# proto2.net
KiCad netlist of a schematic drawn in EAGLE
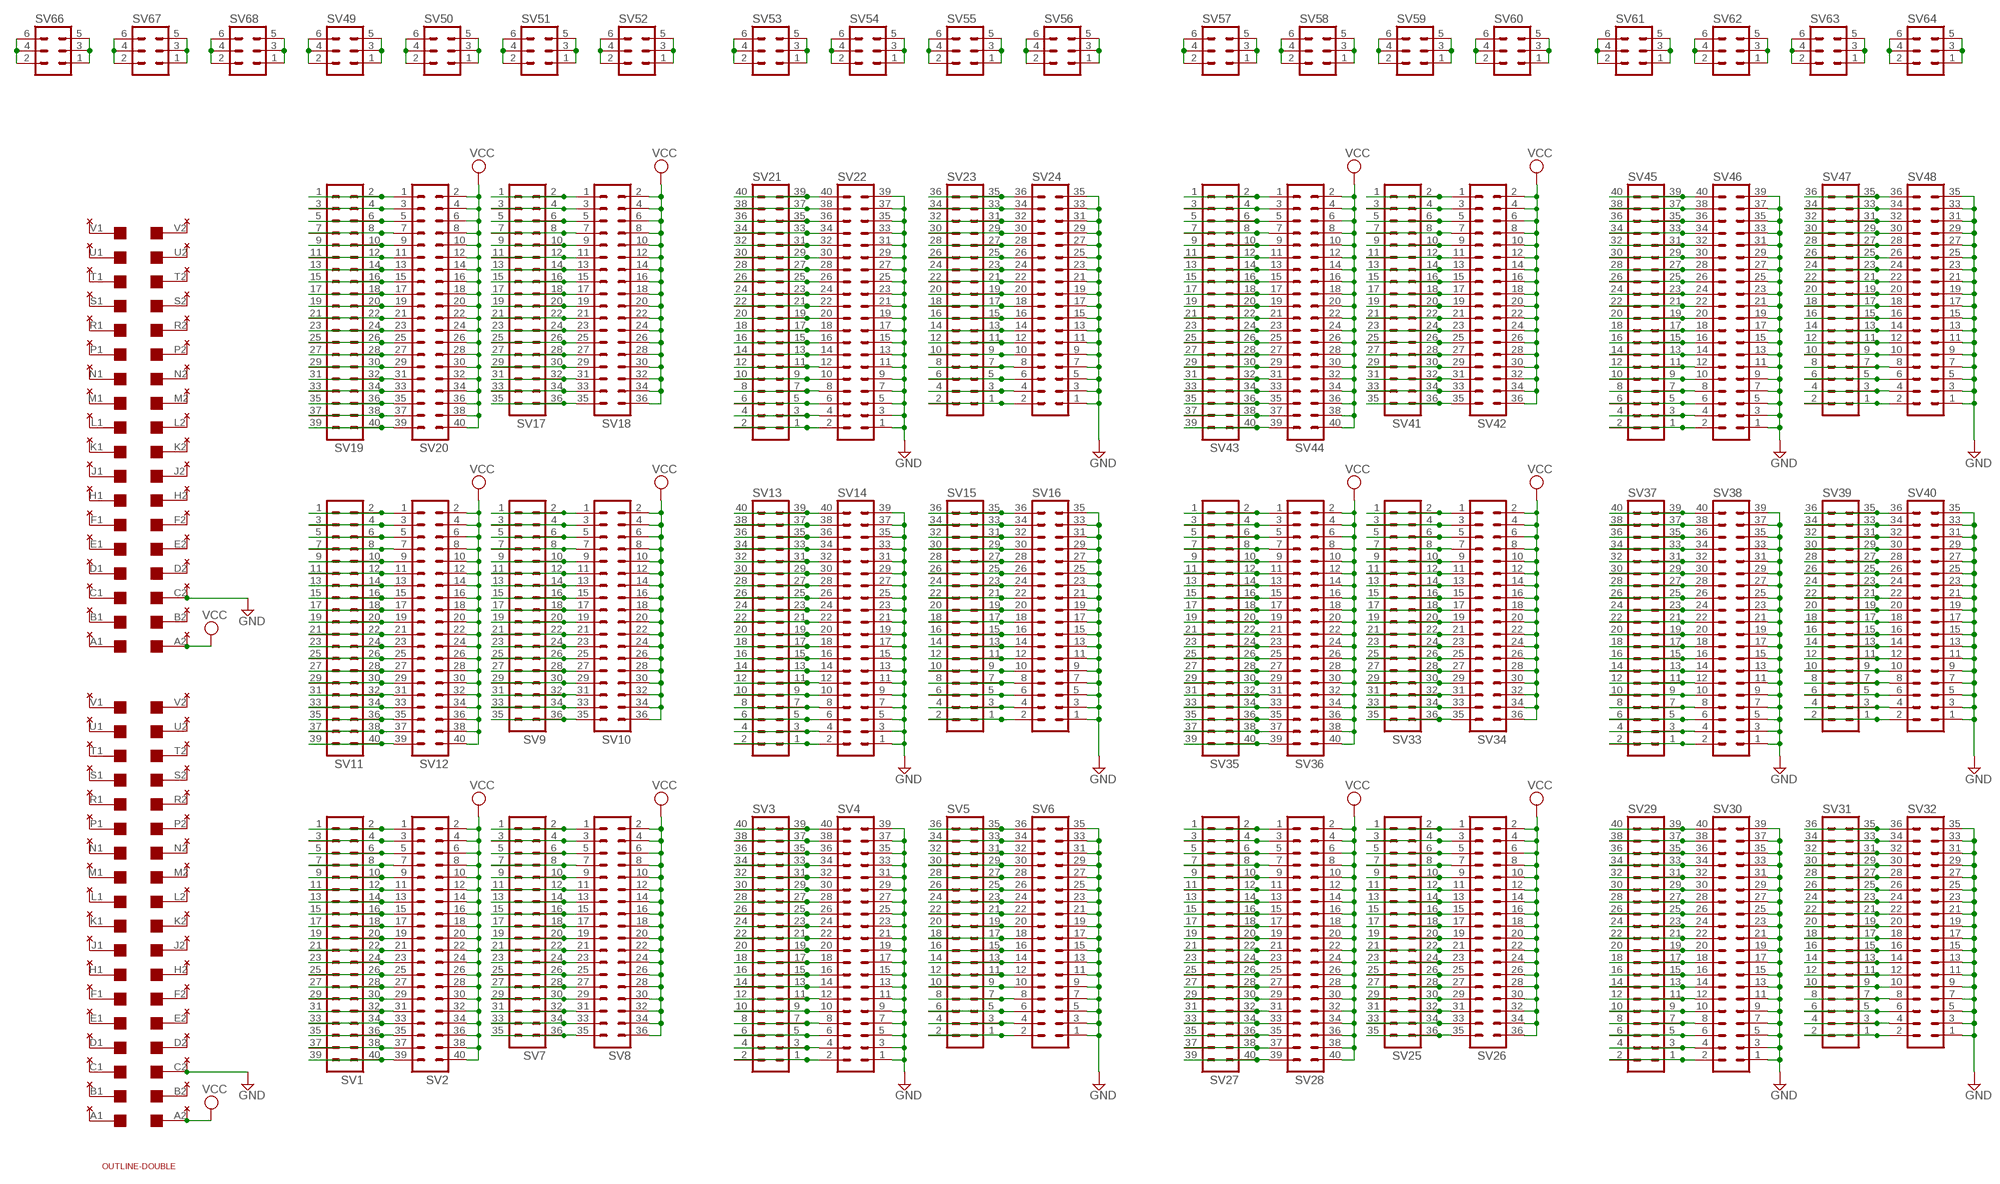
[diagram p0: schematic, sheet 1]

(export (version "E")
  (design (tool "Eeschema 10.0.6"))
  (components
    (comp (ref "A")
      (value "EDGE-2CONNECTOR")
      (footprint "eagle-import:EDGE-CON2")
      (libsource (lib "eagle-import") (part "EDGE-2CONNECTOR"))
    )
    (comp (ref "B")
      (value "EDGE-2CONNECTOR")
      (footprint "eagle-import:EDGE-CON2")
      (libsource (lib "eagle-import") (part "EDGE-2CONNECTOR"))
    )
    (comp (ref "SV1")
      (value "MA20-2")
      (footprint "eagle-import:MA20-2")
      (libsource (lib "eagle-import") (part "MA20-2"))
    )
    (comp (ref "SV2")
      (value "MA20-2")
      (footprint "eagle-import:MA20-2")
      (libsource (lib "eagle-import") (part "MA20-2"))
    )
    (comp (ref "SV3")
      (value "MA20-2")
      (footprint "eagle-import:MA20-2")
      (libsource (lib "eagle-import") (part "MA20-2"))
    )
    (comp (ref "SV4")
      (value "MA20-2")
      (footprint "eagle-import:MA20-2")
      (libsource (lib "eagle-import") (part "MA20-2"))
    )
    (comp (ref "SV5")
      (value "MA18-2")
      (footprint "eagle-import:MA18-2")
      (libsource (lib "eagle-import") (part "MA18-2"))
    )
    (comp (ref "SV6")
      (value "MA18-2")
      (footprint "eagle-import:MA18-2")
      (libsource (lib "eagle-import") (part "MA18-2"))
    )
    (comp (ref "SV7")
      (value "MA18-2")
      (footprint "eagle-import:MA18-2")
      (libsource (lib "eagle-import") (part "MA18-2"))
    )
    (comp (ref "SV8")
      (value "MA18-2")
      (footprint "eagle-import:MA18-2")
      (libsource (lib "eagle-import") (part "MA18-2"))
    )
    (comp (ref "SV9")
      (value "MA18-2")
      (footprint "eagle-import:MA18-2")
      (libsource (lib "eagle-import") (part "MA18-2"))
    )
    (comp (ref "SV10")
      (value "MA18-2")
      (footprint "eagle-import:MA18-2")
      (libsource (lib "eagle-import") (part "MA18-2"))
    )
    (comp (ref "SV11")
      (value "MA20-2")
      (footprint "eagle-import:MA20-2")
      (libsource (lib "eagle-import") (part "MA20-2"))
    )
    (comp (ref "SV12")
      (value "MA20-2")
      (footprint "eagle-import:MA20-2")
      (libsource (lib "eagle-import") (part "MA20-2"))
    )
    (comp (ref "SV13")
      (value "MA20-2")
      (footprint "eagle-import:MA20-2")
      (libsource (lib "eagle-import") (part "MA20-2"))
    )
    (comp (ref "SV14")
      (value "MA20-2")
      (footprint "eagle-import:MA20-2")
      (libsource (lib "eagle-import") (part "MA20-2"))
    )
    (comp (ref "SV15")
      (value "MA18-2")
      (footprint "eagle-import:MA18-2")
      (libsource (lib "eagle-import") (part "MA18-2"))
    )
    (comp (ref "SV16")
      (value "MA18-2")
      (footprint "eagle-import:MA18-2")
      (libsource (lib "eagle-import") (part "MA18-2"))
    )
    (comp (ref "SV17")
      (value "MA18-2")
      (footprint "eagle-import:MA18-2")
      (libsource (lib "eagle-import") (part "MA18-2"))
    )
    (comp (ref "SV18")
      (value "MA18-2")
      (footprint "eagle-import:MA18-2")
      (libsource (lib "eagle-import") (part "MA18-2"))
    )
    (comp (ref "SV19")
      (value "MA20-2")
      (footprint "eagle-import:MA20-2")
      (libsource (lib "eagle-import") (part "MA20-2"))
    )
    (comp (ref "SV20")
      (value "MA20-2")
      (footprint "eagle-import:MA20-2")
      (libsource (lib "eagle-import") (part "MA20-2"))
    )
    (comp (ref "SV21")
      (value "MA20-2")
      (footprint "eagle-import:MA20-2")
      (libsource (lib "eagle-import") (part "MA20-2"))
    )
    (comp (ref "SV22")
      (value "MA20-2")
      (footprint "eagle-import:MA20-2")
      (libsource (lib "eagle-import") (part "MA20-2"))
    )
    (comp (ref "SV23")
      (value "MA18-2")
      (footprint "eagle-import:MA18-2")
      (libsource (lib "eagle-import") (part "MA18-2"))
    )
    (comp (ref "SV24")
      (value "MA18-2")
      (footprint "eagle-import:MA18-2")
      (libsource (lib "eagle-import") (part "MA18-2"))
    )
    (comp (ref "SV25")
      (value "MA18-2")
      (footprint "eagle-import:MA18-2")
      (libsource (lib "eagle-import") (part "MA18-2"))
    )
    (comp (ref "SV26")
      (value "MA18-2")
      (footprint "eagle-import:MA18-2")
      (libsource (lib "eagle-import") (part "MA18-2"))
    )
    (comp (ref "SV27")
      (value "MA20-2")
      (footprint "eagle-import:MA20-2")
      (libsource (lib "eagle-import") (part "MA20-2"))
    )
    (comp (ref "SV28")
      (value "MA20-2")
      (footprint "eagle-import:MA20-2")
      (libsource (lib "eagle-import") (part "MA20-2"))
    )
    (comp (ref "SV29")
      (value "MA20-2")
      (footprint "eagle-import:MA20-2")
      (libsource (lib "eagle-import") (part "MA20-2"))
    )
    (comp (ref "SV30")
      (value "MA20-2")
      (footprint "eagle-import:MA20-2")
      (libsource (lib "eagle-import") (part "MA20-2"))
    )
    (comp (ref "SV31")
      (value "MA18-2")
      (footprint "eagle-import:MA18-2")
      (libsource (lib "eagle-import") (part "MA18-2"))
    )
    (comp (ref "SV32")
      (value "MA18-2")
      (footprint "eagle-import:MA18-2")
      (libsource (lib "eagle-import") (part "MA18-2"))
    )
    (comp (ref "SV33")
      (value "MA18-2")
      (footprint "eagle-import:MA18-2")
      (libsource (lib "eagle-import") (part "MA18-2"))
    )
    (comp (ref "SV34")
      (value "MA18-2")
      (footprint "eagle-import:MA18-2")
      (libsource (lib "eagle-import") (part "MA18-2"))
    )
    (comp (ref "SV35")
      (value "MA20-2")
      (footprint "eagle-import:MA20-2")
      (libsource (lib "eagle-import") (part "MA20-2"))
    )
    (comp (ref "SV36")
      (value "MA20-2")
      (footprint "eagle-import:MA20-2")
      (libsource (lib "eagle-import") (part "MA20-2"))
    )
    (comp (ref "SV37")
      (value "MA20-2")
      (footprint "eagle-import:MA20-2")
      (libsource (lib "eagle-import") (part "MA20-2"))
    )
    (comp (ref "SV38")
      (value "MA20-2")
      (footprint "eagle-import:MA20-2")
      (libsource (lib "eagle-import") (part "MA20-2"))
    )
    (comp (ref "SV39")
      (value "MA18-2")
      (footprint "eagle-import:MA18-2")
      (libsource (lib "eagle-import") (part "MA18-2"))
    )
    (comp (ref "SV40")
      (value "MA18-2")
      (footprint "eagle-import:MA18-2")
      (libsource (lib "eagle-import") (part "MA18-2"))
    )
    (comp (ref "SV41")
      (value "MA18-2")
      (footprint "eagle-import:MA18-2")
      (libsource (lib "eagle-import") (part "MA18-2"))
    )
    (comp (ref "SV42")
      (value "MA18-2")
      (footprint "eagle-import:MA18-2")
      (libsource (lib "eagle-import") (part "MA18-2"))
    )
    (comp (ref "SV43")
      (value "MA20-2")
      (footprint "eagle-import:MA20-2")
      (libsource (lib "eagle-import") (part "MA20-2"))
    )
    (comp (ref "SV44")
      (value "MA20-2")
      (footprint "eagle-import:MA20-2")
      (libsource (lib "eagle-import") (part "MA20-2"))
    )
    (comp (ref "SV45")
      (value "MA20-2")
      (footprint "eagle-import:MA20-2")
      (libsource (lib "eagle-import") (part "MA20-2"))
    )
    (comp (ref "SV46")
      (value "MA20-2")
      (footprint "eagle-import:MA20-2")
      (libsource (lib "eagle-import") (part "MA20-2"))
    )
    (comp (ref "SV47")
      (value "MA18-2")
      (footprint "eagle-import:MA18-2")
      (libsource (lib "eagle-import") (part "MA18-2"))
    )
    (comp (ref "SV48")
      (value "MA18-2")
      (footprint "eagle-import:MA18-2")
      (libsource (lib "eagle-import") (part "MA18-2"))
    )
    (comp (ref "SV49")
      (value "MA03-2")
      (footprint "eagle-import:MA03-2")
      (libsource (lib "eagle-import") (part "MA03-2"))
    )
    (comp (ref "SV50")
      (value "MA03-2")
      (footprint "eagle-import:MA03-2")
      (libsource (lib "eagle-import") (part "MA03-2"))
    )
    (comp (ref "SV51")
      (value "MA03-2")
      (footprint "eagle-import:MA03-2")
      (libsource (lib "eagle-import") (part "MA03-2"))
    )
    (comp (ref "SV52")
      (value "MA03-2")
      (footprint "eagle-import:MA03-2")
      (libsource (lib "eagle-import") (part "MA03-2"))
    )
    (comp (ref "SV53")
      (value "MA03-2")
      (footprint "eagle-import:MA03-2")
      (libsource (lib "eagle-import") (part "MA03-2"))
    )
    (comp (ref "SV54")
      (value "MA03-2")
      (footprint "eagle-import:MA03-2")
      (libsource (lib "eagle-import") (part "MA03-2"))
    )
    (comp (ref "SV55")
      (value "MA03-2")
      (footprint "eagle-import:MA03-2")
      (libsource (lib "eagle-import") (part "MA03-2"))
    )
    (comp (ref "SV56")
      (value "MA03-2")
      (footprint "eagle-import:MA03-2")
      (libsource (lib "eagle-import") (part "MA03-2"))
    )
    (comp (ref "SV57")
      (value "MA03-2")
      (footprint "eagle-import:MA03-2")
      (libsource (lib "eagle-import") (part "MA03-2"))
    )
    (comp (ref "SV58")
      (value "MA03-2")
      (footprint "eagle-import:MA03-2")
      (libsource (lib "eagle-import") (part "MA03-2"))
    )
    (comp (ref "SV59")
      (value "MA03-2")
      (footprint "eagle-import:MA03-2")
      (libsource (lib "eagle-import") (part "MA03-2"))
    )
    (comp (ref "SV60")
      (value "MA03-2")
      (footprint "eagle-import:MA03-2")
      (libsource (lib "eagle-import") (part "MA03-2"))
    )
    (comp (ref "SV61")
      (value "MA03-2")
      (footprint "eagle-import:MA03-2")
      (libsource (lib "eagle-import") (part "MA03-2"))
    )
    (comp (ref "SV62")
      (value "MA03-2")
      (footprint "eagle-import:MA03-2")
      (libsource (lib "eagle-import") (part "MA03-2"))
    )
    (comp (ref "SV63")
      (value "MA03-2")
      (footprint "eagle-import:MA03-2")
      (libsource (lib "eagle-import") (part "MA03-2"))
    )
    (comp (ref "SV64")
      (value "MA03-2")
      (footprint "eagle-import:MA03-2")
      (libsource (lib "eagle-import") (part "MA03-2"))
    )
    (comp (ref "SV66")
      (value "MA03-2")
      (footprint "eagle-import:MA03-2")
      (libsource (lib "eagle-import") (part "MA03-2"))
    )
    (comp (ref "SV67")
      (value "MA03-2")
      (footprint "eagle-import:MA03-2")
      (libsource (lib "eagle-import") (part "MA03-2"))
    )
    (comp (ref "SV68")
      (value "MA03-2")
      (footprint "eagle-import:MA03-2")
      (libsource (lib "eagle-import") (part "MA03-2"))
    )
    (comp (ref "U$3")
      (value "THRU-HOLE2A")
      (footprint "eagle-import:THRU-HOLEA")
      (libsource (lib "eagle-import") (part "THRU-HOLE2A"))
    )
    (comp (ref "U$4")
      (value "OUTLINE-DOUBLE")
      (footprint "eagle-import:DOUBLE")
      (libsource (lib "eagle-import") (part "OUTLINE-DOUBLE"))
    )
    (comp (ref "U$5")
      (value "THRU-HOLE2A")
      (footprint "eagle-import:THRU-HOLEA")
      (libsource (lib "eagle-import") (part "THRU-HOLE2A"))
    )
  )
  (nets
    (net (code "1") (name "GND") (class "Default")
      (node (ref "A") (pin "C2") (pinfunction "1_C2") (pintype "bidirectional"))
      (node (ref "B") (pin "C2") (pinfunction "1_C2") (pintype "bidirectional"))
      (node (ref "SV14") (pin "1") (pinfunction "1_1") (pintype "passive"))
      (node (ref "SV14") (pin "11") (pinfunction "11_11") (pintype "passive"))
      (node (ref "SV14") (pin "13") (pinfunction "13_13") (pintype "passive"))
      (node (ref "SV14") (pin "15") (pinfunction "15_15") (pintype "passive"))
      (node (ref "SV14") (pin "17") (pinfunction "17_17") (pintype "passive"))
      (node (ref "SV14") (pin "19") (pinfunction "19_19") (pintype "passive"))
      (node (ref "SV14") (pin "21") (pinfunction "21_21") (pintype "passive"))
      (node (ref "SV14") (pin "23") (pinfunction "23_23") (pintype "passive"))
      (node (ref "SV14") (pin "25") (pinfunction "25_25") (pintype "passive"))
      (node (ref "SV14") (pin "27") (pinfunction "27_27") (pintype "passive"))
      (node (ref "SV14") (pin "29") (pinfunction "29_29") (pintype "passive"))
      (node (ref "SV14") (pin "3") (pinfunction "3_3") (pintype "passive"))
      (node (ref "SV14") (pin "31") (pinfunction "31_31") (pintype "passive"))
      (node (ref "SV14") (pin "33") (pinfunction "33_33") (pintype "passive"))
      (node (ref "SV14") (pin "35") (pinfunction "35_35") (pintype "passive"))
      (node (ref "SV14") (pin "37") (pinfunction "37_37") (pintype "passive"))
      (node (ref "SV14") (pin "39") (pinfunction "39_39") (pintype "passive"))
      (node (ref "SV14") (pin "5") (pinfunction "5_5") (pintype "passive"))
      (node (ref "SV14") (pin "7") (pinfunction "7_7") (pintype "passive"))
      (node (ref "SV14") (pin "9") (pinfunction "9_9") (pintype "passive"))
      (node (ref "SV16") (pin "1") (pinfunction "1_1") (pintype "passive"))
      (node (ref "SV16") (pin "11") (pinfunction "11_11") (pintype "passive"))
      (node (ref "SV16") (pin "13") (pinfunction "13_13") (pintype "passive"))
      (node (ref "SV16") (pin "15") (pinfunction "15_15") (pintype "passive"))
      (node (ref "SV16") (pin "17") (pinfunction "17_17") (pintype "passive"))
      (node (ref "SV16") (pin "19") (pinfunction "19_19") (pintype "passive"))
      (node (ref "SV16") (pin "21") (pinfunction "21_21") (pintype "passive"))
      (node (ref "SV16") (pin "23") (pinfunction "23_23") (pintype "passive"))
      (node (ref "SV16") (pin "25") (pinfunction "25_25") (pintype "passive"))
      (node (ref "SV16") (pin "27") (pinfunction "27_27") (pintype "passive"))
      (node (ref "SV16") (pin "29") (pinfunction "29_29") (pintype "passive"))
      (node (ref "SV16") (pin "3") (pinfunction "3_3") (pintype "passive"))
      (node (ref "SV16") (pin "31") (pinfunction "31_31") (pintype "passive"))
      (node (ref "SV16") (pin "33") (pinfunction "33_33") (pintype "passive"))
      (node (ref "SV16") (pin "35") (pinfunction "35_35") (pintype "passive"))
      (node (ref "SV16") (pin "5") (pinfunction "5_5") (pintype "passive"))
      (node (ref "SV16") (pin "7") (pinfunction "7_7") (pintype "passive"))
      (node (ref "SV16") (pin "9") (pinfunction "9_9") (pintype "passive"))
      (node (ref "SV22") (pin "1") (pinfunction "1_1") (pintype "passive"))
      (node (ref "SV22") (pin "11") (pinfunction "11_11") (pintype "passive"))
      (node (ref "SV22") (pin "13") (pinfunction "13_13") (pintype "passive"))
      (node (ref "SV22") (pin "15") (pinfunction "15_15") (pintype "passive"))
      (node (ref "SV22") (pin "17") (pinfunction "17_17") (pintype "passive"))
      (node (ref "SV22") (pin "19") (pinfunction "19_19") (pintype "passive"))
      (node (ref "SV22") (pin "21") (pinfunction "21_21") (pintype "passive"))
      (node (ref "SV22") (pin "23") (pinfunction "23_23") (pintype "passive"))
      (node (ref "SV22") (pin "25") (pinfunction "25_25") (pintype "passive"))
      (node (ref "SV22") (pin "27") (pinfunction "27_27") (pintype "passive"))
      (node (ref "SV22") (pin "29") (pinfunction "29_29") (pintype "passive"))
      (node (ref "SV22") (pin "3") (pinfunction "3_3") (pintype "passive"))
      (node (ref "SV22") (pin "31") (pinfunction "31_31") (pintype "passive"))
      (node (ref "SV22") (pin "33") (pinfunction "33_33") (pintype "passive"))
      (node (ref "SV22") (pin "35") (pinfunction "35_35") (pintype "passive"))
      (node (ref "SV22") (pin "37") (pinfunction "37_37") (pintype "passive"))
      (node (ref "SV22") (pin "39") (pinfunction "39_39") (pintype "passive"))
      (node (ref "SV22") (pin "5") (pinfunction "5_5") (pintype "passive"))
      (node (ref "SV22") (pin "7") (pinfunction "7_7") (pintype "passive"))
      (node (ref "SV22") (pin "9") (pinfunction "9_9") (pintype "passive"))
      (node (ref "SV24") (pin "1") (pinfunction "1_1") (pintype "passive"))
      (node (ref "SV24") (pin "11") (pinfunction "11_11") (pintype "passive"))
      (node (ref "SV24") (pin "13") (pinfunction "13_13") (pintype "passive"))
      (node (ref "SV24") (pin "15") (pinfunction "15_15") (pintype "passive"))
      (node (ref "SV24") (pin "17") (pinfunction "17_17") (pintype "passive"))
      (node (ref "SV24") (pin "19") (pinfunction "19_19") (pintype "passive"))
      (node (ref "SV24") (pin "21") (pinfunction "21_21") (pintype "passive"))
      (node (ref "SV24") (pin "23") (pinfunction "23_23") (pintype "passive"))
      (node (ref "SV24") (pin "25") (pinfunction "25_25") (pintype "passive"))
      (node (ref "SV24") (pin "27") (pinfunction "27_27") (pintype "passive"))
      (node (ref "SV24") (pin "29") (pinfunction "29_29") (pintype "passive"))
      (node (ref "SV24") (pin "3") (pinfunction "3_3") (pintype "passive"))
      (node (ref "SV24") (pin "31") (pinfunction "31_31") (pintype "passive"))
      (node (ref "SV24") (pin "33") (pinfunction "33_33") (pintype "passive"))
      (node (ref "SV24") (pin "35") (pinfunction "35_35") (pintype "passive"))
      (node (ref "SV24") (pin "5") (pinfunction "5_5") (pintype "passive"))
      (node (ref "SV24") (pin "7") (pinfunction "7_7") (pintype "passive"))
      (node (ref "SV24") (pin "9") (pinfunction "9_9") (pintype "passive"))
      (node (ref "SV30") (pin "1") (pinfunction "1_1") (pintype "passive"))
      (node (ref "SV30") (pin "11") (pinfunction "11_11") (pintype "passive"))
      (node (ref "SV30") (pin "13") (pinfunction "13_13") (pintype "passive"))
      (node (ref "SV30") (pin "15") (pinfunction "15_15") (pintype "passive"))
      (node (ref "SV30") (pin "17") (pinfunction "17_17") (pintype "passive"))
      (node (ref "SV30") (pin "19") (pinfunction "19_19") (pintype "passive"))
      (node (ref "SV30") (pin "21") (pinfunction "21_21") (pintype "passive"))
      (node (ref "SV30") (pin "23") (pinfunction "23_23") (pintype "passive"))
      (node (ref "SV30") (pin "25") (pinfunction "25_25") (pintype "passive"))
      (node (ref "SV30") (pin "27") (pinfunction "27_27") (pintype "passive"))
      (node (ref "SV30") (pin "29") (pinfunction "29_29") (pintype "passive"))
      (node (ref "SV30") (pin "3") (pinfunction "3_3") (pintype "passive"))
      (node (ref "SV30") (pin "31") (pinfunction "31_31") (pintype "passive"))
      (node (ref "SV30") (pin "33") (pinfunction "33_33") (pintype "passive"))
      (node (ref "SV30") (pin "35") (pinfunction "35_35") (pintype "passive"))
      (node (ref "SV30") (pin "37") (pinfunction "37_37") (pintype "passive"))
      (node (ref "SV30") (pin "39") (pinfunction "39_39") (pintype "passive"))
      (node (ref "SV30") (pin "5") (pinfunction "5_5") (pintype "passive"))
      (node (ref "SV30") (pin "7") (pinfunction "7_7") (pintype "passive"))
      (node (ref "SV30") (pin "9") (pinfunction "9_9") (pintype "passive"))
      (node (ref "SV32") (pin "1") (pinfunction "1_1") (pintype "passive"))
      (node (ref "SV32") (pin "11") (pinfunction "11_11") (pintype "passive"))
      (node (ref "SV32") (pin "13") (pinfunction "13_13") (pintype "passive"))
      (node (ref "SV32") (pin "15") (pinfunction "15_15") (pintype "passive"))
      (node (ref "SV32") (pin "17") (pinfunction "17_17") (pintype "passive"))
      (node (ref "SV32") (pin "19") (pinfunction "19_19") (pintype "passive"))
      (node (ref "SV32") (pin "21") (pinfunction "21_21") (pintype "passive"))
      (node (ref "SV32") (pin "23") (pinfunction "23_23") (pintype "passive"))
      (node (ref "SV32") (pin "25") (pinfunction "25_25") (pintype "passive"))
      (node (ref "SV32") (pin "27") (pinfunction "27_27") (pintype "passive"))
      (node (ref "SV32") (pin "29") (pinfunction "29_29") (pintype "passive"))
      (node (ref "SV32") (pin "3") (pinfunction "3_3") (pintype "passive"))
      (node (ref "SV32") (pin "31") (pinfunction "31_31") (pintype "passive"))
      (node (ref "SV32") (pin "33") (pinfunction "33_33") (pintype "passive"))
      (node (ref "SV32") (pin "35") (pinfunction "35_35") (pintype "passive"))
      (node (ref "SV32") (pin "5") (pinfunction "5_5") (pintype "passive"))
      (node (ref "SV32") (pin "7") (pinfunction "7_7") (pintype "passive"))
      (node (ref "SV32") (pin "9") (pinfunction "9_9") (pintype "passive"))
      (node (ref "SV38") (pin "1") (pinfunction "1_1") (pintype "passive"))
      (node (ref "SV38") (pin "11") (pinfunction "11_11") (pintype "passive"))
      (node (ref "SV38") (pin "13") (pinfunction "13_13") (pintype "passive"))
      (node (ref "SV38") (pin "15") (pinfunction "15_15") (pintype "passive"))
      (node (ref "SV38") (pin "17") (pinfunction "17_17") (pintype "passive"))
      (node (ref "SV38") (pin "19") (pinfunction "19_19") (pintype "passive"))
      (node (ref "SV38") (pin "21") (pinfunction "21_21") (pintype "passive"))
      (node (ref "SV38") (pin "23") (pinfunction "23_23") (pintype "passive"))
      (node (ref "SV38") (pin "25") (pinfunction "25_25") (pintype "passive"))
      (node (ref "SV38") (pin "27") (pinfunction "27_27") (pintype "passive"))
      (node (ref "SV38") (pin "29") (pinfunction "29_29") (pintype "passive"))
      (node (ref "SV38") (pin "3") (pinfunction "3_3") (pintype "passive"))
      (node (ref "SV38") (pin "31") (pinfunction "31_31") (pintype "passive"))
      (node (ref "SV38") (pin "33") (pinfunction "33_33") (pintype "passive"))
      (node (ref "SV38") (pin "35") (pinfunction "35_35") (pintype "passive"))
      (node (ref "SV38") (pin "37") (pinfunction "37_37") (pintype "passive"))
      (node (ref "SV38") (pin "39") (pinfunction "39_39") (pintype "passive"))
      (node (ref "SV38") (pin "5") (pinfunction "5_5") (pintype "passive"))
      (node (ref "SV38") (pin "7") (pinfunction "7_7") (pintype "passive"))
      (node (ref "SV38") (pin "9") (pinfunction "9_9") (pintype "passive"))
      (node (ref "SV4") (pin "1") (pinfunction "1_1") (pintype "passive"))
      (node (ref "SV4") (pin "11") (pinfunction "11_11") (pintype "passive"))
      (node (ref "SV4") (pin "13") (pinfunction "13_13") (pintype "passive"))
      (node (ref "SV4") (pin "15") (pinfunction "15_15") (pintype "passive"))
      (node (ref "SV4") (pin "17") (pinfunction "17_17") (pintype "passive"))
      (node (ref "SV4") (pin "19") (pinfunction "19_19") (pintype "passive"))
      (node (ref "SV4") (pin "21") (pinfunction "21_21") (pintype "passive"))
      (node (ref "SV4") (pin "23") (pinfunction "23_23") (pintype "passive"))
      (node (ref "SV4") (pin "25") (pinfunction "25_25") (pintype "passive"))
      (node (ref "SV4") (pin "27") (pinfunction "27_27") (pintype "passive"))
      (node (ref "SV4") (pin "29") (pinfunction "29_29") (pintype "passive"))
      (node (ref "SV4") (pin "3") (pinfunction "3_3") (pintype "passive"))
      (node (ref "SV4") (pin "31") (pinfunction "31_31") (pintype "passive"))
      (node (ref "SV4") (pin "33") (pinfunction "33_33") (pintype "passive"))
      (node (ref "SV4") (pin "35") (pinfunction "35_35") (pintype "passive"))
      (node (ref "SV4") (pin "37") (pinfunction "37_37") (pintype "passive"))
      (node (ref "SV4") (pin "39") (pinfunction "39_39") (pintype "passive"))
      (node (ref "SV4") (pin "5") (pinfunction "5_5") (pintype "passive"))
      (node (ref "SV4") (pin "7") (pinfunction "7_7") (pintype "passive"))
      (node (ref "SV4") (pin "9") (pinfunction "9_9") (pintype "passive"))
      (node (ref "SV40") (pin "1") (pinfunction "1_1") (pintype "passive"))
      (node (ref "SV40") (pin "11") (pinfunction "11_11") (pintype "passive"))
      (node (ref "SV40") (pin "13") (pinfunction "13_13") (pintype "passive"))
      (node (ref "SV40") (pin "15") (pinfunction "15_15") (pintype "passive"))
      (node (ref "SV40") (pin "17") (pinfunction "17_17") (pintype "passive"))
      (node (ref "SV40") (pin "19") (pinfunction "19_19") (pintype "passive"))
      (node (ref "SV40") (pin "21") (pinfunction "21_21") (pintype "passive"))
      (node (ref "SV40") (pin "23") (pinfunction "23_23") (pintype "passive"))
      (node (ref "SV40") (pin "25") (pinfunction "25_25") (pintype "passive"))
      (node (ref "SV40") (pin "27") (pinfunction "27_27") (pintype "passive"))
      (node (ref "SV40") (pin "29") (pinfunction "29_29") (pintype "passive"))
      (node (ref "SV40") (pin "3") (pinfunction "3_3") (pintype "passive"))
      (node (ref "SV40") (pin "31") (pinfunction "31_31") (pintype "passive"))
      (node (ref "SV40") (pin "33") (pinfunction "33_33") (pintype "passive"))
      (node (ref "SV40") (pin "35") (pinfunction "35_35") (pintype "passive"))
      (node (ref "SV40") (pin "5") (pinfunction "5_5") (pintype "passive"))
      (node (ref "SV40") (pin "7") (pinfunction "7_7") (pintype "passive"))
      (node (ref "SV40") (pin "9") (pinfunction "9_9") (pintype "passive"))
      (node (ref "SV46") (pin "1") (pinfunction "1_1") (pintype "passive"))
      (node (ref "SV46") (pin "11") (pinfunction "11_11") (pintype "passive"))
      (node (ref "SV46") (pin "13") (pinfunction "13_13") (pintype "passive"))
      (node (ref "SV46") (pin "15") (pinfunction "15_15") (pintype "passive"))
      (node (ref "SV46") (pin "17") (pinfunction "17_17") (pintype "passive"))
      (node (ref "SV46") (pin "19") (pinfunction "19_19") (pintype "passive"))
      (node (ref "SV46") (pin "21") (pinfunction "21_21") (pintype "passive"))
      (node (ref "SV46") (pin "23") (pinfunction "23_23") (pintype "passive"))
      (node (ref "SV46") (pin "25") (pinfunction "25_25") (pintype "passive"))
      (node (ref "SV46") (pin "27") (pinfunction "27_27") (pintype "passive"))
      (node (ref "SV46") (pin "29") (pinfunction "29_29") (pintype "passive"))
      (node (ref "SV46") (pin "3") (pinfunction "3_3") (pintype "passive"))
      (node (ref "SV46") (pin "31") (pinfunction "31_31") (pintype "passive"))
      (node (ref "SV46") (pin "33") (pinfunction "33_33") (pintype "passive"))
      (node (ref "SV46") (pin "35") (pinfunction "35_35") (pintype "passive"))
      (node (ref "SV46") (pin "37") (pinfunction "37_37") (pintype "passive"))
      (node (ref "SV46") (pin "39") (pinfunction "39_39") (pintype "passive"))
      (node (ref "SV46") (pin "5") (pinfunction "5_5") (pintype "passive"))
      (node (ref "SV46") (pin "7") (pinfunction "7_7") (pintype "passive"))
      (node (ref "SV46") (pin "9") (pinfunction "9_9") (pintype "passive"))
      (node (ref "SV48") (pin "1") (pinfunction "1_1") (pintype "passive"))
      (node (ref "SV48") (pin "11") (pinfunction "11_11") (pintype "passive"))
      (node (ref "SV48") (pin "13") (pinfunction "13_13") (pintype "passive"))
      (node (ref "SV48") (pin "15") (pinfunction "15_15") (pintype "passive"))
      (node (ref "SV48") (pin "17") (pinfunction "17_17") (pintype "passive"))
      (node (ref "SV48") (pin "19") (pinfunction "19_19") (pintype "passive"))
      (node (ref "SV48") (pin "21") (pinfunction "21_21") (pintype "passive"))
      (node (ref "SV48") (pin "23") (pinfunction "23_23") (pintype "passive"))
      (node (ref "SV48") (pin "25") (pinfunction "25_25") (pintype "passive"))
      (node (ref "SV48") (pin "27") (pinfunction "27_27") (pintype "passive"))
      (node (ref "SV48") (pin "29") (pinfunction "29_29") (pintype "passive"))
      (node (ref "SV48") (pin "3") (pinfunction "3_3") (pintype "passive"))
      (node (ref "SV48") (pin "31") (pinfunction "31_31") (pintype "passive"))
      (node (ref "SV48") (pin "33") (pinfunction "33_33") (pintype "passive"))
      (node (ref "SV48") (pin "35") (pinfunction "35_35") (pintype "passive"))
      (node (ref "SV48") (pin "5") (pinfunction "5_5") (pintype "passive"))
      (node (ref "SV48") (pin "7") (pinfunction "7_7") (pintype "passive"))
      (node (ref "SV48") (pin "9") (pinfunction "9_9") (pintype "passive"))
      (node (ref "SV6") (pin "1") (pinfunction "1_1") (pintype "passive"))
      (node (ref "SV6") (pin "11") (pinfunction "11_11") (pintype "passive"))
      (node (ref "SV6") (pin "13") (pinfunction "13_13") (pintype "passive"))
      (node (ref "SV6") (pin "15") (pinfunction "15_15") (pintype "passive"))
      (node (ref "SV6") (pin "17") (pinfunction "17_17") (pintype "passive"))
      (node (ref "SV6") (pin "19") (pinfunction "19_19") (pintype "passive"))
      (node (ref "SV6") (pin "21") (pinfunction "21_21") (pintype "passive"))
      (node (ref "SV6") (pin "23") (pinfunction "23_23") (pintype "passive"))
      (node (ref "SV6") (pin "25") (pinfunction "25_25") (pintype "passive"))
      (node (ref "SV6") (pin "27") (pinfunction "27_27") (pintype "passive"))
      (node (ref "SV6") (pin "29") (pinfunction "29_29") (pintype "passive"))
      (node (ref "SV6") (pin "3") (pinfunction "3_3") (pintype "passive"))
      (node (ref "SV6") (pin "31") (pinfunction "31_31") (pintype "passive"))
      (node (ref "SV6") (pin "33") (pinfunction "33_33") (pintype "passive"))
      (node (ref "SV6") (pin "35") (pinfunction "35_35") (pintype "passive"))
      (node (ref "SV6") (pin "5") (pinfunction "5_5") (pintype "passive"))
      (node (ref "SV6") (pin "7") (pinfunction "7_7") (pintype "passive"))
      (node (ref "SV6") (pin "9") (pinfunction "9_9") (pintype "passive"))
      (node (ref "U$3") (pin "C2") (pinfunction "P$1_C2") (pintype "passive"))
      (node (ref "U$5") (pin "C2") (pinfunction "P$1_C2") (pintype "passive"))
    )
    (net (code "2") (name "Net-(AA-1)") (class "Default")
      (node (ref "A") (pin "A1") (pinfunction "1_A1") (pintype "bidirectional"))
      (node (ref "U$3") (pin "A1") (pinfunction "P$1_A1") (pintype "passive"))
    )
    (net (code "3") (name "Net-(AAA-1)") (class "Default")
      (node (ref "A") (pin "R1") (pinfunction "1_R1") (pintype "bidirectional"))
      (node (ref "U$3") (pin "R1") (pinfunction "P$1_R1") (pintype "passive"))
    )
    (net (code "4") (name "Net-(AAB-1)") (class "Default")
      (node (ref "A") (pin "R2") (pinfunction "1_R2") (pintype "bidirectional"))
      (node (ref "U$3") (pin "R2") (pinfunction "P$1_R2") (pintype "passive"))
    )
    (net (code "5") (name "Net-(AAC-1)") (class "Default")
      (node (ref "A") (pin "S1") (pinfunction "1_S1") (pintype "bidirectional"))
      (node (ref "U$3") (pin "S1") (pinfunction "P$1_S1") (pintype "passive"))
    )
    (net (code "6") (name "Net-(AAD-1)") (class "Default")
      (node (ref "A") (pin "S2") (pinfunction "1_S2") (pintype "bidirectional"))
      (node (ref "U$3") (pin "S2") (pinfunction "P$1_S2") (pintype "passive"))
    )
    (net (code "7") (name "Net-(AAE-1)") (class "Default")
      (node (ref "A") (pin "T1") (pinfunction "1_T1") (pintype "bidirectional"))
      (node (ref "U$3") (pin "T1") (pinfunction "P$1_T1") (pintype "passive"))
    )
    (net (code "8") (name "Net-(AAF-1)") (class "Default")
      (node (ref "A") (pin "T2") (pinfunction "1_T2") (pintype "bidirectional"))
      (node (ref "U$3") (pin "T2") (pinfunction "P$1_T2") (pintype "passive"))
    )
    (net (code "9") (name "Net-(AAG-1)") (class "Default")
      (node (ref "A") (pin "U1") (pinfunction "1_U1") (pintype "bidirectional"))
      (node (ref "U$3") (pin "U1") (pinfunction "P$1_U1") (pintype "passive"))
    )
    (net (code "10") (name "Net-(AAH-1)") (class "Default")
      (node (ref "A") (pin "U2") (pinfunction "1_U2") (pintype "bidirectional"))
      (node (ref "U$3") (pin "U2") (pinfunction "P$1_U2") (pintype "passive"))
    )
    (net (code "11") (name "Net-(AAI-1)") (class "Default")
      (node (ref "A") (pin "V1") (pinfunction "1_V1") (pintype "bidirectional"))
      (node (ref "U$3") (pin "V1") (pinfunction "P$1_V1") (pintype "passive"))
    )
    (net (code "12") (name "Net-(AAJ-1)") (class "Default")
      (node (ref "A") (pin "V2") (pinfunction "1_V2") (pintype "bidirectional"))
      (node (ref "U$3") (pin "V2") (pinfunction "P$1_V2") (pintype "passive"))
    )
    (net (code "13") (name "Net-(AC-1)") (class "Default")
      (node (ref "A") (pin "B1") (pinfunction "1_B1") (pintype "bidirectional"))
      (node (ref "U$3") (pin "B1") (pinfunction "P$1_B1") (pintype "passive"))
    )
    (net (code "14") (name "Net-(AD-1)") (class "Default")
      (node (ref "A") (pin "B2") (pinfunction "1_B2") (pintype "bidirectional"))
      (node (ref "U$3") (pin "B2") (pinfunction "P$1_B2") (pintype "passive"))
    )
    (net (code "15") (name "Net-(AE-1)") (class "Default")
      (node (ref "A") (pin "C1") (pinfunction "1_C1") (pintype "bidirectional"))
      (node (ref "U$3") (pin "C1") (pinfunction "P$1_C1") (pintype "passive"))
    )
    (net (code "16") (name "Net-(AG-1)") (class "Default")
      (node (ref "A") (pin "D1") (pinfunction "1_D1") (pintype "bidirectional"))
      (node (ref "U$3") (pin "D1") (pinfunction "P$1_D1") (pintype "passive"))
    )
    (net (code "17") (name "Net-(AH-1)") (class "Default")
      (node (ref "A") (pin "D2") (pinfunction "1_D2") (pintype "bidirectional"))
      (node (ref "U$3") (pin "D2") (pinfunction "P$1_D2") (pintype "passive"))
    )
    (net (code "18") (name "Net-(AI-1)") (class "Default")
      (node (ref "A") (pin "E1") (pinfunction "1_E1") (pintype "bidirectional"))
      (node (ref "U$3") (pin "E1") (pinfunction "P$1_E1") (pintype "passive"))
    )
    (net (code "19") (name "Net-(AJ-1)") (class "Default")
      (node (ref "A") (pin "E2") (pinfunction "1_E2") (pintype "bidirectional"))
      (node (ref "U$3") (pin "E2") (pinfunction "P$1_E2") (pintype "passive"))
    )
    (net (code "20") (name "Net-(AK-1)") (class "Default")
      (node (ref "A") (pin "F1") (pinfunction "1_F1") (pintype "bidirectional"))
      (node (ref "U$3") (pin "F1") (pinfunction "P$1_F1") (pintype "passive"))
    )
    (net (code "21") (name "Net-(AL-1)") (class "Default")
      (node (ref "A") (pin "F2") (pinfunction "1_F2") (pintype "bidirectional"))
      (node (ref "U$3") (pin "F2") (pinfunction "P$1_F2") (pintype "passive"))
    )
    (net (code "22") (name "Net-(AM-1)") (class "Default")
      (node (ref "A") (pin "H1") (pinfunction "1_H1") (pintype "bidirectional"))
      (node (ref "U$3") (pin "H1") (pinfunction "P$1_H1") (pintype "passive"))
    )
    (net (code "23") (name "Net-(AN-1)") (class "Default")
      (node (ref "A") (pin "H2") (pinfunction "1_H2") (pintype "bidirectional"))
      (node (ref "U$3") (pin "H2") (pinfunction "P$1_H2") (pintype "passive"))
    )
    (net (code "24") (name "Net-(AO-1)") (class "Default")
      (node (ref "A") (pin "J1") (pinfunction "1_J1") (pintype "bidirectional"))
      (node (ref "U$3") (pin "J1") (pinfunction "P$1_J1") (pintype "passive"))
    )
    (net (code "25") (name "Net-(AP-1)") (class "Default")
      (node (ref "A") (pin "J2") (pinfunction "1_J2") (pintype "bidirectional"))
      (node (ref "U$3") (pin "J2") (pinfunction "P$1_J2") (pintype "passive"))
    )
    (net (code "26") (name "Net-(AQ-1)") (class "Default")
      (node (ref "A") (pin "K1") (pinfunction "1_K1") (pintype "bidirectional"))
      (node (ref "U$3") (pin "K1") (pinfunction "P$1_K1") (pintype "passive"))
    )
    (net (code "27") (name "Net-(AR-1)") (class "Default")
      (node (ref "A") (pin "K2") (pinfunction "1_K2") (pintype "bidirectional"))
      (node (ref "U$3") (pin "K2") (pinfunction "P$1_K2") (pintype "passive"))
    )
    (net (code "28") (name "Net-(AS-1)") (class "Default")
      (node (ref "A") (pin "L1") (pinfunction "1_L1") (pintype "bidirectional"))
      (node (ref "U$3") (pin "L1") (pinfunction "P$1_L1") (pintype "passive"))
    )
    (net (code "29") (name "Net-(AT-1)") (class "Default")
      (node (ref "A") (pin "L2") (pinfunction "1_L2") (pintype "bidirectional"))
      (node (ref "U$3") (pin "L2") (pinfunction "P$1_L2") (pintype "passive"))
    )
    (net (code "30") (name "Net-(AU-1)") (class "Default")
      (node (ref "A") (pin "M1") (pinfunction "1_M1") (pintype "bidirectional"))
      (node (ref "U$3") (pin "M1") (pinfunction "P$1_M1") (pintype "passive"))
    )
    (net (code "31") (name "Net-(AV-1)") (class "Default")
      (node (ref "A") (pin "M2") (pinfunction "1_M2") (pintype "bidirectional"))
      (node (ref "U$3") (pin "M2") (pinfunction "P$1_M2") (pintype "passive"))
    )
    (net (code "32") (name "Net-(AW-1)") (class "Default")
      (node (ref "A") (pin "N1") (pinfunction "1_N1") (pintype "bidirectional"))
      (node (ref "U$3") (pin "N1") (pinfunction "P$1_N1") (pintype "passive"))
    )
    (net (code "33") (name "Net-(AX-1)") (class "Default")
      (node (ref "A") (pin "N2") (pinfunction "1_N2") (pintype "bidirectional"))
      (node (ref "U$3") (pin "N2") (pinfunction "P$1_N2") (pintype "passive"))
    )
    (net (code "34") (name "Net-(AY-1)") (class "Default")
      (node (ref "A") (pin "P1") (pinfunction "1_P1") (pintype "bidirectional"))
      (node (ref "U$3") (pin "P1") (pinfunction "P$1_P1") (pintype "passive"))
    )
    (net (code "35") (name "Net-(AZ-1)") (class "Default")
      (node (ref "A") (pin "P2") (pinfunction "1_P2") (pintype "bidirectional"))
      (node (ref "U$3") (pin "P2") (pinfunction "P$1_P2") (pintype "passive"))
    )
    (net (code "36") (name "Net-(BA-1)") (class "Default")
      (node (ref "B") (pin "A1") (pinfunction "1_A1") (pintype "bidirectional"))
      (node (ref "U$5") (pin "A1") (pinfunction "P$1_A1") (pintype "passive"))
    )
    (net (code "37") (name "Net-(BAA-1)") (class "Default")
      (node (ref "B") (pin "R1") (pinfunction "1_R1") (pintype "bidirectional"))
      (node (ref "U$5") (pin "R1") (pinfunction "P$1_R1") (pintype "passive"))
    )
    (net (code "38") (name "Net-(BAB-1)") (class "Default")
      (node (ref "B") (pin "R2") (pinfunction "1_R2") (pintype "bidirectional"))
      (node (ref "U$5") (pin "R2") (pinfunction "P$1_R2") (pintype "passive"))
    )
    (net (code "39") (name "Net-(BAC-1)") (class "Default")
      (node (ref "B") (pin "S1") (pinfunction "1_S1") (pintype "bidirectional"))
      (node (ref "U$5") (pin "S1") (pinfunction "P$1_S1") (pintype "passive"))
    )
    (net (code "40") (name "Net-(BAD-1)") (class "Default")
      (node (ref "B") (pin "S2") (pinfunction "1_S2") (pintype "bidirectional"))
      (node (ref "U$5") (pin "S2") (pinfunction "P$1_S2") (pintype "passive"))
    )
    (net (code "41") (name "Net-(BAE-1)") (class "Default")
      (node (ref "B") (pin "T1") (pinfunction "1_T1") (pintype "bidirectional"))
      (node (ref "U$5") (pin "T1") (pinfunction "P$1_T1") (pintype "passive"))
    )
    (net (code "42") (name "Net-(BAF-1)") (class "Default")
      (node (ref "B") (pin "T2") (pinfunction "1_T2") (pintype "bidirectional"))
      (node (ref "U$5") (pin "T2") (pinfunction "P$1_T2") (pintype "passive"))
    )
    (net (code "43") (name "Net-(BAG-1)") (class "Default")
      (node (ref "B") (pin "U1") (pinfunction "1_U1") (pintype "bidirectional"))
      (node (ref "U$5") (pin "U1") (pinfunction "P$1_U1") (pintype "passive"))
    )
    (net (code "44") (name "Net-(BAH-1)") (class "Default")
      (node (ref "B") (pin "U2") (pinfunction "1_U2") (pintype "bidirectional"))
      (node (ref "U$5") (pin "U2") (pinfunction "P$1_U2") (pintype "passive"))
    )
    (net (code "45") (name "Net-(BAI-1)") (class "Default")
      (node (ref "B") (pin "V1") (pinfunction "1_V1") (pintype "bidirectional"))
      (node (ref "U$5") (pin "V1") (pinfunction "P$1_V1") (pintype "passive"))
    )
    (net (code "46") (name "Net-(BAJ-1)") (class "Default")
      (node (ref "B") (pin "V2") (pinfunction "1_V2") (pintype "bidirectional"))
      (node (ref "U$5") (pin "V2") (pinfunction "P$1_V2") (pintype "passive"))
    )
    (net (code "47") (name "Net-(BC-1)") (class "Default")
      (node (ref "B") (pin "B1") (pinfunction "1_B1") (pintype "bidirectional"))
      (node (ref "U$5") (pin "B1") (pinfunction "P$1_B1") (pintype "passive"))
    )
    (net (code "48") (name "Net-(BD-1)") (class "Default")
      (node (ref "B") (pin "B2") (pinfunction "1_B2") (pintype "bidirectional"))
      (node (ref "U$5") (pin "B2") (pinfunction "P$1_B2") (pintype "passive"))
    )
    (net (code "49") (name "Net-(BE-1)") (class "Default")
      (node (ref "B") (pin "C1") (pinfunction "1_C1") (pintype "bidirectional"))
      (node (ref "U$5") (pin "C1") (pinfunction "P$1_C1") (pintype "passive"))
    )
    (net (code "50") (name "Net-(BG-1)") (class "Default")
      (node (ref "B") (pin "D1") (pinfunction "1_D1") (pintype "bidirectional"))
      (node (ref "U$5") (pin "D1") (pinfunction "P$1_D1") (pintype "passive"))
    )
    (net (code "51") (name "Net-(BH-1)") (class "Default")
      (node (ref "B") (pin "D2") (pinfunction "1_D2") (pintype "bidirectional"))
      (node (ref "U$5") (pin "D2") (pinfunction "P$1_D2") (pintype "passive"))
    )
    (net (code "52") (name "Net-(BI-1)") (class "Default")
      (node (ref "B") (pin "E1") (pinfunction "1_E1") (pintype "bidirectional"))
      (node (ref "U$5") (pin "E1") (pinfunction "P$1_E1") (pintype "passive"))
    )
    (net (code "53") (name "Net-(BJ-1)") (class "Default")
      (node (ref "B") (pin "E2") (pinfunction "1_E2") (pintype "bidirectional"))
      (node (ref "U$5") (pin "E2") (pinfunction "P$1_E2") (pintype "passive"))
    )
    (net (code "54") (name "Net-(BK-1)") (class "Default")
      (node (ref "B") (pin "F1") (pinfunction "1_F1") (pintype "bidirectional"))
      (node (ref "U$5") (pin "F1") (pinfunction "P$1_F1") (pintype "passive"))
    )
    (net (code "55") (name "Net-(BL-1)") (class "Default")
      (node (ref "B") (pin "F2") (pinfunction "1_F2") (pintype "bidirectional"))
      (node (ref "U$5") (pin "F2") (pinfunction "P$1_F2") (pintype "passive"))
    )
    (net (code "56") (name "Net-(BM-1)") (class "Default")
      (node (ref "B") (pin "H1") (pinfunction "1_H1") (pintype "bidirectional"))
      (node (ref "U$5") (pin "H1") (pinfunction "P$1_H1") (pintype "passive"))
    )
    (net (code "57") (name "Net-(BN-1)") (class "Default")
      (node (ref "B") (pin "H2") (pinfunction "1_H2") (pintype "bidirectional"))
      (node (ref "U$5") (pin "H2") (pinfunction "P$1_H2") (pintype "passive"))
    )
    (net (code "58") (name "Net-(BO-1)") (class "Default")
      (node (ref "B") (pin "J1") (pinfunction "1_J1") (pintype "bidirectional"))
      (node (ref "U$5") (pin "J1") (pinfunction "P$1_J1") (pintype "passive"))
    )
    (net (code "59") (name "Net-(BP-1)") (class "Default")
      (node (ref "B") (pin "J2") (pinfunction "1_J2") (pintype "bidirectional"))
      (node (ref "U$5") (pin "J2") (pinfunction "P$1_J2") (pintype "passive"))
    )
    (net (code "60") (name "Net-(BQ-1)") (class "Default")
      (node (ref "B") (pin "K1") (pinfunction "1_K1") (pintype "bidirectional"))
      (node (ref "U$5") (pin "K1") (pinfunction "P$1_K1") (pintype "passive"))
    )
    (net (code "61") (name "Net-(BR-1)") (class "Default")
      (node (ref "B") (pin "K2") (pinfunction "1_K2") (pintype "bidirectional"))
      (node (ref "U$5") (pin "K2") (pinfunction "P$1_K2") (pintype "passive"))
    )
    (net (code "62") (name "Net-(BS-1)") (class "Default")
      (node (ref "B") (pin "L1") (pinfunction "1_L1") (pintype "bidirectional"))
      (node (ref "U$5") (pin "L1") (pinfunction "P$1_L1") (pintype "passive"))
    )
    (net (code "63") (name "Net-(BT-1)") (class "Default")
      (node (ref "B") (pin "L2") (pinfunction "1_L2") (pintype "bidirectional"))
      (node (ref "U$5") (pin "L2") (pinfunction "P$1_L2") (pintype "passive"))
    )
    (net (code "64") (name "Net-(BU-1)") (class "Default")
      (node (ref "B") (pin "M1") (pinfunction "1_M1") (pintype "bidirectional"))
      (node (ref "U$5") (pin "M1") (pinfunction "P$1_M1") (pintype "passive"))
    )
    (net (code "65") (name "Net-(BV-1)") (class "Default")
      (node (ref "B") (pin "M2") (pinfunction "1_M2") (pintype "bidirectional"))
      (node (ref "U$5") (pin "M2") (pinfunction "P$1_M2") (pintype "passive"))
    )
    (net (code "66") (name "Net-(BW-1)") (class "Default")
      (node (ref "B") (pin "N1") (pinfunction "1_N1") (pintype "bidirectional"))
      (node (ref "U$5") (pin "N1") (pinfunction "P$1_N1") (pintype "passive"))
    )
    (net (code "67") (name "Net-(BX-1)") (class "Default")
      (node (ref "B") (pin "N2") (pinfunction "1_N2") (pintype "bidirectional"))
      (node (ref "U$5") (pin "N2") (pinfunction "P$1_N2") (pintype "passive"))
    )
    (net (code "68") (name "Net-(BY-1)") (class "Default")
      (node (ref "B") (pin "P1") (pinfunction "1_P1") (pintype "bidirectional"))
      (node (ref "U$5") (pin "P1") (pinfunction "P$1_P1") (pintype "passive"))
    )
    (net (code "69") (name "Net-(BZ-1)") (class "Default")
      (node (ref "B") (pin "P2") (pinfunction "1_P2") (pintype "bidirectional"))
      (node (ref "U$5") (pin "P2") (pinfunction "P$1_P2") (pintype "passive"))
    )
    (net (code "70") (name "Net-(SV1-Pad1)") (class "Default")
      (node (ref "SV1") (pin "1") (pinfunction "1_1") (pintype "passive"))
      (node (ref "SV1") (pin "2") (pinfunction "2_2") (pintype "passive"))
      (node (ref "SV2") (pin "1") (pinfunction "1_1") (pintype "passive"))
    )
    (net (code "71") (name "Net-(SV1-Pad3)") (class "Default")
      (node (ref "SV1") (pin "3") (pinfunction "3_3") (pintype "passive"))
      (node (ref "SV1") (pin "4") (pinfunction "4_4") (pintype "passive"))
      (node (ref "SV2") (pin "3") (pinfunction "3_3") (pintype "passive"))
    )
    (net (code "72") (name "Net-(SV1-Pad5)") (class "Default")
      (node (ref "SV1") (pin "5") (pinfunction "5_5") (pintype "passive"))
      (node (ref "SV1") (pin "6") (pinfunction "6_6") (pintype "passive"))
      (node (ref "SV2") (pin "5") (pinfunction "5_5") (pintype "passive"))
    )
    (net (code "73") (name "Net-(SV1-Pad7)") (class "Default")
      (node (ref "SV1") (pin "7") (pinfunction "7_7") (pintype "passive"))
      (node (ref "SV1") (pin "8") (pinfunction "8_8") (pintype "passive"))
      (node (ref "SV2") (pin "7") (pinfunction "7_7") (pintype "passive"))
    )
    (net (code "74") (name "Net-(SV1-Pad10)") (class "Default")
      (node (ref "SV1") (pin "10") (pinfunction "10_10") (pintype "passive"))
      (node (ref "SV1") (pin "9") (pinfunction "9_9") (pintype "passive"))
      (node (ref "SV2") (pin "9") (pinfunction "9_9") (pintype "passive"))
    )
    (net (code "75") (name "Net-(SV1-Pad11)") (class "Default")
      (node (ref "SV1") (pin "11") (pinfunction "11_11") (pintype "passive"))
      (node (ref "SV1") (pin "12") (pinfunction "12_12") (pintype "passive"))
      (node (ref "SV2") (pin "11") (pinfunction "11_11") (pintype "passive"))
    )
    (net (code "76") (name "Net-(SV1-Pad13)") (class "Default")
      (node (ref "SV1") (pin "13") (pinfunction "13_13") (pintype "passive"))
      (node (ref "SV1") (pin "14") (pinfunction "14_14") (pintype "passive"))
      (node (ref "SV2") (pin "13") (pinfunction "13_13") (pintype "passive"))
    )
    (net (code "77") (name "Net-(SV1-Pad15)") (class "Default")
      (node (ref "SV1") (pin "15") (pinfunction "15_15") (pintype "passive"))
      (node (ref "SV1") (pin "16") (pinfunction "16_16") (pintype "passive"))
      (node (ref "SV2") (pin "15") (pinfunction "15_15") (pintype "passive"))
    )
    (net (code "78") (name "Net-(SV1-Pad17)") (class "Default")
      (node (ref "SV1") (pin "17") (pinfunction "17_17") (pintype "passive"))
      (node (ref "SV1") (pin "18") (pinfunction "18_18") (pintype "passive"))
      (node (ref "SV2") (pin "17") (pinfunction "17_17") (pintype "passive"))
    )
    (net (code "79") (name "Net-(SV1-Pad19)") (class "Default")
      (node (ref "SV1") (pin "19") (pinfunction "19_19") (pintype "passive"))
      (node (ref "SV1") (pin "20") (pinfunction "20_20") (pintype "passive"))
      (node (ref "SV2") (pin "19") (pinfunction "19_19") (pintype "passive"))
    )
    (net (code "80") (name "Net-(SV1-Pad21)") (class "Default")
      (node (ref "SV1") (pin "21") (pinfunction "21_21") (pintype "passive"))
      (node (ref "SV1") (pin "22") (pinfunction "22_22") (pintype "passive"))
      (node (ref "SV2") (pin "21") (pinfunction "21_21") (pintype "passive"))
    )
    (net (code "81") (name "Net-(SV1-Pad23)") (class "Default")
      (node (ref "SV1") (pin "23") (pinfunction "23_23") (pintype "passive"))
      (node (ref "SV1") (pin "24") (pinfunction "24_24") (pintype "passive"))
      (node (ref "SV2") (pin "23") (pinfunction "23_23") (pintype "passive"))
    )
    (net (code "82") (name "Net-(SV1-Pad25)") (class "Default")
      (node (ref "SV1") (pin "25") (pinfunction "25_25") (pintype "passive"))
      (node (ref "SV1") (pin "26") (pinfunction "26_26") (pintype "passive"))
      (node (ref "SV2") (pin "25") (pinfunction "25_25") (pintype "passive"))
    )
    (net (code "83") (name "Net-(SV1-Pad27)") (class "Default")
      (node (ref "SV1") (pin "27") (pinfunction "27_27") (pintype "passive"))
      (node (ref "SV1") (pin "28") (pinfunction "28_28") (pintype "passive"))
      (node (ref "SV2") (pin "27") (pinfunction "27_27") (pintype "passive"))
    )
    (net (code "84") (name "Net-(SV1-Pad29)") (class "Default")
      (node (ref "SV1") (pin "29") (pinfunction "29_29") (pintype "passive"))
      (node (ref "SV1") (pin "30") (pinfunction "30_30") (pintype "passive"))
      (node (ref "SV2") (pin "29") (pinfunction "29_29") (pintype "passive"))
    )
    (net (code "85") (name "Net-(SV1-Pad31)") (class "Default")
      (node (ref "SV1") (pin "31") (pinfunction "31_31") (pintype "passive"))
      (node (ref "SV1") (pin "32") (pinfunction "32_32") (pintype "passive"))
      (node (ref "SV2") (pin "31") (pinfunction "31_31") (pintype "passive"))
    )
    (net (code "86") (name "Net-(SV1-Pad33)") (class "Default")
      (node (ref "SV1") (pin "33") (pinfunction "33_33") (pintype "passive"))
      (node (ref "SV1") (pin "34") (pinfunction "34_34") (pintype "passive"))
      (node (ref "SV2") (pin "33") (pinfunction "33_33") (pintype "passive"))
    )
    (net (code "87") (name "Net-(SV1-Pad35)") (class "Default")
      (node (ref "SV1") (pin "35") (pinfunction "35_35") (pintype "passive"))
      (node (ref "SV1") (pin "36") (pinfunction "36_36") (pintype "passive"))
      (node (ref "SV2") (pin "35") (pinfunction "35_35") (pintype "passive"))
    )
    (net (code "88") (name "Net-(SV1-Pad37)") (class "Default")
      (node (ref "SV1") (pin "37") (pinfunction "37_37") (pintype "passive"))
      (node (ref "SV1") (pin "38") (pinfunction "38_38") (pintype "passive"))
      (node (ref "SV2") (pin "37") (pinfunction "37_37") (pintype "passive"))
    )
    (net (code "89") (name "Net-(SV1-Pad39)") (class "Default")
      (node (ref "SV1") (pin "39") (pinfunction "39_39") (pintype "passive"))
      (node (ref "SV1") (pin "40") (pinfunction "40_40") (pintype "passive"))
      (node (ref "SV2") (pin "39") (pinfunction "39_39") (pintype "passive"))
    )
    (net (code "90") (name "Net-(SV3-Pad1)") (class "Default")
      (node (ref "SV3") (pin "1") (pinfunction "1_1") (pintype "passive"))
      (node (ref "SV3") (pin "2") (pinfunction "2_2") (pintype "passive"))
      (node (ref "SV4") (pin "2") (pinfunction "2_2") (pintype "passive"))
    )
    (net (code "91") (name "Net-(SV3-Pad3)") (class "Default")
      (node (ref "SV3") (pin "3") (pinfunction "3_3") (pintype "passive"))
      (node (ref "SV3") (pin "4") (pinfunction "4_4") (pintype "passive"))
      (node (ref "SV4") (pin "4") (pinfunction "4_4") (pintype "passive"))
    )
    (net (code "92") (name "Net-(SV3-Pad5)") (class "Default")
      (node (ref "SV3") (pin "5") (pinfunction "5_5") (pintype "passive"))
      (node (ref "SV3") (pin "6") (pinfunction "6_6") (pintype "passive"))
      (node (ref "SV4") (pin "6") (pinfunction "6_6") (pintype "passive"))
    )
    (net (code "93") (name "Net-(SV3-Pad7)") (class "Default")
      (node (ref "SV3") (pin "7") (pinfunction "7_7") (pintype "passive"))
      (node (ref "SV3") (pin "8") (pinfunction "8_8") (pintype "passive"))
      (node (ref "SV4") (pin "8") (pinfunction "8_8") (pintype "passive"))
    )
    (net (code "94") (name "Net-(SV3-Pad10)") (class "Default")
      (node (ref "SV3") (pin "10") (pinfunction "10_10") (pintype "passive"))
      (node (ref "SV3") (pin "9") (pinfunction "9_9") (pintype "passive"))
      (node (ref "SV4") (pin "10") (pinfunction "10_10") (pintype "passive"))
    )
    (net (code "95") (name "Net-(SV3-Pad11)") (class "Default")
      (node (ref "SV3") (pin "11") (pinfunction "11_11") (pintype "passive"))
      (node (ref "SV3") (pin "12") (pinfunction "12_12") (pintype "passive"))
      (node (ref "SV4") (pin "12") (pinfunction "12_12") (pintype "passive"))
    )
    (net (code "96") (name "Net-(SV3-Pad13)") (class "Default")
      (node (ref "SV3") (pin "13") (pinfunction "13_13") (pintype "passive"))
      (node (ref "SV3") (pin "14") (pinfunction "14_14") (pintype "passive"))
      (node (ref "SV4") (pin "14") (pinfunction "14_14") (pintype "passive"))
    )
    (net (code "97") (name "Net-(SV3-Pad15)") (class "Default")
      (node (ref "SV3") (pin "15") (pinfunction "15_15") (pintype "passive"))
      (node (ref "SV3") (pin "16") (pinfunction "16_16") (pintype "passive"))
      (node (ref "SV4") (pin "16") (pinfunction "16_16") (pintype "passive"))
    )
    (net (code "98") (name "Net-(SV3-Pad17)") (class "Default")
      (node (ref "SV3") (pin "17") (pinfunction "17_17") (pintype "passive"))
      (node (ref "SV3") (pin "18") (pinfunction "18_18") (pintype "passive"))
      (node (ref "SV4") (pin "18") (pinfunction "18_18") (pintype "passive"))
    )
    (net (code "99") (name "Net-(SV3-Pad19)") (class "Default")
      (node (ref "SV3") (pin "19") (pinfunction "19_19") (pintype "passive"))
      (node (ref "SV3") (pin "20") (pinfunction "20_20") (pintype "passive"))
      (node (ref "SV4") (pin "20") (pinfunction "20_20") (pintype "passive"))
    )
    (net (code "100") (name "Net-(SV3-Pad21)") (class "Default")
      (node (ref "SV3") (pin "21") (pinfunction "21_21") (pintype "passive"))
      (node (ref "SV3") (pin "22") (pinfunction "22_22") (pintype "passive"))
      (node (ref "SV4") (pin "22") (pinfunction "22_22") (pintype "passive"))
    )
    (net (code "101") (name "Net-(SV3-Pad23)") (class "Default")
      (node (ref "SV3") (pin "23") (pinfunction "23_23") (pintype "passive"))
      (node (ref "SV3") (pin "24") (pinfunction "24_24") (pintype "passive"))
      (node (ref "SV4") (pin "24") (pinfunction "24_24") (pintype "passive"))
    )
    (net (code "102") (name "Net-(SV3-Pad25)") (class "Default")
      (node (ref "SV3") (pin "25") (pinfunction "25_25") (pintype "passive"))
      (node (ref "SV3") (pin "26") (pinfunction "26_26") (pintype "passive"))
      (node (ref "SV4") (pin "26") (pinfunction "26_26") (pintype "passive"))
    )
    (net (code "103") (name "Net-(SV3-Pad27)") (class "Default")
      (node (ref "SV3") (pin "27") (pinfunction "27_27") (pintype "passive"))
      (node (ref "SV3") (pin "28") (pinfunction "28_28") (pintype "passive"))
      (node (ref "SV4") (pin "28") (pinfunction "28_28") (pintype "passive"))
    )
    (net (code "104") (name "Net-(SV3-Pad29)") (class "Default")
      (node (ref "SV3") (pin "29") (pinfunction "29_29") (pintype "passive"))
      (node (ref "SV3") (pin "30") (pinfunction "30_30") (pintype "passive"))
      (node (ref "SV4") (pin "30") (pinfunction "30_30") (pintype "passive"))
    )
    (net (code "105") (name "Net-(SV3-Pad31)") (class "Default")
      (node (ref "SV3") (pin "31") (pinfunction "31_31") (pintype "passive"))
      (node (ref "SV3") (pin "32") (pinfunction "32_32") (pintype "passive"))
      (node (ref "SV4") (pin "32") (pinfunction "32_32") (pintype "passive"))
    )
    (net (code "106") (name "Net-(SV3-Pad33)") (class "Default")
      (node (ref "SV3") (pin "33") (pinfunction "33_33") (pintype "passive"))
      (node (ref "SV3") (pin "34") (pinfunction "34_34") (pintype "passive"))
      (node (ref "SV4") (pin "34") (pinfunction "34_34") (pintype "passive"))
    )
    (net (code "107") (name "Net-(SV3-Pad35)") (class "Default")
      (node (ref "SV3") (pin "35") (pinfunction "35_35") (pintype "passive"))
      (node (ref "SV3") (pin "36") (pinfunction "36_36") (pintype "passive"))
      (node (ref "SV4") (pin "36") (pinfunction "36_36") (pintype "passive"))
    )
    (net (code "108") (name "Net-(SV3-Pad37)") (class "Default")
      (node (ref "SV3") (pin "37") (pinfunction "37_37") (pintype "passive"))
      (node (ref "SV3") (pin "38") (pinfunction "38_38") (pintype "passive"))
      (node (ref "SV4") (pin "38") (pinfunction "38_38") (pintype "passive"))
    )
    (net (code "109") (name "Net-(SV3-Pad39)") (class "Default")
      (node (ref "SV3") (pin "39") (pinfunction "39_39") (pintype "passive"))
      (node (ref "SV3") (pin "40") (pinfunction "40_40") (pintype "passive"))
      (node (ref "SV4") (pin "40") (pinfunction "40_40") (pintype "passive"))
    )
    (net (code "110") (name "Net-(SV5-Pad1)") (class "Default")
      (node (ref "SV5") (pin "1") (pinfunction "1_1") (pintype "passive"))
      (node (ref "SV5") (pin "2") (pinfunction "2_2") (pintype "passive"))
      (node (ref "SV6") (pin "2") (pinfunction "2_2") (pintype "passive"))
    )
    (net (code "111") (name "Net-(SV5-Pad3)") (class "Default")
      (node (ref "SV5") (pin "3") (pinfunction "3_3") (pintype "passive"))
      (node (ref "SV5") (pin "4") (pinfunction "4_4") (pintype "passive"))
      (node (ref "SV6") (pin "4") (pinfunction "4_4") (pintype "passive"))
    )
    (net (code "112") (name "Net-(SV5-Pad5)") (class "Default")
      (node (ref "SV5") (pin "5") (pinfunction "5_5") (pintype "passive"))
      (node (ref "SV5") (pin "6") (pinfunction "6_6") (pintype "passive"))
      (node (ref "SV6") (pin "6") (pinfunction "6_6") (pintype "passive"))
    )
    (net (code "113") (name "Net-(SV5-Pad7)") (class "Default")
      (node (ref "SV5") (pin "7") (pinfunction "7_7") (pintype "passive"))
      (node (ref "SV5") (pin "8") (pinfunction "8_8") (pintype "passive"))
      (node (ref "SV6") (pin "8") (pinfunction "8_8") (pintype "passive"))
    )
    (net (code "114") (name "Net-(SV5-Pad10)") (class "Default")
      (node (ref "SV5") (pin "10") (pinfunction "10_10") (pintype "passive"))
      (node (ref "SV5") (pin "9") (pinfunction "9_9") (pintype "passive"))
      (node (ref "SV6") (pin "10") (pinfunction "10_10") (pintype "passive"))
    )
    (net (code "115") (name "Net-(SV5-Pad11)") (class "Default")
      (node (ref "SV5") (pin "11") (pinfunction "11_11") (pintype "passive"))
      (node (ref "SV5") (pin "12") (pinfunction "12_12") (pintype "passive"))
      (node (ref "SV6") (pin "12") (pinfunction "12_12") (pintype "passive"))
    )
    (net (code "116") (name "Net-(SV5-Pad13)") (class "Default")
      (node (ref "SV5") (pin "13") (pinfunction "13_13") (pintype "passive"))
      (node (ref "SV5") (pin "14") (pinfunction "14_14") (pintype "passive"))
      (node (ref "SV6") (pin "14") (pinfunction "14_14") (pintype "passive"))
    )
    (net (code "117") (name "Net-(SV5-Pad15)") (class "Default")
      (node (ref "SV5") (pin "15") (pinfunction "15_15") (pintype "passive"))
      (node (ref "SV5") (pin "16") (pinfunction "16_16") (pintype "passive"))
      (node (ref "SV6") (pin "16") (pinfunction "16_16") (pintype "passive"))
    )
    (net (code "118") (name "Net-(SV5-Pad17)") (class "Default")
      (node (ref "SV5") (pin "17") (pinfunction "17_17") (pintype "passive"))
      (node (ref "SV5") (pin "18") (pinfunction "18_18") (pintype "passive"))
      (node (ref "SV6") (pin "18") (pinfunction "18_18") (pintype "passive"))
    )
    (net (code "119") (name "Net-(SV5-Pad19)") (class "Default")
      (node (ref "SV5") (pin "19") (pinfunction "19_19") (pintype "passive"))
      (node (ref "SV5") (pin "20") (pinfunction "20_20") (pintype "passive"))
      (node (ref "SV6") (pin "20") (pinfunction "20_20") (pintype "passive"))
    )
    (net (code "120") (name "Net-(SV5-Pad21)") (class "Default")
      (node (ref "SV5") (pin "21") (pinfunction "21_21") (pintype "passive"))
      (node (ref "SV5") (pin "22") (pinfunction "22_22") (pintype "passive"))
      (node (ref "SV6") (pin "22") (pinfunction "22_22") (pintype "passive"))
    )
    (net (code "121") (name "Net-(SV5-Pad23)") (class "Default")
      (node (ref "SV5") (pin "23") (pinfunction "23_23") (pintype "passive"))
      (node (ref "SV5") (pin "24") (pinfunction "24_24") (pintype "passive"))
      (node (ref "SV6") (pin "24") (pinfunction "24_24") (pintype "passive"))
    )
    (net (code "122") (name "Net-(SV5-Pad25)") (class "Default")
      (node (ref "SV5") (pin "25") (pinfunction "25_25") (pintype "passive"))
      (node (ref "SV5") (pin "26") (pinfunction "26_26") (pintype "passive"))
      (node (ref "SV6") (pin "26") (pinfunction "26_26") (pintype "passive"))
    )
    (net (code "123") (name "Net-(SV5-Pad27)") (class "Default")
      (node (ref "SV5") (pin "27") (pinfunction "27_27") (pintype "passive"))
      (node (ref "SV5") (pin "28") (pinfunction "28_28") (pintype "passive"))
      (node (ref "SV6") (pin "28") (pinfunction "28_28") (pintype "passive"))
    )
    (net (code "124") (name "Net-(SV5-Pad29)") (class "Default")
      (node (ref "SV5") (pin "29") (pinfunction "29_29") (pintype "passive"))
      (node (ref "SV5") (pin "30") (pinfunction "30_30") (pintype "passive"))
      (node (ref "SV6") (pin "30") (pinfunction "30_30") (pintype "passive"))
    )
    (net (code "125") (name "Net-(SV5-Pad31)") (class "Default")
      (node (ref "SV5") (pin "31") (pinfunction "31_31") (pintype "passive"))
      (node (ref "SV5") (pin "32") (pinfunction "32_32") (pintype "passive"))
      (node (ref "SV6") (pin "32") (pinfunction "32_32") (pintype "passive"))
    )
    (net (code "126") (name "Net-(SV5-Pad33)") (class "Default")
      (node (ref "SV5") (pin "33") (pinfunction "33_33") (pintype "passive"))
      (node (ref "SV5") (pin "34") (pinfunction "34_34") (pintype "passive"))
      (node (ref "SV6") (pin "34") (pinfunction "34_34") (pintype "passive"))
    )
    (net (code "127") (name "Net-(SV5-Pad35)") (class "Default")
      (node (ref "SV5") (pin "35") (pinfunction "35_35") (pintype "passive"))
      (node (ref "SV5") (pin "36") (pinfunction "36_36") (pintype "passive"))
      (node (ref "SV6") (pin "36") (pinfunction "36_36") (pintype "passive"))
    )
    (net (code "128") (name "Net-(SV7-Pad1)") (class "Default")
      (node (ref "SV7") (pin "1") (pinfunction "1_1") (pintype "passive"))
      (node (ref "SV7") (pin "2") (pinfunction "2_2") (pintype "passive"))
      (node (ref "SV8") (pin "1") (pinfunction "1_1") (pintype "passive"))
    )
    (net (code "129") (name "Net-(SV7-Pad3)") (class "Default")
      (node (ref "SV7") (pin "3") (pinfunction "3_3") (pintype "passive"))
      (node (ref "SV7") (pin "4") (pinfunction "4_4") (pintype "passive"))
      (node (ref "SV8") (pin "3") (pinfunction "3_3") (pintype "passive"))
    )
    (net (code "130") (name "Net-(SV7-Pad5)") (class "Default")
      (node (ref "SV7") (pin "5") (pinfunction "5_5") (pintype "passive"))
      (node (ref "SV7") (pin "6") (pinfunction "6_6") (pintype "passive"))
      (node (ref "SV8") (pin "5") (pinfunction "5_5") (pintype "passive"))
    )
    (net (code "131") (name "Net-(SV7-Pad7)") (class "Default")
      (node (ref "SV7") (pin "7") (pinfunction "7_7") (pintype "passive"))
      (node (ref "SV7") (pin "8") (pinfunction "8_8") (pintype "passive"))
      (node (ref "SV8") (pin "7") (pinfunction "7_7") (pintype "passive"))
    )
    (net (code "132") (name "Net-(SV7-Pad10)") (class "Default")
      (node (ref "SV7") (pin "10") (pinfunction "10_10") (pintype "passive"))
      (node (ref "SV7") (pin "9") (pinfunction "9_9") (pintype "passive"))
      (node (ref "SV8") (pin "9") (pinfunction "9_9") (pintype "passive"))
    )
    (net (code "133") (name "Net-(SV7-Pad11)") (class "Default")
      (node (ref "SV7") (pin "11") (pinfunction "11_11") (pintype "passive"))
      (node (ref "SV7") (pin "12") (pinfunction "12_12") (pintype "passive"))
      (node (ref "SV8") (pin "11") (pinfunction "11_11") (pintype "passive"))
    )
    (net (code "134") (name "Net-(SV7-Pad13)") (class "Default")
      (node (ref "SV7") (pin "13") (pinfunction "13_13") (pintype "passive"))
      (node (ref "SV7") (pin "14") (pinfunction "14_14") (pintype "passive"))
      (node (ref "SV8") (pin "13") (pinfunction "13_13") (pintype "passive"))
    )
    (net (code "135") (name "Net-(SV7-Pad15)") (class "Default")
      (node (ref "SV7") (pin "15") (pinfunction "15_15") (pintype "passive"))
      (node (ref "SV7") (pin "16") (pinfunction "16_16") (pintype "passive"))
      (node (ref "SV8") (pin "15") (pinfunction "15_15") (pintype "passive"))
    )
    (net (code "136") (name "Net-(SV7-Pad17)") (class "Default")
      (node (ref "SV7") (pin "17") (pinfunction "17_17") (pintype "passive"))
      (node (ref "SV7") (pin "18") (pinfunction "18_18") (pintype "passive"))
      (node (ref "SV8") (pin "17") (pinfunction "17_17") (pintype "passive"))
    )
    (net (code "137") (name "Net-(SV7-Pad19)") (class "Default")
      (node (ref "SV7") (pin "19") (pinfunction "19_19") (pintype "passive"))
      (node (ref "SV7") (pin "20") (pinfunction "20_20") (pintype "passive"))
      (node (ref "SV8") (pin "19") (pinfunction "19_19") (pintype "passive"))
    )
    (net (code "138") (name "Net-(SV7-Pad21)") (class "Default")
      (node (ref "SV7") (pin "21") (pinfunction "21_21") (pintype "passive"))
      (node (ref "SV7") (pin "22") (pinfunction "22_22") (pintype "passive"))
      (node (ref "SV8") (pin "21") (pinfunction "21_21") (pintype "passive"))
    )
    (net (code "139") (name "Net-(SV7-Pad23)") (class "Default")
      (node (ref "SV7") (pin "23") (pinfunction "23_23") (pintype "passive"))
      (node (ref "SV7") (pin "24") (pinfunction "24_24") (pintype "passive"))
      (node (ref "SV8") (pin "23") (pinfunction "23_23") (pintype "passive"))
    )
    (net (code "140") (name "Net-(SV7-Pad25)") (class "Default")
      (node (ref "SV7") (pin "25") (pinfunction "25_25") (pintype "passive"))
      (node (ref "SV7") (pin "26") (pinfunction "26_26") (pintype "passive"))
      (node (ref "SV8") (pin "25") (pinfunction "25_25") (pintype "passive"))
    )
    (net (code "141") (name "Net-(SV7-Pad27)") (class "Default")
      (node (ref "SV7") (pin "27") (pinfunction "27_27") (pintype "passive"))
      (node (ref "SV7") (pin "28") (pinfunction "28_28") (pintype "passive"))
      (node (ref "SV8") (pin "27") (pinfunction "27_27") (pintype "passive"))
    )
    (net (code "142") (name "Net-(SV7-Pad29)") (class "Default")
      (node (ref "SV7") (pin "29") (pinfunction "29_29") (pintype "passive"))
      (node (ref "SV7") (pin "30") (pinfunction "30_30") (pintype "passive"))
      (node (ref "SV8") (pin "29") (pinfunction "29_29") (pintype "passive"))
    )
    (net (code "143") (name "Net-(SV7-Pad31)") (class "Default")
      (node (ref "SV7") (pin "31") (pinfunction "31_31") (pintype "passive"))
      (node (ref "SV7") (pin "32") (pinfunction "32_32") (pintype "passive"))
      (node (ref "SV8") (pin "31") (pinfunction "31_31") (pintype "passive"))
    )
    (net (code "144") (name "Net-(SV7-Pad33)") (class "Default")
      (node (ref "SV7") (pin "33") (pinfunction "33_33") (pintype "passive"))
      (node (ref "SV7") (pin "34") (pinfunction "34_34") (pintype "passive"))
      (node (ref "SV8") (pin "33") (pinfunction "33_33") (pintype "passive"))
    )
    (net (code "145") (name "Net-(SV7-Pad35)") (class "Default")
      (node (ref "SV7") (pin "35") (pinfunction "35_35") (pintype "passive"))
      (node (ref "SV7") (pin "36") (pinfunction "36_36") (pintype "passive"))
      (node (ref "SV8") (pin "35") (pinfunction "35_35") (pintype "passive"))
    )
    (net (code "146") (name "Net-(SV10-Pad1)") (class "Default")
      (node (ref "SV10") (pin "1") (pinfunction "1_1") (pintype "passive"))
      (node (ref "SV9") (pin "1") (pinfunction "1_1") (pintype "passive"))
      (node (ref "SV9") (pin "2") (pinfunction "2_2") (pintype "passive"))
    )
    (net (code "147") (name "Net-(SV10-Pad3)") (class "Default")
      (node (ref "SV10") (pin "3") (pinfunction "3_3") (pintype "passive"))
      (node (ref "SV9") (pin "3") (pinfunction "3_3") (pintype "passive"))
      (node (ref "SV9") (pin "4") (pinfunction "4_4") (pintype "passive"))
    )
    (net (code "148") (name "Net-(SV10-Pad5)") (class "Default")
      (node (ref "SV10") (pin "5") (pinfunction "5_5") (pintype "passive"))
      (node (ref "SV9") (pin "5") (pinfunction "5_5") (pintype "passive"))
      (node (ref "SV9") (pin "6") (pinfunction "6_6") (pintype "passive"))
    )
    (net (code "149") (name "Net-(SV10-Pad7)") (class "Default")
      (node (ref "SV10") (pin "7") (pinfunction "7_7") (pintype "passive"))
      (node (ref "SV9") (pin "7") (pinfunction "7_7") (pintype "passive"))
      (node (ref "SV9") (pin "8") (pinfunction "8_8") (pintype "passive"))
    )
    (net (code "150") (name "Net-(SV10-Pad9)") (class "Default")
      (node (ref "SV10") (pin "9") (pinfunction "9_9") (pintype "passive"))
      (node (ref "SV9") (pin "10") (pinfunction "10_10") (pintype "passive"))
      (node (ref "SV9") (pin "9") (pinfunction "9_9") (pintype "passive"))
    )
    (net (code "151") (name "Net-(SV10-Pad11)") (class "Default")
      (node (ref "SV10") (pin "11") (pinfunction "11_11") (pintype "passive"))
      (node (ref "SV9") (pin "11") (pinfunction "11_11") (pintype "passive"))
      (node (ref "SV9") (pin "12") (pinfunction "12_12") (pintype "passive"))
    )
    (net (code "152") (name "Net-(SV10-Pad13)") (class "Default")
      (node (ref "SV10") (pin "13") (pinfunction "13_13") (pintype "passive"))
      (node (ref "SV9") (pin "13") (pinfunction "13_13") (pintype "passive"))
      (node (ref "SV9") (pin "14") (pinfunction "14_14") (pintype "passive"))
    )
    (net (code "153") (name "Net-(SV10-Pad15)") (class "Default")
      (node (ref "SV10") (pin "15") (pinfunction "15_15") (pintype "passive"))
      (node (ref "SV9") (pin "15") (pinfunction "15_15") (pintype "passive"))
      (node (ref "SV9") (pin "16") (pinfunction "16_16") (pintype "passive"))
    )
    (net (code "154") (name "Net-(SV10-Pad17)") (class "Default")
      (node (ref "SV10") (pin "17") (pinfunction "17_17") (pintype "passive"))
      (node (ref "SV9") (pin "17") (pinfunction "17_17") (pintype "passive"))
      (node (ref "SV9") (pin "18") (pinfunction "18_18") (pintype "passive"))
    )
    (net (code "155") (name "Net-(SV10-Pad19)") (class "Default")
      (node (ref "SV10") (pin "19") (pinfunction "19_19") (pintype "passive"))
      (node (ref "SV9") (pin "19") (pinfunction "19_19") (pintype "passive"))
      (node (ref "SV9") (pin "20") (pinfunction "20_20") (pintype "passive"))
    )
    (net (code "156") (name "Net-(SV10-Pad21)") (class "Default")
      (node (ref "SV10") (pin "21") (pinfunction "21_21") (pintype "passive"))
      (node (ref "SV9") (pin "21") (pinfunction "21_21") (pintype "passive"))
      (node (ref "SV9") (pin "22") (pinfunction "22_22") (pintype "passive"))
    )
    (net (code "157") (name "Net-(SV10-Pad23)") (class "Default")
      (node (ref "SV10") (pin "23") (pinfunction "23_23") (pintype "passive"))
      (node (ref "SV9") (pin "23") (pinfunction "23_23") (pintype "passive"))
      (node (ref "SV9") (pin "24") (pinfunction "24_24") (pintype "passive"))
    )
    (net (code "158") (name "Net-(SV10-Pad25)") (class "Default")
      (node (ref "SV10") (pin "25") (pinfunction "25_25") (pintype "passive"))
      (node (ref "SV9") (pin "25") (pinfunction "25_25") (pintype "passive"))
      (node (ref "SV9") (pin "26") (pinfunction "26_26") (pintype "passive"))
    )
    (net (code "159") (name "Net-(SV10-Pad27)") (class "Default")
      (node (ref "SV10") (pin "27") (pinfunction "27_27") (pintype "passive"))
      (node (ref "SV9") (pin "27") (pinfunction "27_27") (pintype "passive"))
      (node (ref "SV9") (pin "28") (pinfunction "28_28") (pintype "passive"))
    )
    (net (code "160") (name "Net-(SV10-Pad29)") (class "Default")
      (node (ref "SV10") (pin "29") (pinfunction "29_29") (pintype "passive"))
      (node (ref "SV9") (pin "29") (pinfunction "29_29") (pintype "passive"))
      (node (ref "SV9") (pin "30") (pinfunction "30_30") (pintype "passive"))
    )
    (net (code "161") (name "Net-(SV10-Pad31)") (class "Default")
      (node (ref "SV10") (pin "31") (pinfunction "31_31") (pintype "passive"))
      (node (ref "SV9") (pin "31") (pinfunction "31_31") (pintype "passive"))
      (node (ref "SV9") (pin "32") (pinfunction "32_32") (pintype "passive"))
    )
    (net (code "162") (name "Net-(SV10-Pad33)") (class "Default")
      (node (ref "SV10") (pin "33") (pinfunction "33_33") (pintype "passive"))
      (node (ref "SV9") (pin "33") (pinfunction "33_33") (pintype "passive"))
      (node (ref "SV9") (pin "34") (pinfunction "34_34") (pintype "passive"))
    )
    (net (code "163") (name "Net-(SV10-Pad35)") (class "Default")
      (node (ref "SV10") (pin "35") (pinfunction "35_35") (pintype "passive"))
      (node (ref "SV9") (pin "35") (pinfunction "35_35") (pintype "passive"))
      (node (ref "SV9") (pin "36") (pinfunction "36_36") (pintype "passive"))
    )
    (net (code "164") (name "Net-(SV11-Pad1)") (class "Default")
      (node (ref "SV11") (pin "1") (pinfunction "1_1") (pintype "passive"))
      (node (ref "SV11") (pin "2") (pinfunction "2_2") (pintype "passive"))
      (node (ref "SV12") (pin "1") (pinfunction "1_1") (pintype "passive"))
    )
    (net (code "165") (name "Net-(SV11-Pad3)") (class "Default")
      (node (ref "SV11") (pin "3") (pinfunction "3_3") (pintype "passive"))
      (node (ref "SV11") (pin "4") (pinfunction "4_4") (pintype "passive"))
      (node (ref "SV12") (pin "3") (pinfunction "3_3") (pintype "passive"))
    )
    (net (code "166") (name "Net-(SV11-Pad5)") (class "Default")
      (node (ref "SV11") (pin "5") (pinfunction "5_5") (pintype "passive"))
      (node (ref "SV11") (pin "6") (pinfunction "6_6") (pintype "passive"))
      (node (ref "SV12") (pin "5") (pinfunction "5_5") (pintype "passive"))
    )
    (net (code "167") (name "Net-(SV11-Pad7)") (class "Default")
      (node (ref "SV11") (pin "7") (pinfunction "7_7") (pintype "passive"))
      (node (ref "SV11") (pin "8") (pinfunction "8_8") (pintype "passive"))
      (node (ref "SV12") (pin "7") (pinfunction "7_7") (pintype "passive"))
    )
    (net (code "168") (name "Net-(SV11-Pad10)") (class "Default")
      (node (ref "SV11") (pin "10") (pinfunction "10_10") (pintype "passive"))
      (node (ref "SV11") (pin "9") (pinfunction "9_9") (pintype "passive"))
      (node (ref "SV12") (pin "9") (pinfunction "9_9") (pintype "passive"))
    )
    (net (code "169") (name "Net-(SV11-Pad11)") (class "Default")
      (node (ref "SV11") (pin "11") (pinfunction "11_11") (pintype "passive"))
      (node (ref "SV11") (pin "12") (pinfunction "12_12") (pintype "passive"))
      (node (ref "SV12") (pin "11") (pinfunction "11_11") (pintype "passive"))
    )
    (net (code "170") (name "Net-(SV11-Pad13)") (class "Default")
      (node (ref "SV11") (pin "13") (pinfunction "13_13") (pintype "passive"))
      (node (ref "SV11") (pin "14") (pinfunction "14_14") (pintype "passive"))
      (node (ref "SV12") (pin "13") (pinfunction "13_13") (pintype "passive"))
    )
    (net (code "171") (name "Net-(SV11-Pad15)") (class "Default")
      (node (ref "SV11") (pin "15") (pinfunction "15_15") (pintype "passive"))
      (node (ref "SV11") (pin "16") (pinfunction "16_16") (pintype "passive"))
      (node (ref "SV12") (pin "15") (pinfunction "15_15") (pintype "passive"))
    )
    (net (code "172") (name "Net-(SV11-Pad17)") (class "Default")
      (node (ref "SV11") (pin "17") (pinfunction "17_17") (pintype "passive"))
      (node (ref "SV11") (pin "18") (pinfunction "18_18") (pintype "passive"))
      (node (ref "SV12") (pin "17") (pinfunction "17_17") (pintype "passive"))
    )
    (net (code "173") (name "Net-(SV11-Pad19)") (class "Default")
      (node (ref "SV11") (pin "19") (pinfunction "19_19") (pintype "passive"))
      (node (ref "SV11") (pin "20") (pinfunction "20_20") (pintype "passive"))
      (node (ref "SV12") (pin "19") (pinfunction "19_19") (pintype "passive"))
    )
    (net (code "174") (name "Net-(SV11-Pad21)") (class "Default")
      (node (ref "SV11") (pin "21") (pinfunction "21_21") (pintype "passive"))
      (node (ref "SV11") (pin "22") (pinfunction "22_22") (pintype "passive"))
      (node (ref "SV12") (pin "21") (pinfunction "21_21") (pintype "passive"))
    )
    (net (code "175") (name "Net-(SV11-Pad23)") (class "Default")
      (node (ref "SV11") (pin "23") (pinfunction "23_23") (pintype "passive"))
      (node (ref "SV11") (pin "24") (pinfunction "24_24") (pintype "passive"))
      (node (ref "SV12") (pin "23") (pinfunction "23_23") (pintype "passive"))
    )
    (net (code "176") (name "Net-(SV11-Pad25)") (class "Default")
      (node (ref "SV11") (pin "25") (pinfunction "25_25") (pintype "passive"))
      (node (ref "SV11") (pin "26") (pinfunction "26_26") (pintype "passive"))
      (node (ref "SV12") (pin "25") (pinfunction "25_25") (pintype "passive"))
    )
    (net (code "177") (name "Net-(SV11-Pad27)") (class "Default")
      (node (ref "SV11") (pin "27") (pinfunction "27_27") (pintype "passive"))
      (node (ref "SV11") (pin "28") (pinfunction "28_28") (pintype "passive"))
      (node (ref "SV12") (pin "27") (pinfunction "27_27") (pintype "passive"))
    )
    (net (code "178") (name "Net-(SV11-Pad29)") (class "Default")
      (node (ref "SV11") (pin "29") (pinfunction "29_29") (pintype "passive"))
      (node (ref "SV11") (pin "30") (pinfunction "30_30") (pintype "passive"))
      (node (ref "SV12") (pin "29") (pinfunction "29_29") (pintype "passive"))
    )
    (net (code "179") (name "Net-(SV11-Pad31)") (class "Default")
      (node (ref "SV11") (pin "31") (pinfunction "31_31") (pintype "passive"))
      (node (ref "SV11") (pin "32") (pinfunction "32_32") (pintype "passive"))
      (node (ref "SV12") (pin "31") (pinfunction "31_31") (pintype "passive"))
    )
    (net (code "180") (name "Net-(SV11-Pad33)") (class "Default")
      (node (ref "SV11") (pin "33") (pinfunction "33_33") (pintype "passive"))
      (node (ref "SV11") (pin "34") (pinfunction "34_34") (pintype "passive"))
      (node (ref "SV12") (pin "33") (pinfunction "33_33") (pintype "passive"))
    )
    (net (code "181") (name "Net-(SV11-Pad35)") (class "Default")
      (node (ref "SV11") (pin "35") (pinfunction "35_35") (pintype "passive"))
      (node (ref "SV11") (pin "36") (pinfunction "36_36") (pintype "passive"))
      (node (ref "SV12") (pin "35") (pinfunction "35_35") (pintype "passive"))
    )
    (net (code "182") (name "Net-(SV11-Pad37)") (class "Default")
      (node (ref "SV11") (pin "37") (pinfunction "37_37") (pintype "passive"))
      (node (ref "SV11") (pin "38") (pinfunction "38_38") (pintype "passive"))
      (node (ref "SV12") (pin "37") (pinfunction "37_37") (pintype "passive"))
    )
    (net (code "183") (name "Net-(SV11-Pad39)") (class "Default")
      (node (ref "SV11") (pin "39") (pinfunction "39_39") (pintype "passive"))
      (node (ref "SV11") (pin "40") (pinfunction "40_40") (pintype "passive"))
      (node (ref "SV12") (pin "39") (pinfunction "39_39") (pintype "passive"))
    )
    (net (code "184") (name "Net-(SV13-Pad1)") (class "Default")
      (node (ref "SV13") (pin "1") (pinfunction "1_1") (pintype "passive"))
      (node (ref "SV13") (pin "2") (pinfunction "2_2") (pintype "passive"))
      (node (ref "SV14") (pin "2") (pinfunction "2_2") (pintype "passive"))
    )
    (net (code "185") (name "Net-(SV13-Pad3)") (class "Default")
      (node (ref "SV13") (pin "3") (pinfunction "3_3") (pintype "passive"))
      (node (ref "SV13") (pin "4") (pinfunction "4_4") (pintype "passive"))
      (node (ref "SV14") (pin "4") (pinfunction "4_4") (pintype "passive"))
    )
    (net (code "186") (name "Net-(SV13-Pad5)") (class "Default")
      (node (ref "SV13") (pin "5") (pinfunction "5_5") (pintype "passive"))
      (node (ref "SV13") (pin "6") (pinfunction "6_6") (pintype "passive"))
      (node (ref "SV14") (pin "6") (pinfunction "6_6") (pintype "passive"))
    )
    (net (code "187") (name "Net-(SV13-Pad7)") (class "Default")
      (node (ref "SV13") (pin "7") (pinfunction "7_7") (pintype "passive"))
      (node (ref "SV13") (pin "8") (pinfunction "8_8") (pintype "passive"))
      (node (ref "SV14") (pin "8") (pinfunction "8_8") (pintype "passive"))
    )
    (net (code "188") (name "Net-(SV13-Pad10)") (class "Default")
      (node (ref "SV13") (pin "10") (pinfunction "10_10") (pintype "passive"))
      (node (ref "SV13") (pin "9") (pinfunction "9_9") (pintype "passive"))
      (node (ref "SV14") (pin "10") (pinfunction "10_10") (pintype "passive"))
    )
    (net (code "189") (name "Net-(SV13-Pad11)") (class "Default")
      (node (ref "SV13") (pin "11") (pinfunction "11_11") (pintype "passive"))
      (node (ref "SV13") (pin "12") (pinfunction "12_12") (pintype "passive"))
      (node (ref "SV14") (pin "12") (pinfunction "12_12") (pintype "passive"))
    )
    (net (code "190") (name "Net-(SV13-Pad13)") (class "Default")
      (node (ref "SV13") (pin "13") (pinfunction "13_13") (pintype "passive"))
      (node (ref "SV13") (pin "14") (pinfunction "14_14") (pintype "passive"))
      (node (ref "SV14") (pin "14") (pinfunction "14_14") (pintype "passive"))
    )
    (net (code "191") (name "Net-(SV13-Pad15)") (class "Default")
      (node (ref "SV13") (pin "15") (pinfunction "15_15") (pintype "passive"))
      (node (ref "SV13") (pin "16") (pinfunction "16_16") (pintype "passive"))
      (node (ref "SV14") (pin "16") (pinfunction "16_16") (pintype "passive"))
    )
    (net (code "192") (name "Net-(SV13-Pad17)") (class "Default")
      (node (ref "SV13") (pin "17") (pinfunction "17_17") (pintype "passive"))
      (node (ref "SV13") (pin "18") (pinfunction "18_18") (pintype "passive"))
      (node (ref "SV14") (pin "18") (pinfunction "18_18") (pintype "passive"))
    )
    (net (code "193") (name "Net-(SV13-Pad19)") (class "Default")
      (node (ref "SV13") (pin "19") (pinfunction "19_19") (pintype "passive"))
      (node (ref "SV13") (pin "20") (pinfunction "20_20") (pintype "passive"))
      (node (ref "SV14") (pin "20") (pinfunction "20_20") (pintype "passive"))
    )
    (net (code "194") (name "Net-(SV13-Pad21)") (class "Default")
      (node (ref "SV13") (pin "21") (pinfunction "21_21") (pintype "passive"))
      (node (ref "SV13") (pin "22") (pinfunction "22_22") (pintype "passive"))
      (node (ref "SV14") (pin "22") (pinfunction "22_22") (pintype "passive"))
    )
    (net (code "195") (name "Net-(SV13-Pad23)") (class "Default")
      (node (ref "SV13") (pin "23") (pinfunction "23_23") (pintype "passive"))
      (node (ref "SV13") (pin "24") (pinfunction "24_24") (pintype "passive"))
      (node (ref "SV14") (pin "24") (pinfunction "24_24") (pintype "passive"))
    )
    (net (code "196") (name "Net-(SV13-Pad25)") (class "Default")
      (node (ref "SV13") (pin "25") (pinfunction "25_25") (pintype "passive"))
      (node (ref "SV13") (pin "26") (pinfunction "26_26") (pintype "passive"))
      (node (ref "SV14") (pin "26") (pinfunction "26_26") (pintype "passive"))
    )
    (net (code "197") (name "Net-(SV13-Pad27)") (class "Default")
      (node (ref "SV13") (pin "27") (pinfunction "27_27") (pintype "passive"))
      (node (ref "SV13") (pin "28") (pinfunction "28_28") (pintype "passive"))
      (node (ref "SV14") (pin "28") (pinfunction "28_28") (pintype "passive"))
    )
    (net (code "198") (name "Net-(SV13-Pad29)") (class "Default")
      (node (ref "SV13") (pin "29") (pinfunction "29_29") (pintype "passive"))
      (node (ref "SV13") (pin "30") (pinfunction "30_30") (pintype "passive"))
      (node (ref "SV14") (pin "30") (pinfunction "30_30") (pintype "passive"))
    )
    (net (code "199") (name "Net-(SV13-Pad31)") (class "Default")
      (node (ref "SV13") (pin "31") (pinfunction "31_31") (pintype "passive"))
      (node (ref "SV13") (pin "32") (pinfunction "32_32") (pintype "passive"))
      (node (ref "SV14") (pin "32") (pinfunction "32_32") (pintype "passive"))
    )
    (net (code "200") (name "Net-(SV13-Pad33)") (class "Default")
      (node (ref "SV13") (pin "33") (pinfunction "33_33") (pintype "passive"))
      (node (ref "SV13") (pin "34") (pinfunction "34_34") (pintype "passive"))
      (node (ref "SV14") (pin "34") (pinfunction "34_34") (pintype "passive"))
    )
    (net (code "201") (name "Net-(SV13-Pad35)") (class "Default")
      (node (ref "SV13") (pin "35") (pinfunction "35_35") (pintype "passive"))
      (node (ref "SV13") (pin "36") (pinfunction "36_36") (pintype "passive"))
      (node (ref "SV14") (pin "36") (pinfunction "36_36") (pintype "passive"))
    )
    (net (code "202") (name "Net-(SV13-Pad37)") (class "Default")
      (node (ref "SV13") (pin "37") (pinfunction "37_37") (pintype "passive"))
      (node (ref "SV13") (pin "38") (pinfunction "38_38") (pintype "passive"))
      (node (ref "SV14") (pin "38") (pinfunction "38_38") (pintype "passive"))
    )
    (net (code "203") (name "Net-(SV13-Pad39)") (class "Default")
      (node (ref "SV13") (pin "39") (pinfunction "39_39") (pintype "passive"))
      (node (ref "SV13") (pin "40") (pinfunction "40_40") (pintype "passive"))
      (node (ref "SV14") (pin "40") (pinfunction "40_40") (pintype "passive"))
    )
    (net (code "204") (name "Net-(SV15-Pad1)") (class "Default")
      (node (ref "SV15") (pin "1") (pinfunction "1_1") (pintype "passive"))
      (node (ref "SV15") (pin "2") (pinfunction "2_2") (pintype "passive"))
      (node (ref "SV16") (pin "2") (pinfunction "2_2") (pintype "passive"))
    )
    (net (code "205") (name "Net-(SV15-Pad3)") (class "Default")
      (node (ref "SV15") (pin "3") (pinfunction "3_3") (pintype "passive"))
      (node (ref "SV15") (pin "4") (pinfunction "4_4") (pintype "passive"))
      (node (ref "SV16") (pin "4") (pinfunction "4_4") (pintype "passive"))
    )
    (net (code "206") (name "Net-(SV15-Pad5)") (class "Default")
      (node (ref "SV15") (pin "5") (pinfunction "5_5") (pintype "passive"))
      (node (ref "SV15") (pin "6") (pinfunction "6_6") (pintype "passive"))
      (node (ref "SV16") (pin "6") (pinfunction "6_6") (pintype "passive"))
    )
    (net (code "207") (name "Net-(SV15-Pad7)") (class "Default")
      (node (ref "SV15") (pin "7") (pinfunction "7_7") (pintype "passive"))
      (node (ref "SV15") (pin "8") (pinfunction "8_8") (pintype "passive"))
      (node (ref "SV16") (pin "8") (pinfunction "8_8") (pintype "passive"))
    )
    (net (code "208") (name "Net-(SV15-Pad10)") (class "Default")
      (node (ref "SV15") (pin "10") (pinfunction "10_10") (pintype "passive"))
      (node (ref "SV15") (pin "9") (pinfunction "9_9") (pintype "passive"))
      (node (ref "SV16") (pin "10") (pinfunction "10_10") (pintype "passive"))
    )
    (net (code "209") (name "Net-(SV15-Pad11)") (class "Default")
      (node (ref "SV15") (pin "11") (pinfunction "11_11") (pintype "passive"))
      (node (ref "SV15") (pin "12") (pinfunction "12_12") (pintype "passive"))
      (node (ref "SV16") (pin "12") (pinfunction "12_12") (pintype "passive"))
    )
    (net (code "210") (name "Net-(SV15-Pad13)") (class "Default")
      (node (ref "SV15") (pin "13") (pinfunction "13_13") (pintype "passive"))
      (node (ref "SV15") (pin "14") (pinfunction "14_14") (pintype "passive"))
      (node (ref "SV16") (pin "14") (pinfunction "14_14") (pintype "passive"))
    )
    (net (code "211") (name "Net-(SV15-Pad15)") (class "Default")
      (node (ref "SV15") (pin "15") (pinfunction "15_15") (pintype "passive"))
      (node (ref "SV15") (pin "16") (pinfunction "16_16") (pintype "passive"))
      (node (ref "SV16") (pin "16") (pinfunction "16_16") (pintype "passive"))
    )
    (net (code "212") (name "Net-(SV15-Pad17)") (class "Default")
      (node (ref "SV15") (pin "17") (pinfunction "17_17") (pintype "passive"))
      (node (ref "SV15") (pin "18") (pinfunction "18_18") (pintype "passive"))
      (node (ref "SV16") (pin "18") (pinfunction "18_18") (pintype "passive"))
    )
    (net (code "213") (name "Net-(SV15-Pad19)") (class "Default")
      (node (ref "SV15") (pin "19") (pinfunction "19_19") (pintype "passive"))
      (node (ref "SV15") (pin "20") (pinfunction "20_20") (pintype "passive"))
      (node (ref "SV16") (pin "20") (pinfunction "20_20") (pintype "passive"))
    )
    (net (code "214") (name "Net-(SV15-Pad21)") (class "Default")
      (node (ref "SV15") (pin "21") (pinfunction "21_21") (pintype "passive"))
      (node (ref "SV15") (pin "22") (pinfunction "22_22") (pintype "passive"))
      (node (ref "SV16") (pin "22") (pinfunction "22_22") (pintype "passive"))
    )
    (net (code "215") (name "Net-(SV15-Pad23)") (class "Default")
      (node (ref "SV15") (pin "23") (pinfunction "23_23") (pintype "passive"))
      (node (ref "SV15") (pin "24") (pinfunction "24_24") (pintype "passive"))
      (node (ref "SV16") (pin "24") (pinfunction "24_24") (pintype "passive"))
    )
    (net (code "216") (name "Net-(SV15-Pad25)") (class "Default")
      (node (ref "SV15") (pin "25") (pinfunction "25_25") (pintype "passive"))
      (node (ref "SV15") (pin "26") (pinfunction "26_26") (pintype "passive"))
      (node (ref "SV16") (pin "26") (pinfunction "26_26") (pintype "passive"))
    )
    (net (code "217") (name "Net-(SV15-Pad27)") (class "Default")
      (node (ref "SV15") (pin "27") (pinfunction "27_27") (pintype "passive"))
      (node (ref "SV15") (pin "28") (pinfunction "28_28") (pintype "passive"))
      (node (ref "SV16") (pin "28") (pinfunction "28_28") (pintype "passive"))
    )
    (net (code "218") (name "Net-(SV15-Pad29)") (class "Default")
      (node (ref "SV15") (pin "29") (pinfunction "29_29") (pintype "passive"))
      (node (ref "SV15") (pin "30") (pinfunction "30_30") (pintype "passive"))
      (node (ref "SV16") (pin "30") (pinfunction "30_30") (pintype "passive"))
    )
    (net (code "219") (name "Net-(SV15-Pad31)") (class "Default")
      (node (ref "SV15") (pin "31") (pinfunction "31_31") (pintype "passive"))
      (node (ref "SV15") (pin "32") (pinfunction "32_32") (pintype "passive"))
      (node (ref "SV16") (pin "32") (pinfunction "32_32") (pintype "passive"))
    )
    (net (code "220") (name "Net-(SV15-Pad33)") (class "Default")
      (node (ref "SV15") (pin "33") (pinfunction "33_33") (pintype "passive"))
      (node (ref "SV15") (pin "34") (pinfunction "34_34") (pintype "passive"))
      (node (ref "SV16") (pin "34") (pinfunction "34_34") (pintype "passive"))
    )
    (net (code "221") (name "Net-(SV15-Pad35)") (class "Default")
      (node (ref "SV15") (pin "35") (pinfunction "35_35") (pintype "passive"))
      (node (ref "SV15") (pin "36") (pinfunction "36_36") (pintype "passive"))
      (node (ref "SV16") (pin "36") (pinfunction "36_36") (pintype "passive"))
    )
    (net (code "222") (name "Net-(SV17-Pad1)") (class "Default")
      (node (ref "SV17") (pin "1") (pinfunction "1_1") (pintype "passive"))
      (node (ref "SV17") (pin "2") (pinfunction "2_2") (pintype "passive"))
      (node (ref "SV18") (pin "1") (pinfunction "1_1") (pintype "passive"))
    )
    (net (code "223") (name "Net-(SV17-Pad3)") (class "Default")
      (node (ref "SV17") (pin "3") (pinfunction "3_3") (pintype "passive"))
      (node (ref "SV17") (pin "4") (pinfunction "4_4") (pintype "passive"))
      (node (ref "SV18") (pin "3") (pinfunction "3_3") (pintype "passive"))
    )
    (net (code "224") (name "Net-(SV17-Pad5)") (class "Default")
      (node (ref "SV17") (pin "5") (pinfunction "5_5") (pintype "passive"))
      (node (ref "SV17") (pin "6") (pinfunction "6_6") (pintype "passive"))
      (node (ref "SV18") (pin "5") (pinfunction "5_5") (pintype "passive"))
    )
    (net (code "225") (name "Net-(SV17-Pad7)") (class "Default")
      (node (ref "SV17") (pin "7") (pinfunction "7_7") (pintype "passive"))
      (node (ref "SV17") (pin "8") (pinfunction "8_8") (pintype "passive"))
      (node (ref "SV18") (pin "7") (pinfunction "7_7") (pintype "passive"))
    )
    (net (code "226") (name "Net-(SV17-Pad10)") (class "Default")
      (node (ref "SV17") (pin "10") (pinfunction "10_10") (pintype "passive"))
      (node (ref "SV17") (pin "9") (pinfunction "9_9") (pintype "passive"))
      (node (ref "SV18") (pin "9") (pinfunction "9_9") (pintype "passive"))
    )
    (net (code "227") (name "Net-(SV17-Pad11)") (class "Default")
      (node (ref "SV17") (pin "11") (pinfunction "11_11") (pintype "passive"))
      (node (ref "SV17") (pin "12") (pinfunction "12_12") (pintype "passive"))
      (node (ref "SV18") (pin "11") (pinfunction "11_11") (pintype "passive"))
    )
    (net (code "228") (name "Net-(SV17-Pad13)") (class "Default")
      (node (ref "SV17") (pin "13") (pinfunction "13_13") (pintype "passive"))
      (node (ref "SV17") (pin "14") (pinfunction "14_14") (pintype "passive"))
      (node (ref "SV18") (pin "13") (pinfunction "13_13") (pintype "passive"))
    )
    (net (code "229") (name "Net-(SV17-Pad15)") (class "Default")
      (node (ref "SV17") (pin "15") (pinfunction "15_15") (pintype "passive"))
      (node (ref "SV17") (pin "16") (pinfunction "16_16") (pintype "passive"))
      (node (ref "SV18") (pin "15") (pinfunction "15_15") (pintype "passive"))
    )
    (net (code "230") (name "Net-(SV17-Pad17)") (class "Default")
      (node (ref "SV17") (pin "17") (pinfunction "17_17") (pintype "passive"))
      (node (ref "SV17") (pin "18") (pinfunction "18_18") (pintype "passive"))
      (node (ref "SV18") (pin "17") (pinfunction "17_17") (pintype "passive"))
    )
    (net (code "231") (name "Net-(SV17-Pad19)") (class "Default")
      (node (ref "SV17") (pin "19") (pinfunction "19_19") (pintype "passive"))
      (node (ref "SV17") (pin "20") (pinfunction "20_20") (pintype "passive"))
      (node (ref "SV18") (pin "19") (pinfunction "19_19") (pintype "passive"))
    )
    (net (code "232") (name "Net-(SV17-Pad21)") (class "Default")
      (node (ref "SV17") (pin "21") (pinfunction "21_21") (pintype "passive"))
      (node (ref "SV17") (pin "22") (pinfunction "22_22") (pintype "passive"))
      (node (ref "SV18") (pin "21") (pinfunction "21_21") (pintype "passive"))
    )
    (net (code "233") (name "Net-(SV17-Pad23)") (class "Default")
      (node (ref "SV17") (pin "23") (pinfunction "23_23") (pintype "passive"))
      (node (ref "SV17") (pin "24") (pinfunction "24_24") (pintype "passive"))
      (node (ref "SV18") (pin "23") (pinfunction "23_23") (pintype "passive"))
    )
    (net (code "234") (name "Net-(SV17-Pad25)") (class "Default")
      (node (ref "SV17") (pin "25") (pinfunction "25_25") (pintype "passive"))
      (node (ref "SV17") (pin "26") (pinfunction "26_26") (pintype "passive"))
      (node (ref "SV18") (pin "25") (pinfunction "25_25") (pintype "passive"))
    )
    (net (code "235") (name "Net-(SV17-Pad27)") (class "Default")
      (node (ref "SV17") (pin "27") (pinfunction "27_27") (pintype "passive"))
      (node (ref "SV17") (pin "28") (pinfunction "28_28") (pintype "passive"))
      (node (ref "SV18") (pin "27") (pinfunction "27_27") (pintype "passive"))
    )
    (net (code "236") (name "Net-(SV17-Pad29)") (class "Default")
      (node (ref "SV17") (pin "29") (pinfunction "29_29") (pintype "passive"))
      (node (ref "SV17") (pin "30") (pinfunction "30_30") (pintype "passive"))
      (node (ref "SV18") (pin "29") (pinfunction "29_29") (pintype "passive"))
    )
    (net (code "237") (name "Net-(SV17-Pad31)") (class "Default")
      (node (ref "SV17") (pin "31") (pinfunction "31_31") (pintype "passive"))
      (node (ref "SV17") (pin "32") (pinfunction "32_32") (pintype "passive"))
      (node (ref "SV18") (pin "31") (pinfunction "31_31") (pintype "passive"))
    )
    (net (code "238") (name "Net-(SV17-Pad33)") (class "Default")
      (node (ref "SV17") (pin "33") (pinfunction "33_33") (pintype "passive"))
      (node (ref "SV17") (pin "34") (pinfunction "34_34") (pintype "passive"))
      (node (ref "SV18") (pin "33") (pinfunction "33_33") (pintype "passive"))
    )
    (net (code "239") (name "Net-(SV17-Pad35)") (class "Default")
      (node (ref "SV17") (pin "35") (pinfunction "35_35") (pintype "passive"))
      (node (ref "SV17") (pin "36") (pinfunction "36_36") (pintype "passive"))
      (node (ref "SV18") (pin "35") (pinfunction "35_35") (pintype "passive"))
    )
    (net (code "240") (name "Net-(SV19-Pad1)") (class "Default")
      (node (ref "SV19") (pin "1") (pinfunction "1_1") (pintype "passive"))
      (node (ref "SV19") (pin "2") (pinfunction "2_2") (pintype "passive"))
      (node (ref "SV20") (pin "1") (pinfunction "1_1") (pintype "passive"))
    )
    (net (code "241") (name "Net-(SV19-Pad3)") (class "Default")
      (node (ref "SV19") (pin "3") (pinfunction "3_3") (pintype "passive"))
      (node (ref "SV19") (pin "4") (pinfunction "4_4") (pintype "passive"))
      (node (ref "SV20") (pin "3") (pinfunction "3_3") (pintype "passive"))
    )
    (net (code "242") (name "Net-(SV19-Pad5)") (class "Default")
      (node (ref "SV19") (pin "5") (pinfunction "5_5") (pintype "passive"))
      (node (ref "SV19") (pin "6") (pinfunction "6_6") (pintype "passive"))
      (node (ref "SV20") (pin "5") (pinfunction "5_5") (pintype "passive"))
    )
    (net (code "243") (name "Net-(SV19-Pad7)") (class "Default")
      (node (ref "SV19") (pin "7") (pinfunction "7_7") (pintype "passive"))
      (node (ref "SV19") (pin "8") (pinfunction "8_8") (pintype "passive"))
      (node (ref "SV20") (pin "7") (pinfunction "7_7") (pintype "passive"))
    )
    (net (code "244") (name "Net-(SV19-Pad10)") (class "Default")
      (node (ref "SV19") (pin "10") (pinfunction "10_10") (pintype "passive"))
      (node (ref "SV19") (pin "9") (pinfunction "9_9") (pintype "passive"))
      (node (ref "SV20") (pin "9") (pinfunction "9_9") (pintype "passive"))
    )
    (net (code "245") (name "Net-(SV19-Pad11)") (class "Default")
      (node (ref "SV19") (pin "11") (pinfunction "11_11") (pintype "passive"))
      (node (ref "SV19") (pin "12") (pinfunction "12_12") (pintype "passive"))
      (node (ref "SV20") (pin "11") (pinfunction "11_11") (pintype "passive"))
    )
    (net (code "246") (name "Net-(SV19-Pad13)") (class "Default")
      (node (ref "SV19") (pin "13") (pinfunction "13_13") (pintype "passive"))
      (node (ref "SV19") (pin "14") (pinfunction "14_14") (pintype "passive"))
      (node (ref "SV20") (pin "13") (pinfunction "13_13") (pintype "passive"))
    )
    (net (code "247") (name "Net-(SV19-Pad15)") (class "Default")
      (node (ref "SV19") (pin "15") (pinfunction "15_15") (pintype "passive"))
      (node (ref "SV19") (pin "16") (pinfunction "16_16") (pintype "passive"))
      (node (ref "SV20") (pin "15") (pinfunction "15_15") (pintype "passive"))
    )
    (net (code "248") (name "Net-(SV19-Pad17)") (class "Default")
      (node (ref "SV19") (pin "17") (pinfunction "17_17") (pintype "passive"))
      (node (ref "SV19") (pin "18") (pinfunction "18_18") (pintype "passive"))
      (node (ref "SV20") (pin "17") (pinfunction "17_17") (pintype "passive"))
    )
    (net (code "249") (name "Net-(SV19-Pad19)") (class "Default")
      (node (ref "SV19") (pin "19") (pinfunction "19_19") (pintype "passive"))
      (node (ref "SV19") (pin "20") (pinfunction "20_20") (pintype "passive"))
      (node (ref "SV20") (pin "19") (pinfunction "19_19") (pintype "passive"))
    )
    (net (code "250") (name "Net-(SV19-Pad21)") (class "Default")
      (node (ref "SV19") (pin "21") (pinfunction "21_21") (pintype "passive"))
      (node (ref "SV19") (pin "22") (pinfunction "22_22") (pintype "passive"))
      (node (ref "SV20") (pin "21") (pinfunction "21_21") (pintype "passive"))
    )
    (net (code "251") (name "Net-(SV19-Pad23)") (class "Default")
      (node (ref "SV19") (pin "23") (pinfunction "23_23") (pintype "passive"))
      (node (ref "SV19") (pin "24") (pinfunction "24_24") (pintype "passive"))
      (node (ref "SV20") (pin "23") (pinfunction "23_23") (pintype "passive"))
    )
    (net (code "252") (name "Net-(SV19-Pad25)") (class "Default")
      (node (ref "SV19") (pin "25") (pinfunction "25_25") (pintype "passive"))
      (node (ref "SV19") (pin "26") (pinfunction "26_26") (pintype "passive"))
      (node (ref "SV20") (pin "25") (pinfunction "25_25") (pintype "passive"))
    )
    (net (code "253") (name "Net-(SV19-Pad27)") (class "Default")
      (node (ref "SV19") (pin "27") (pinfunction "27_27") (pintype "passive"))
      (node (ref "SV19") (pin "28") (pinfunction "28_28") (pintype "passive"))
      (node (ref "SV20") (pin "27") (pinfunction "27_27") (pintype "passive"))
    )
    (net (code "254") (name "Net-(SV19-Pad29)") (class "Default")
      (node (ref "SV19") (pin "29") (pinfunction "29_29") (pintype "passive"))
      (node (ref "SV19") (pin "30") (pinfunction "30_30") (pintype "passive"))
      (node (ref "SV20") (pin "29") (pinfunction "29_29") (pintype "passive"))
    )
    (net (code "255") (name "Net-(SV19-Pad31)") (class "Default")
      (node (ref "SV19") (pin "31") (pinfunction "31_31") (pintype "passive"))
      (node (ref "SV19") (pin "32") (pinfunction "32_32") (pintype "passive"))
      (node (ref "SV20") (pin "31") (pinfunction "31_31") (pintype "passive"))
    )
    (net (code "256") (name "Net-(SV19-Pad33)") (class "Default")
      (node (ref "SV19") (pin "33") (pinfunction "33_33") (pintype "passive"))
      (node (ref "SV19") (pin "34") (pinfunction "34_34") (pintype "passive"))
      (node (ref "SV20") (pin "33") (pinfunction "33_33") (pintype "passive"))
    )
    (net (code "257") (name "Net-(SV19-Pad35)") (class "Default")
      (node (ref "SV19") (pin "35") (pinfunction "35_35") (pintype "passive"))
      (node (ref "SV19") (pin "36") (pinfunction "36_36") (pintype "passive"))
      (node (ref "SV20") (pin "35") (pinfunction "35_35") (pintype "passive"))
    )
    (net (code "258") (name "Net-(SV19-Pad37)") (class "Default")
      (node (ref "SV19") (pin "37") (pinfunction "37_37") (pintype "passive"))
      (node (ref "SV19") (pin "38") (pinfunction "38_38") (pintype "passive"))
      (node (ref "SV20") (pin "37") (pinfunction "37_37") (pintype "passive"))
    )
    (net (code "259") (name "Net-(SV19-Pad39)") (class "Default")
      (node (ref "SV19") (pin "39") (pinfunction "39_39") (pintype "passive"))
      (node (ref "SV19") (pin "40") (pinfunction "40_40") (pintype "passive"))
      (node (ref "SV20") (pin "39") (pinfunction "39_39") (pintype "passive"))
    )
    (net (code "260") (name "Net-(SV21-Pad1)") (class "Default")
      (node (ref "SV21") (pin "1") (pinfunction "1_1") (pintype "passive"))
      (node (ref "SV21") (pin "2") (pinfunction "2_2") (pintype "passive"))
      (node (ref "SV22") (pin "2") (pinfunction "2_2") (pintype "passive"))
    )
    (net (code "261") (name "Net-(SV21-Pad3)") (class "Default")
      (node (ref "SV21") (pin "3") (pinfunction "3_3") (pintype "passive"))
      (node (ref "SV21") (pin "4") (pinfunction "4_4") (pintype "passive"))
      (node (ref "SV22") (pin "4") (pinfunction "4_4") (pintype "passive"))
    )
    (net (code "262") (name "Net-(SV21-Pad5)") (class "Default")
      (node (ref "SV21") (pin "5") (pinfunction "5_5") (pintype "passive"))
      (node (ref "SV21") (pin "6") (pinfunction "6_6") (pintype "passive"))
      (node (ref "SV22") (pin "6") (pinfunction "6_6") (pintype "passive"))
    )
    (net (code "263") (name "Net-(SV21-Pad7)") (class "Default")
      (node (ref "SV21") (pin "7") (pinfunction "7_7") (pintype "passive"))
      (node (ref "SV21") (pin "8") (pinfunction "8_8") (pintype "passive"))
      (node (ref "SV22") (pin "8") (pinfunction "8_8") (pintype "passive"))
    )
    (net (code "264") (name "Net-(SV21-Pad10)") (class "Default")
      (node (ref "SV21") (pin "10") (pinfunction "10_10") (pintype "passive"))
      (node (ref "SV21") (pin "9") (pinfunction "9_9") (pintype "passive"))
      (node (ref "SV22") (pin "10") (pinfunction "10_10") (pintype "passive"))
    )
    (net (code "265") (name "Net-(SV21-Pad11)") (class "Default")
      (node (ref "SV21") (pin "11") (pinfunction "11_11") (pintype "passive"))
      (node (ref "SV21") (pin "12") (pinfunction "12_12") (pintype "passive"))
      (node (ref "SV22") (pin "12") (pinfunction "12_12") (pintype "passive"))
    )
    (net (code "266") (name "Net-(SV21-Pad13)") (class "Default")
      (node (ref "SV21") (pin "13") (pinfunction "13_13") (pintype "passive"))
      (node (ref "SV21") (pin "14") (pinfunction "14_14") (pintype "passive"))
      (node (ref "SV22") (pin "14") (pinfunction "14_14") (pintype "passive"))
    )
    (net (code "267") (name "Net-(SV21-Pad15)") (class "Default")
      (node (ref "SV21") (pin "15") (pinfunction "15_15") (pintype "passive"))
      (node (ref "SV21") (pin "16") (pinfunction "16_16") (pintype "passive"))
      (node (ref "SV22") (pin "16") (pinfunction "16_16") (pintype "passive"))
    )
    (net (code "268") (name "Net-(SV21-Pad17)") (class "Default")
      (node (ref "SV21") (pin "17") (pinfunction "17_17") (pintype "passive"))
      (node (ref "SV21") (pin "18") (pinfunction "18_18") (pintype "passive"))
      (node (ref "SV22") (pin "18") (pinfunction "18_18") (pintype "passive"))
    )
    (net (code "269") (name "Net-(SV21-Pad19)") (class "Default")
      (node (ref "SV21") (pin "19") (pinfunction "19_19") (pintype "passive"))
      (node (ref "SV21") (pin "20") (pinfunction "20_20") (pintype "passive"))
      (node (ref "SV22") (pin "20") (pinfunction "20_20") (pintype "passive"))
    )
    (net (code "270") (name "Net-(SV21-Pad21)") (class "Default")
      (node (ref "SV21") (pin "21") (pinfunction "21_21") (pintype "passive"))
      (node (ref "SV21") (pin "22") (pinfunction "22_22") (pintype "passive"))
      (node (ref "SV22") (pin "22") (pinfunction "22_22") (pintype "passive"))
    )
    (net (code "271") (name "Net-(SV21-Pad23)") (class "Default")
      (node (ref "SV21") (pin "23") (pinfunction "23_23") (pintype "passive"))
      (node (ref "SV21") (pin "24") (pinfunction "24_24") (pintype "passive"))
      (node (ref "SV22") (pin "24") (pinfunction "24_24") (pintype "passive"))
    )
    (net (code "272") (name "Net-(SV21-Pad25)") (class "Default")
      (node (ref "SV21") (pin "25") (pinfunction "25_25") (pintype "passive"))
      (node (ref "SV21") (pin "26") (pinfunction "26_26") (pintype "passive"))
      (node (ref "SV22") (pin "26") (pinfunction "26_26") (pintype "passive"))
    )
    (net (code "273") (name "Net-(SV21-Pad27)") (class "Default")
      (node (ref "SV21") (pin "27") (pinfunction "27_27") (pintype "passive"))
      (node (ref "SV21") (pin "28") (pinfunction "28_28") (pintype "passive"))
      (node (ref "SV22") (pin "28") (pinfunction "28_28") (pintype "passive"))
    )
    (net (code "274") (name "Net-(SV21-Pad29)") (class "Default")
      (node (ref "SV21") (pin "29") (pinfunction "29_29") (pintype "passive"))
      (node (ref "SV21") (pin "30") (pinfunction "30_30") (pintype "passive"))
      (node (ref "SV22") (pin "30") (pinfunction "30_30") (pintype "passive"))
    )
    (net (code "275") (name "Net-(SV21-Pad31)") (class "Default")
      (node (ref "SV21") (pin "31") (pinfunction "31_31") (pintype "passive"))
      (node (ref "SV21") (pin "32") (pinfunction "32_32") (pintype "passive"))
      (node (ref "SV22") (pin "32") (pinfunction "32_32") (pintype "passive"))
    )
    (net (code "276") (name "Net-(SV21-Pad33)") (class "Default")
      (node (ref "SV21") (pin "33") (pinfunction "33_33") (pintype "passive"))
      (node (ref "SV21") (pin "34") (pinfunction "34_34") (pintype "passive"))
      (node (ref "SV22") (pin "34") (pinfunction "34_34") (pintype "passive"))
    )
    (net (code "277") (name "Net-(SV21-Pad35)") (class "Default")
      (node (ref "SV21") (pin "35") (pinfunction "35_35") (pintype "passive"))
      (node (ref "SV21") (pin "36") (pinfunction "36_36") (pintype "passive"))
      (node (ref "SV22") (pin "36") (pinfunction "36_36") (pintype "passive"))
    )
    (net (code "278") (name "Net-(SV21-Pad37)") (class "Default")
      (node (ref "SV21") (pin "37") (pinfunction "37_37") (pintype "passive"))
      (node (ref "SV21") (pin "38") (pinfunction "38_38") (pintype "passive"))
      (node (ref "SV22") (pin "38") (pinfunction "38_38") (pintype "passive"))
    )
    (net (code "279") (name "Net-(SV21-Pad39)") (class "Default")
      (node (ref "SV21") (pin "39") (pinfunction "39_39") (pintype "passive"))
      (node (ref "SV21") (pin "40") (pinfunction "40_40") (pintype "passive"))
      (node (ref "SV22") (pin "40") (pinfunction "40_40") (pintype "passive"))
    )
    (net (code "280") (name "Net-(SV23-Pad1)") (class "Default")
      (node (ref "SV23") (pin "1") (pinfunction "1_1") (pintype "passive"))
      (node (ref "SV23") (pin "2") (pinfunction "2_2") (pintype "passive"))
      (node (ref "SV24") (pin "2") (pinfunction "2_2") (pintype "passive"))
    )
    (net (code "281") (name "Net-(SV23-Pad3)") (class "Default")
      (node (ref "SV23") (pin "3") (pinfunction "3_3") (pintype "passive"))
      (node (ref "SV23") (pin "4") (pinfunction "4_4") (pintype "passive"))
      (node (ref "SV24") (pin "4") (pinfunction "4_4") (pintype "passive"))
    )
    (net (code "282") (name "Net-(SV23-Pad5)") (class "Default")
      (node (ref "SV23") (pin "5") (pinfunction "5_5") (pintype "passive"))
      (node (ref "SV23") (pin "6") (pinfunction "6_6") (pintype "passive"))
      (node (ref "SV24") (pin "6") (pinfunction "6_6") (pintype "passive"))
    )
    (net (code "283") (name "Net-(SV23-Pad7)") (class "Default")
      (node (ref "SV23") (pin "7") (pinfunction "7_7") (pintype "passive"))
      (node (ref "SV23") (pin "8") (pinfunction "8_8") (pintype "passive"))
      (node (ref "SV24") (pin "8") (pinfunction "8_8") (pintype "passive"))
    )
    (net (code "284") (name "Net-(SV23-Pad10)") (class "Default")
      (node (ref "SV23") (pin "10") (pinfunction "10_10") (pintype "passive"))
      (node (ref "SV23") (pin "9") (pinfunction "9_9") (pintype "passive"))
      (node (ref "SV24") (pin "10") (pinfunction "10_10") (pintype "passive"))
    )
    (net (code "285") (name "Net-(SV23-Pad11)") (class "Default")
      (node (ref "SV23") (pin "11") (pinfunction "11_11") (pintype "passive"))
      (node (ref "SV23") (pin "12") (pinfunction "12_12") (pintype "passive"))
      (node (ref "SV24") (pin "12") (pinfunction "12_12") (pintype "passive"))
    )
    (net (code "286") (name "Net-(SV23-Pad13)") (class "Default")
      (node (ref "SV23") (pin "13") (pinfunction "13_13") (pintype "passive"))
      (node (ref "SV23") (pin "14") (pinfunction "14_14") (pintype "passive"))
      (node (ref "SV24") (pin "14") (pinfunction "14_14") (pintype "passive"))
    )
    (net (code "287") (name "Net-(SV23-Pad15)") (class "Default")
      (node (ref "SV23") (pin "15") (pinfunction "15_15") (pintype "passive"))
      (node (ref "SV23") (pin "16") (pinfunction "16_16") (pintype "passive"))
      (node (ref "SV24") (pin "16") (pinfunction "16_16") (pintype "passive"))
    )
    (net (code "288") (name "Net-(SV23-Pad17)") (class "Default")
      (node (ref "SV23") (pin "17") (pinfunction "17_17") (pintype "passive"))
      (node (ref "SV23") (pin "18") (pinfunction "18_18") (pintype "passive"))
      (node (ref "SV24") (pin "18") (pinfunction "18_18") (pintype "passive"))
    )
    (net (code "289") (name "Net-(SV23-Pad19)") (class "Default")
      (node (ref "SV23") (pin "19") (pinfunction "19_19") (pintype "passive"))
      (node (ref "SV23") (pin "20") (pinfunction "20_20") (pintype "passive"))
      (node (ref "SV24") (pin "20") (pinfunction "20_20") (pintype "passive"))
    )
    (net (code "290") (name "Net-(SV23-Pad21)") (class "Default")
      (node (ref "SV23") (pin "21") (pinfunction "21_21") (pintype "passive"))
      (node (ref "SV23") (pin "22") (pinfunction "22_22") (pintype "passive"))
      (node (ref "SV24") (pin "22") (pinfunction "22_22") (pintype "passive"))
    )
    (net (code "291") (name "Net-(SV23-Pad23)") (class "Default")
      (node (ref "SV23") (pin "23") (pinfunction "23_23") (pintype "passive"))
      (node (ref "SV23") (pin "24") (pinfunction "24_24") (pintype "passive"))
      (node (ref "SV24") (pin "24") (pinfunction "24_24") (pintype "passive"))
    )
    (net (code "292") (name "Net-(SV23-Pad25)") (class "Default")
      (node (ref "SV23") (pin "25") (pinfunction "25_25") (pintype "passive"))
      (node (ref "SV23") (pin "26") (pinfunction "26_26") (pintype "passive"))
      (node (ref "SV24") (pin "26") (pinfunction "26_26") (pintype "passive"))
    )
    (net (code "293") (name "Net-(SV23-Pad27)") (class "Default")
      (node (ref "SV23") (pin "27") (pinfunction "27_27") (pintype "passive"))
      (node (ref "SV23") (pin "28") (pinfunction "28_28") (pintype "passive"))
      (node (ref "SV24") (pin "28") (pinfunction "28_28") (pintype "passive"))
    )
    (net (code "294") (name "Net-(SV23-Pad29)") (class "Default")
      (node (ref "SV23") (pin "29") (pinfunction "29_29") (pintype "passive"))
      (node (ref "SV23") (pin "30") (pinfunction "30_30") (pintype "passive"))
      (node (ref "SV24") (pin "30") (pinfunction "30_30") (pintype "passive"))
    )
    (net (code "295") (name "Net-(SV23-Pad31)") (class "Default")
      (node (ref "SV23") (pin "31") (pinfunction "31_31") (pintype "passive"))
      (node (ref "SV23") (pin "32") (pinfunction "32_32") (pintype "passive"))
      (node (ref "SV24") (pin "32") (pinfunction "32_32") (pintype "passive"))
    )
    (net (code "296") (name "Net-(SV23-Pad33)") (class "Default")
      (node (ref "SV23") (pin "33") (pinfunction "33_33") (pintype "passive"))
      (node (ref "SV23") (pin "34") (pinfunction "34_34") (pintype "passive"))
      (node (ref "SV24") (pin "34") (pinfunction "34_34") (pintype "passive"))
    )
    (net (code "297") (name "Net-(SV23-Pad35)") (class "Default")
      (node (ref "SV23") (pin "35") (pinfunction "35_35") (pintype "passive"))
      (node (ref "SV23") (pin "36") (pinfunction "36_36") (pintype "passive"))
      (node (ref "SV24") (pin "36") (pinfunction "36_36") (pintype "passive"))
    )
    (net (code "298") (name "Net-(SV25-Pad1)") (class "Default")
      (node (ref "SV25") (pin "1") (pinfunction "1_1") (pintype "passive"))
      (node (ref "SV25") (pin "2") (pinfunction "2_2") (pintype "passive"))
      (node (ref "SV26") (pin "1") (pinfunction "1_1") (pintype "passive"))
    )
    (net (code "299") (name "Net-(SV25-Pad3)") (class "Default")
      (node (ref "SV25") (pin "3") (pinfunction "3_3") (pintype "passive"))
      (node (ref "SV25") (pin "4") (pinfunction "4_4") (pintype "passive"))
      (node (ref "SV26") (pin "3") (pinfunction "3_3") (pintype "passive"))
    )
    (net (code "300") (name "Net-(SV25-Pad5)") (class "Default")
      (node (ref "SV25") (pin "5") (pinfunction "5_5") (pintype "passive"))
      (node (ref "SV25") (pin "6") (pinfunction "6_6") (pintype "passive"))
      (node (ref "SV26") (pin "5") (pinfunction "5_5") (pintype "passive"))
    )
    (net (code "301") (name "Net-(SV25-Pad7)") (class "Default")
      (node (ref "SV25") (pin "7") (pinfunction "7_7") (pintype "passive"))
      (node (ref "SV25") (pin "8") (pinfunction "8_8") (pintype "passive"))
      (node (ref "SV26") (pin "7") (pinfunction "7_7") (pintype "passive"))
    )
    (net (code "302") (name "Net-(SV25-Pad10)") (class "Default")
      (node (ref "SV25") (pin "10") (pinfunction "10_10") (pintype "passive"))
      (node (ref "SV25") (pin "9") (pinfunction "9_9") (pintype "passive"))
      (node (ref "SV26") (pin "9") (pinfunction "9_9") (pintype "passive"))
    )
    (net (code "303") (name "Net-(SV25-Pad11)") (class "Default")
      (node (ref "SV25") (pin "11") (pinfunction "11_11") (pintype "passive"))
      (node (ref "SV25") (pin "12") (pinfunction "12_12") (pintype "passive"))
      (node (ref "SV26") (pin "11") (pinfunction "11_11") (pintype "passive"))
    )
    (net (code "304") (name "Net-(SV25-Pad13)") (class "Default")
      (node (ref "SV25") (pin "13") (pinfunction "13_13") (pintype "passive"))
      (node (ref "SV25") (pin "14") (pinfunction "14_14") (pintype "passive"))
      (node (ref "SV26") (pin "13") (pinfunction "13_13") (pintype "passive"))
    )
    (net (code "305") (name "Net-(SV25-Pad15)") (class "Default")
      (node (ref "SV25") (pin "15") (pinfunction "15_15") (pintype "passive"))
      (node (ref "SV25") (pin "16") (pinfunction "16_16") (pintype "passive"))
      (node (ref "SV26") (pin "15") (pinfunction "15_15") (pintype "passive"))
    )
    (net (code "306") (name "Net-(SV25-Pad17)") (class "Default")
      (node (ref "SV25") (pin "17") (pinfunction "17_17") (pintype "passive"))
      (node (ref "SV25") (pin "18") (pinfunction "18_18") (pintype "passive"))
      (node (ref "SV26") (pin "17") (pinfunction "17_17") (pintype "passive"))
    )
    (net (code "307") (name "Net-(SV25-Pad19)") (class "Default")
      (node (ref "SV25") (pin "19") (pinfunction "19_19") (pintype "passive"))
      (node (ref "SV25") (pin "20") (pinfunction "20_20") (pintype "passive"))
      (node (ref "SV26") (pin "19") (pinfunction "19_19") (pintype "passive"))
    )
    (net (code "308") (name "Net-(SV25-Pad21)") (class "Default")
      (node (ref "SV25") (pin "21") (pinfunction "21_21") (pintype "passive"))
      (node (ref "SV25") (pin "22") (pinfunction "22_22") (pintype "passive"))
      (node (ref "SV26") (pin "21") (pinfunction "21_21") (pintype "passive"))
    )
    (net (code "309") (name "Net-(SV25-Pad23)") (class "Default")
      (node (ref "SV25") (pin "23") (pinfunction "23_23") (pintype "passive"))
      (node (ref "SV25") (pin "24") (pinfunction "24_24") (pintype "passive"))
      (node (ref "SV26") (pin "23") (pinfunction "23_23") (pintype "passive"))
    )
    (net (code "310") (name "Net-(SV25-Pad25)") (class "Default")
      (node (ref "SV25") (pin "25") (pinfunction "25_25") (pintype "passive"))
      (node (ref "SV25") (pin "26") (pinfunction "26_26") (pintype "passive"))
      (node (ref "SV26") (pin "25") (pinfunction "25_25") (pintype "passive"))
    )
    (net (code "311") (name "Net-(SV25-Pad27)") (class "Default")
      (node (ref "SV25") (pin "27") (pinfunction "27_27") (pintype "passive"))
      (node (ref "SV25") (pin "28") (pinfunction "28_28") (pintype "passive"))
      (node (ref "SV26") (pin "27") (pinfunction "27_27") (pintype "passive"))
    )
    (net (code "312") (name "Net-(SV25-Pad29)") (class "Default")
      (node (ref "SV25") (pin "29") (pinfunction "29_29") (pintype "passive"))
      (node (ref "SV25") (pin "30") (pinfunction "30_30") (pintype "passive"))
      (node (ref "SV26") (pin "29") (pinfunction "29_29") (pintype "passive"))
    )
    (net (code "313") (name "Net-(SV25-Pad31)") (class "Default")
      (node (ref "SV25") (pin "31") (pinfunction "31_31") (pintype "passive"))
      (node (ref "SV25") (pin "32") (pinfunction "32_32") (pintype "passive"))
      (node (ref "SV26") (pin "31") (pinfunction "31_31") (pintype "passive"))
    )
    (net (code "314") (name "Net-(SV25-Pad33)") (class "Default")
      (node (ref "SV25") (pin "33") (pinfunction "33_33") (pintype "passive"))
      (node (ref "SV25") (pin "34") (pinfunction "34_34") (pintype "passive"))
      (node (ref "SV26") (pin "33") (pinfunction "33_33") (pintype "passive"))
    )
    (net (code "315") (name "Net-(SV25-Pad35)") (class "Default")
      (node (ref "SV25") (pin "35") (pinfunction "35_35") (pintype "passive"))
      (node (ref "SV25") (pin "36") (pinfunction "36_36") (pintype "passive"))
      (node (ref "SV26") (pin "35") (pinfunction "35_35") (pintype "passive"))
    )
    (net (code "316") (name "Net-(SV27-Pad1)") (class "Default")
      (node (ref "SV27") (pin "1") (pinfunction "1_1") (pintype "passive"))
      (node (ref "SV27") (pin "2") (pinfunction "2_2") (pintype "passive"))
      (node (ref "SV28") (pin "1") (pinfunction "1_1") (pintype "passive"))
    )
    (net (code "317") (name "Net-(SV27-Pad3)") (class "Default")
      (node (ref "SV27") (pin "3") (pinfunction "3_3") (pintype "passive"))
      (node (ref "SV27") (pin "4") (pinfunction "4_4") (pintype "passive"))
      (node (ref "SV28") (pin "3") (pinfunction "3_3") (pintype "passive"))
    )
    (net (code "318") (name "Net-(SV27-Pad5)") (class "Default")
      (node (ref "SV27") (pin "5") (pinfunction "5_5") (pintype "passive"))
      (node (ref "SV27") (pin "6") (pinfunction "6_6") (pintype "passive"))
      (node (ref "SV28") (pin "5") (pinfunction "5_5") (pintype "passive"))
    )
    (net (code "319") (name "Net-(SV27-Pad7)") (class "Default")
      (node (ref "SV27") (pin "7") (pinfunction "7_7") (pintype "passive"))
      (node (ref "SV27") (pin "8") (pinfunction "8_8") (pintype "passive"))
      (node (ref "SV28") (pin "7") (pinfunction "7_7") (pintype "passive"))
    )
    (net (code "320") (name "Net-(SV27-Pad10)") (class "Default")
      (node (ref "SV27") (pin "10") (pinfunction "10_10") (pintype "passive"))
      (node (ref "SV27") (pin "9") (pinfunction "9_9") (pintype "passive"))
      (node (ref "SV28") (pin "9") (pinfunction "9_9") (pintype "passive"))
    )
    (net (code "321") (name "Net-(SV27-Pad11)") (class "Default")
      (node (ref "SV27") (pin "11") (pinfunction "11_11") (pintype "passive"))
      (node (ref "SV27") (pin "12") (pinfunction "12_12") (pintype "passive"))
      (node (ref "SV28") (pin "11") (pinfunction "11_11") (pintype "passive"))
    )
    (net (code "322") (name "Net-(SV27-Pad13)") (class "Default")
      (node (ref "SV27") (pin "13") (pinfunction "13_13") (pintype "passive"))
      (node (ref "SV27") (pin "14") (pinfunction "14_14") (pintype "passive"))
      (node (ref "SV28") (pin "13") (pinfunction "13_13") (pintype "passive"))
    )
    (net (code "323") (name "Net-(SV27-Pad15)") (class "Default")
      (node (ref "SV27") (pin "15") (pinfunction "15_15") (pintype "passive"))
      (node (ref "SV27") (pin "16") (pinfunction "16_16") (pintype "passive"))
      (node (ref "SV28") (pin "15") (pinfunction "15_15") (pintype "passive"))
    )
    (net (code "324") (name "Net-(SV27-Pad17)") (class "Default")
      (node (ref "SV27") (pin "17") (pinfunction "17_17") (pintype "passive"))
      (node (ref "SV27") (pin "18") (pinfunction "18_18") (pintype "passive"))
      (node (ref "SV28") (pin "17") (pinfunction "17_17") (pintype "passive"))
    )
    (net (code "325") (name "Net-(SV27-Pad19)") (class "Default")
      (node (ref "SV27") (pin "19") (pinfunction "19_19") (pintype "passive"))
      (node (ref "SV27") (pin "20") (pinfunction "20_20") (pintype "passive"))
      (node (ref "SV28") (pin "19") (pinfunction "19_19") (pintype "passive"))
    )
    (net (code "326") (name "Net-(SV27-Pad21)") (class "Default")
      (node (ref "SV27") (pin "21") (pinfunction "21_21") (pintype "passive"))
      (node (ref "SV27") (pin "22") (pinfunction "22_22") (pintype "passive"))
      (node (ref "SV28") (pin "21") (pinfunction "21_21") (pintype "passive"))
    )
    (net (code "327") (name "Net-(SV27-Pad23)") (class "Default")
      (node (ref "SV27") (pin "23") (pinfunction "23_23") (pintype "passive"))
      (node (ref "SV27") (pin "24") (pinfunction "24_24") (pintype "passive"))
      (node (ref "SV28") (pin "23") (pinfunction "23_23") (pintype "passive"))
    )
    (net (code "328") (name "Net-(SV27-Pad25)") (class "Default")
      (node (ref "SV27") (pin "25") (pinfunction "25_25") (pintype "passive"))
      (node (ref "SV27") (pin "26") (pinfunction "26_26") (pintype "passive"))
      (node (ref "SV28") (pin "25") (pinfunction "25_25") (pintype "passive"))
    )
    (net (code "329") (name "Net-(SV27-Pad27)") (class "Default")
      (node (ref "SV27") (pin "27") (pinfunction "27_27") (pintype "passive"))
      (node (ref "SV27") (pin "28") (pinfunction "28_28") (pintype "passive"))
      (node (ref "SV28") (pin "27") (pinfunction "27_27") (pintype "passive"))
    )
    (net (code "330") (name "Net-(SV27-Pad29)") (class "Default")
      (node (ref "SV27") (pin "29") (pinfunction "29_29") (pintype "passive"))
      (node (ref "SV27") (pin "30") (pinfunction "30_30") (pintype "passive"))
      (node (ref "SV28") (pin "29") (pinfunction "29_29") (pintype "passive"))
    )
    (net (code "331") (name "Net-(SV27-Pad31)") (class "Default")
      (node (ref "SV27") (pin "31") (pinfunction "31_31") (pintype "passive"))
      (node (ref "SV27") (pin "32") (pinfunction "32_32") (pintype "passive"))
      (node (ref "SV28") (pin "31") (pinfunction "31_31") (pintype "passive"))
    )
    (net (code "332") (name "Net-(SV27-Pad33)") (class "Default")
      (node (ref "SV27") (pin "33") (pinfunction "33_33") (pintype "passive"))
      (node (ref "SV27") (pin "34") (pinfunction "34_34") (pintype "passive"))
      (node (ref "SV28") (pin "33") (pinfunction "33_33") (pintype "passive"))
    )
    (net (code "333") (name "Net-(SV27-Pad35)") (class "Default")
      (node (ref "SV27") (pin "35") (pinfunction "35_35") (pintype "passive"))
      (node (ref "SV27") (pin "36") (pinfunction "36_36") (pintype "passive"))
      (node (ref "SV28") (pin "35") (pinfunction "35_35") (pintype "passive"))
    )
    (net (code "334") (name "Net-(SV27-Pad37)") (class "Default")
      (node (ref "SV27") (pin "37") (pinfunction "37_37") (pintype "passive"))
      (node (ref "SV27") (pin "38") (pinfunction "38_38") (pintype "passive"))
      (node (ref "SV28") (pin "37") (pinfunction "37_37") (pintype "passive"))
    )
    (net (code "335") (name "Net-(SV27-Pad39)") (class "Default")
      (node (ref "SV27") (pin "39") (pinfunction "39_39") (pintype "passive"))
      (node (ref "SV27") (pin "40") (pinfunction "40_40") (pintype "passive"))
      (node (ref "SV28") (pin "39") (pinfunction "39_39") (pintype "passive"))
    )
    (net (code "336") (name "Net-(SV29-Pad1)") (class "Default")
      (node (ref "SV29") (pin "1") (pinfunction "1_1") (pintype "passive"))
      (node (ref "SV29") (pin "2") (pinfunction "2_2") (pintype "passive"))
      (node (ref "SV30") (pin "2") (pinfunction "2_2") (pintype "passive"))
    )
    (net (code "337") (name "Net-(SV29-Pad3)") (class "Default")
      (node (ref "SV29") (pin "3") (pinfunction "3_3") (pintype "passive"))
      (node (ref "SV29") (pin "4") (pinfunction "4_4") (pintype "passive"))
      (node (ref "SV30") (pin "4") (pinfunction "4_4") (pintype "passive"))
    )
    (net (code "338") (name "Net-(SV29-Pad5)") (class "Default")
      (node (ref "SV29") (pin "5") (pinfunction "5_5") (pintype "passive"))
      (node (ref "SV29") (pin "6") (pinfunction "6_6") (pintype "passive"))
      (node (ref "SV30") (pin "6") (pinfunction "6_6") (pintype "passive"))
    )
    (net (code "339") (name "Net-(SV29-Pad7)") (class "Default")
      (node (ref "SV29") (pin "7") (pinfunction "7_7") (pintype "passive"))
      (node (ref "SV29") (pin "8") (pinfunction "8_8") (pintype "passive"))
      (node (ref "SV30") (pin "8") (pinfunction "8_8") (pintype "passive"))
    )
    (net (code "340") (name "Net-(SV29-Pad10)") (class "Default")
      (node (ref "SV29") (pin "10") (pinfunction "10_10") (pintype "passive"))
      (node (ref "SV29") (pin "9") (pinfunction "9_9") (pintype "passive"))
      (node (ref "SV30") (pin "10") (pinfunction "10_10") (pintype "passive"))
    )
    (net (code "341") (name "Net-(SV29-Pad11)") (class "Default")
      (node (ref "SV29") (pin "11") (pinfunction "11_11") (pintype "passive"))
      (node (ref "SV29") (pin "12") (pinfunction "12_12") (pintype "passive"))
      (node (ref "SV30") (pin "12") (pinfunction "12_12") (pintype "passive"))
    )
    (net (code "342") (name "Net-(SV29-Pad13)") (class "Default")
      (node (ref "SV29") (pin "13") (pinfunction "13_13") (pintype "passive"))
      (node (ref "SV29") (pin "14") (pinfunction "14_14") (pintype "passive"))
      (node (ref "SV30") (pin "14") (pinfunction "14_14") (pintype "passive"))
    )
    (net (code "343") (name "Net-(SV29-Pad15)") (class "Default")
      (node (ref "SV29") (pin "15") (pinfunction "15_15") (pintype "passive"))
      (node (ref "SV29") (pin "16") (pinfunction "16_16") (pintype "passive"))
      (node (ref "SV30") (pin "16") (pinfunction "16_16") (pintype "passive"))
    )
    (net (code "344") (name "Net-(SV29-Pad17)") (class "Default")
      (node (ref "SV29") (pin "17") (pinfunction "17_17") (pintype "passive"))
      (node (ref "SV29") (pin "18") (pinfunction "18_18") (pintype "passive"))
      (node (ref "SV30") (pin "18") (pinfunction "18_18") (pintype "passive"))
    )
    (net (code "345") (name "Net-(SV29-Pad19)") (class "Default")
      (node (ref "SV29") (pin "19") (pinfunction "19_19") (pintype "passive"))
      (node (ref "SV29") (pin "20") (pinfunction "20_20") (pintype "passive"))
      (node (ref "SV30") (pin "20") (pinfunction "20_20") (pintype "passive"))
    )
    (net (code "346") (name "Net-(SV29-Pad21)") (class "Default")
      (node (ref "SV29") (pin "21") (pinfunction "21_21") (pintype "passive"))
      (node (ref "SV29") (pin "22") (pinfunction "22_22") (pintype "passive"))
      (node (ref "SV30") (pin "22") (pinfunction "22_22") (pintype "passive"))
    )
    (net (code "347") (name "Net-(SV29-Pad23)") (class "Default")
      (node (ref "SV29") (pin "23") (pinfunction "23_23") (pintype "passive"))
      (node (ref "SV29") (pin "24") (pinfunction "24_24") (pintype "passive"))
      (node (ref "SV30") (pin "24") (pinfunction "24_24") (pintype "passive"))
    )
    (net (code "348") (name "Net-(SV29-Pad25)") (class "Default")
      (node (ref "SV29") (pin "25") (pinfunction "25_25") (pintype "passive"))
      (node (ref "SV29") (pin "26") (pinfunction "26_26") (pintype "passive"))
      (node (ref "SV30") (pin "26") (pinfunction "26_26") (pintype "passive"))
    )
    (net (code "349") (name "Net-(SV29-Pad27)") (class "Default")
      (node (ref "SV29") (pin "27") (pinfunction "27_27") (pintype "passive"))
      (node (ref "SV29") (pin "28") (pinfunction "28_28") (pintype "passive"))
      (node (ref "SV30") (pin "28") (pinfunction "28_28") (pintype "passive"))
    )
    (net (code "350") (name "Net-(SV29-Pad29)") (class "Default")
      (node (ref "SV29") (pin "29") (pinfunction "29_29") (pintype "passive"))
      (node (ref "SV29") (pin "30") (pinfunction "30_30") (pintype "passive"))
      (node (ref "SV30") (pin "30") (pinfunction "30_30") (pintype "passive"))
    )
    (net (code "351") (name "Net-(SV29-Pad31)") (class "Default")
      (node (ref "SV29") (pin "31") (pinfunction "31_31") (pintype "passive"))
      (node (ref "SV29") (pin "32") (pinfunction "32_32") (pintype "passive"))
      (node (ref "SV30") (pin "32") (pinfunction "32_32") (pintype "passive"))
    )
    (net (code "352") (name "Net-(SV29-Pad33)") (class "Default")
      (node (ref "SV29") (pin "33") (pinfunction "33_33") (pintype "passive"))
      (node (ref "SV29") (pin "34") (pinfunction "34_34") (pintype "passive"))
      (node (ref "SV30") (pin "34") (pinfunction "34_34") (pintype "passive"))
    )
    (net (code "353") (name "Net-(SV29-Pad35)") (class "Default")
      (node (ref "SV29") (pin "35") (pinfunction "35_35") (pintype "passive"))
      (node (ref "SV29") (pin "36") (pinfunction "36_36") (pintype "passive"))
      (node (ref "SV30") (pin "36") (pinfunction "36_36") (pintype "passive"))
    )
    (net (code "354") (name "Net-(SV29-Pad37)") (class "Default")
      (node (ref "SV29") (pin "37") (pinfunction "37_37") (pintype "passive"))
      (node (ref "SV29") (pin "38") (pinfunction "38_38") (pintype "passive"))
      (node (ref "SV30") (pin "38") (pinfunction "38_38") (pintype "passive"))
    )
    (net (code "355") (name "Net-(SV29-Pad39)") (class "Default")
      (node (ref "SV29") (pin "39") (pinfunction "39_39") (pintype "passive"))
      (node (ref "SV29") (pin "40") (pinfunction "40_40") (pintype "passive"))
      (node (ref "SV30") (pin "40") (pinfunction "40_40") (pintype "passive"))
    )
    (net (code "356") (name "Net-(SV31-Pad1)") (class "Default")
      (node (ref "SV31") (pin "1") (pinfunction "1_1") (pintype "passive"))
      (node (ref "SV31") (pin "2") (pinfunction "2_2") (pintype "passive"))
      (node (ref "SV32") (pin "2") (pinfunction "2_2") (pintype "passive"))
    )
    (net (code "357") (name "Net-(SV31-Pad3)") (class "Default")
      (node (ref "SV31") (pin "3") (pinfunction "3_3") (pintype "passive"))
      (node (ref "SV31") (pin "4") (pinfunction "4_4") (pintype "passive"))
      (node (ref "SV32") (pin "4") (pinfunction "4_4") (pintype "passive"))
    )
    (net (code "358") (name "Net-(SV31-Pad5)") (class "Default")
      (node (ref "SV31") (pin "5") (pinfunction "5_5") (pintype "passive"))
      (node (ref "SV31") (pin "6") (pinfunction "6_6") (pintype "passive"))
      (node (ref "SV32") (pin "6") (pinfunction "6_6") (pintype "passive"))
    )
    (net (code "359") (name "Net-(SV31-Pad7)") (class "Default")
      (node (ref "SV31") (pin "7") (pinfunction "7_7") (pintype "passive"))
      (node (ref "SV31") (pin "8") (pinfunction "8_8") (pintype "passive"))
      (node (ref "SV32") (pin "8") (pinfunction "8_8") (pintype "passive"))
    )
    (net (code "360") (name "Net-(SV31-Pad10)") (class "Default")
      (node (ref "SV31") (pin "10") (pinfunction "10_10") (pintype "passive"))
      (node (ref "SV31") (pin "9") (pinfunction "9_9") (pintype "passive"))
      (node (ref "SV32") (pin "10") (pinfunction "10_10") (pintype "passive"))
    )
    (net (code "361") (name "Net-(SV31-Pad11)") (class "Default")
      (node (ref "SV31") (pin "11") (pinfunction "11_11") (pintype "passive"))
      (node (ref "SV31") (pin "12") (pinfunction "12_12") (pintype "passive"))
      (node (ref "SV32") (pin "12") (pinfunction "12_12") (pintype "passive"))
    )
    (net (code "362") (name "Net-(SV31-Pad13)") (class "Default")
      (node (ref "SV31") (pin "13") (pinfunction "13_13") (pintype "passive"))
      (node (ref "SV31") (pin "14") (pinfunction "14_14") (pintype "passive"))
      (node (ref "SV32") (pin "14") (pinfunction "14_14") (pintype "passive"))
    )
    (net (code "363") (name "Net-(SV31-Pad15)") (class "Default")
      (node (ref "SV31") (pin "15") (pinfunction "15_15") (pintype "passive"))
      (node (ref "SV31") (pin "16") (pinfunction "16_16") (pintype "passive"))
      (node (ref "SV32") (pin "16") (pinfunction "16_16") (pintype "passive"))
    )
    (net (code "364") (name "Net-(SV31-Pad17)") (class "Default")
      (node (ref "SV31") (pin "17") (pinfunction "17_17") (pintype "passive"))
      (node (ref "SV31") (pin "18") (pinfunction "18_18") (pintype "passive"))
      (node (ref "SV32") (pin "18") (pinfunction "18_18") (pintype "passive"))
    )
    (net (code "365") (name "Net-(SV31-Pad19)") (class "Default")
      (node (ref "SV31") (pin "19") (pinfunction "19_19") (pintype "passive"))
      (node (ref "SV31") (pin "20") (pinfunction "20_20") (pintype "passive"))
      (node (ref "SV32") (pin "20") (pinfunction "20_20") (pintype "passive"))
    )
    (net (code "366") (name "Net-(SV31-Pad21)") (class "Default")
      (node (ref "SV31") (pin "21") (pinfunction "21_21") (pintype "passive"))
      (node (ref "SV31") (pin "22") (pinfunction "22_22") (pintype "passive"))
      (node (ref "SV32") (pin "22") (pinfunction "22_22") (pintype "passive"))
    )
    (net (code "367") (name "Net-(SV31-Pad23)") (class "Default")
      (node (ref "SV31") (pin "23") (pinfunction "23_23") (pintype "passive"))
      (node (ref "SV31") (pin "24") (pinfunction "24_24") (pintype "passive"))
      (node (ref "SV32") (pin "24") (pinfunction "24_24") (pintype "passive"))
    )
    (net (code "368") (name "Net-(SV31-Pad25)") (class "Default")
      (node (ref "SV31") (pin "25") (pinfunction "25_25") (pintype "passive"))
      (node (ref "SV31") (pin "26") (pinfunction "26_26") (pintype "passive"))
      (node (ref "SV32") (pin "26") (pinfunction "26_26") (pintype "passive"))
    )
    (net (code "369") (name "Net-(SV31-Pad27)") (class "Default")
      (node (ref "SV31") (pin "27") (pinfunction "27_27") (pintype "passive"))
      (node (ref "SV31") (pin "28") (pinfunction "28_28") (pintype "passive"))
      (node (ref "SV32") (pin "28") (pinfunction "28_28") (pintype "passive"))
    )
    (net (code "370") (name "Net-(SV31-Pad29)") (class "Default")
      (node (ref "SV31") (pin "29") (pinfunction "29_29") (pintype "passive"))
      (node (ref "SV31") (pin "30") (pinfunction "30_30") (pintype "passive"))
      (node (ref "SV32") (pin "30") (pinfunction "30_30") (pintype "passive"))
    )
    (net (code "371") (name "Net-(SV31-Pad31)") (class "Default")
      (node (ref "SV31") (pin "31") (pinfunction "31_31") (pintype "passive"))
      (node (ref "SV31") (pin "32") (pinfunction "32_32") (pintype "passive"))
      (node (ref "SV32") (pin "32") (pinfunction "32_32") (pintype "passive"))
    )
    (net (code "372") (name "Net-(SV31-Pad33)") (class "Default")
      (node (ref "SV31") (pin "33") (pinfunction "33_33") (pintype "passive"))
      (node (ref "SV31") (pin "34") (pinfunction "34_34") (pintype "passive"))
      (node (ref "SV32") (pin "34") (pinfunction "34_34") (pintype "passive"))
    )
    (net (code "373") (name "Net-(SV31-Pad35)") (class "Default")
      (node (ref "SV31") (pin "35") (pinfunction "35_35") (pintype "passive"))
      (node (ref "SV31") (pin "36") (pinfunction "36_36") (pintype "passive"))
      (node (ref "SV32") (pin "36") (pinfunction "36_36") (pintype "passive"))
    )
    (net (code "374") (name "Net-(SV33-Pad1)") (class "Default")
      (node (ref "SV33") (pin "1") (pinfunction "1_1") (pintype "passive"))
      (node (ref "SV33") (pin "2") (pinfunction "2_2") (pintype "passive"))
      (node (ref "SV34") (pin "1") (pinfunction "1_1") (pintype "passive"))
    )
    (net (code "375") (name "Net-(SV33-Pad3)") (class "Default")
      (node (ref "SV33") (pin "3") (pinfunction "3_3") (pintype "passive"))
      (node (ref "SV33") (pin "4") (pinfunction "4_4") (pintype "passive"))
      (node (ref "SV34") (pin "3") (pinfunction "3_3") (pintype "passive"))
    )
    (net (code "376") (name "Net-(SV33-Pad5)") (class "Default")
      (node (ref "SV33") (pin "5") (pinfunction "5_5") (pintype "passive"))
      (node (ref "SV33") (pin "6") (pinfunction "6_6") (pintype "passive"))
      (node (ref "SV34") (pin "5") (pinfunction "5_5") (pintype "passive"))
    )
    (net (code "377") (name "Net-(SV33-Pad7)") (class "Default")
      (node (ref "SV33") (pin "7") (pinfunction "7_7") (pintype "passive"))
      (node (ref "SV33") (pin "8") (pinfunction "8_8") (pintype "passive"))
      (node (ref "SV34") (pin "7") (pinfunction "7_7") (pintype "passive"))
    )
    (net (code "378") (name "Net-(SV33-Pad10)") (class "Default")
      (node (ref "SV33") (pin "10") (pinfunction "10_10") (pintype "passive"))
      (node (ref "SV33") (pin "9") (pinfunction "9_9") (pintype "passive"))
      (node (ref "SV34") (pin "9") (pinfunction "9_9") (pintype "passive"))
    )
    (net (code "379") (name "Net-(SV33-Pad11)") (class "Default")
      (node (ref "SV33") (pin "11") (pinfunction "11_11") (pintype "passive"))
      (node (ref "SV33") (pin "12") (pinfunction "12_12") (pintype "passive"))
      (node (ref "SV34") (pin "11") (pinfunction "11_11") (pintype "passive"))
    )
    (net (code "380") (name "Net-(SV33-Pad13)") (class "Default")
      (node (ref "SV33") (pin "13") (pinfunction "13_13") (pintype "passive"))
      (node (ref "SV33") (pin "14") (pinfunction "14_14") (pintype "passive"))
      (node (ref "SV34") (pin "13") (pinfunction "13_13") (pintype "passive"))
    )
    (net (code "381") (name "Net-(SV33-Pad15)") (class "Default")
      (node (ref "SV33") (pin "15") (pinfunction "15_15") (pintype "passive"))
      (node (ref "SV33") (pin "16") (pinfunction "16_16") (pintype "passive"))
      (node (ref "SV34") (pin "15") (pinfunction "15_15") (pintype "passive"))
    )
    (net (code "382") (name "Net-(SV33-Pad17)") (class "Default")
      (node (ref "SV33") (pin "17") (pinfunction "17_17") (pintype "passive"))
      (node (ref "SV33") (pin "18") (pinfunction "18_18") (pintype "passive"))
      (node (ref "SV34") (pin "17") (pinfunction "17_17") (pintype "passive"))
    )
    (net (code "383") (name "Net-(SV33-Pad19)") (class "Default")
      (node (ref "SV33") (pin "19") (pinfunction "19_19") (pintype "passive"))
      (node (ref "SV33") (pin "20") (pinfunction "20_20") (pintype "passive"))
      (node (ref "SV34") (pin "19") (pinfunction "19_19") (pintype "passive"))
    )
    (net (code "384") (name "Net-(SV33-Pad21)") (class "Default")
      (node (ref "SV33") (pin "21") (pinfunction "21_21") (pintype "passive"))
      (node (ref "SV33") (pin "22") (pinfunction "22_22") (pintype "passive"))
      (node (ref "SV34") (pin "21") (pinfunction "21_21") (pintype "passive"))
    )
    (net (code "385") (name "Net-(SV33-Pad23)") (class "Default")
      (node (ref "SV33") (pin "23") (pinfunction "23_23") (pintype "passive"))
      (node (ref "SV33") (pin "24") (pinfunction "24_24") (pintype "passive"))
      (node (ref "SV34") (pin "23") (pinfunction "23_23") (pintype "passive"))
    )
    (net (code "386") (name "Net-(SV33-Pad25)") (class "Default")
      (node (ref "SV33") (pin "25") (pinfunction "25_25") (pintype "passive"))
      (node (ref "SV33") (pin "26") (pinfunction "26_26") (pintype "passive"))
      (node (ref "SV34") (pin "25") (pinfunction "25_25") (pintype "passive"))
    )
    (net (code "387") (name "Net-(SV33-Pad27)") (class "Default")
      (node (ref "SV33") (pin "27") (pinfunction "27_27") (pintype "passive"))
      (node (ref "SV33") (pin "28") (pinfunction "28_28") (pintype "passive"))
      (node (ref "SV34") (pin "27") (pinfunction "27_27") (pintype "passive"))
    )
    (net (code "388") (name "Net-(SV33-Pad29)") (class "Default")
      (node (ref "SV33") (pin "29") (pinfunction "29_29") (pintype "passive"))
      (node (ref "SV33") (pin "30") (pinfunction "30_30") (pintype "passive"))
      (node (ref "SV34") (pin "29") (pinfunction "29_29") (pintype "passive"))
    )
    (net (code "389") (name "Net-(SV33-Pad31)") (class "Default")
      (node (ref "SV33") (pin "31") (pinfunction "31_31") (pintype "passive"))
      (node (ref "SV33") (pin "32") (pinfunction "32_32") (pintype "passive"))
      (node (ref "SV34") (pin "31") (pinfunction "31_31") (pintype "passive"))
    )
    (net (code "390") (name "Net-(SV33-Pad33)") (class "Default")
      (node (ref "SV33") (pin "33") (pinfunction "33_33") (pintype "passive"))
      (node (ref "SV33") (pin "34") (pinfunction "34_34") (pintype "passive"))
      (node (ref "SV34") (pin "33") (pinfunction "33_33") (pintype "passive"))
    )
    (net (code "391") (name "Net-(SV33-Pad35)") (class "Default")
      (node (ref "SV33") (pin "35") (pinfunction "35_35") (pintype "passive"))
      (node (ref "SV33") (pin "36") (pinfunction "36_36") (pintype "passive"))
      (node (ref "SV34") (pin "35") (pinfunction "35_35") (pintype "passive"))
    )
    (net (code "392") (name "Net-(SV35-Pad1)") (class "Default")
      (node (ref "SV35") (pin "1") (pinfunction "1_1") (pintype "passive"))
      (node (ref "SV35") (pin "2") (pinfunction "2_2") (pintype "passive"))
      (node (ref "SV36") (pin "1") (pinfunction "1_1") (pintype "passive"))
    )
    (net (code "393") (name "Net-(SV35-Pad3)") (class "Default")
      (node (ref "SV35") (pin "3") (pinfunction "3_3") (pintype "passive"))
      (node (ref "SV35") (pin "4") (pinfunction "4_4") (pintype "passive"))
      (node (ref "SV36") (pin "3") (pinfunction "3_3") (pintype "passive"))
    )
    (net (code "394") (name "Net-(SV35-Pad5)") (class "Default")
      (node (ref "SV35") (pin "5") (pinfunction "5_5") (pintype "passive"))
      (node (ref "SV35") (pin "6") (pinfunction "6_6") (pintype "passive"))
      (node (ref "SV36") (pin "5") (pinfunction "5_5") (pintype "passive"))
    )
    (net (code "395") (name "Net-(SV35-Pad7)") (class "Default")
      (node (ref "SV35") (pin "7") (pinfunction "7_7") (pintype "passive"))
      (node (ref "SV35") (pin "8") (pinfunction "8_8") (pintype "passive"))
      (node (ref "SV36") (pin "7") (pinfunction "7_7") (pintype "passive"))
    )
    (net (code "396") (name "Net-(SV35-Pad10)") (class "Default")
      (node (ref "SV35") (pin "10") (pinfunction "10_10") (pintype "passive"))
      (node (ref "SV35") (pin "9") (pinfunction "9_9") (pintype "passive"))
      (node (ref "SV36") (pin "9") (pinfunction "9_9") (pintype "passive"))
    )
    (net (code "397") (name "Net-(SV35-Pad11)") (class "Default")
      (node (ref "SV35") (pin "11") (pinfunction "11_11") (pintype "passive"))
      (node (ref "SV35") (pin "12") (pinfunction "12_12") (pintype "passive"))
      (node (ref "SV36") (pin "11") (pinfunction "11_11") (pintype "passive"))
    )
    (net (code "398") (name "Net-(SV35-Pad13)") (class "Default")
      (node (ref "SV35") (pin "13") (pinfunction "13_13") (pintype "passive"))
      (node (ref "SV35") (pin "14") (pinfunction "14_14") (pintype "passive"))
      (node (ref "SV36") (pin "13") (pinfunction "13_13") (pintype "passive"))
    )
    (net (code "399") (name "Net-(SV35-Pad15)") (class "Default")
      (node (ref "SV35") (pin "15") (pinfunction "15_15") (pintype "passive"))
      (node (ref "SV35") (pin "16") (pinfunction "16_16") (pintype "passive"))
      (node (ref "SV36") (pin "15") (pinfunction "15_15") (pintype "passive"))
    )
    (net (code "400") (name "Net-(SV35-Pad17)") (class "Default")
      (node (ref "SV35") (pin "17") (pinfunction "17_17") (pintype "passive"))
      (node (ref "SV35") (pin "18") (pinfunction "18_18") (pintype "passive"))
      (node (ref "SV36") (pin "17") (pinfunction "17_17") (pintype "passive"))
    )
    (net (code "401") (name "Net-(SV35-Pad19)") (class "Default")
      (node (ref "SV35") (pin "19") (pinfunction "19_19") (pintype "passive"))
      (node (ref "SV35") (pin "20") (pinfunction "20_20") (pintype "passive"))
      (node (ref "SV36") (pin "19") (pinfunction "19_19") (pintype "passive"))
    )
    (net (code "402") (name "Net-(SV35-Pad21)") (class "Default")
      (node (ref "SV35") (pin "21") (pinfunction "21_21") (pintype "passive"))
      (node (ref "SV35") (pin "22") (pinfunction "22_22") (pintype "passive"))
      (node (ref "SV36") (pin "21") (pinfunction "21_21") (pintype "passive"))
    )
    (net (code "403") (name "Net-(SV35-Pad23)") (class "Default")
      (node (ref "SV35") (pin "23") (pinfunction "23_23") (pintype "passive"))
      (node (ref "SV35") (pin "24") (pinfunction "24_24") (pintype "passive"))
      (node (ref "SV36") (pin "23") (pinfunction "23_23") (pintype "passive"))
    )
    (net (code "404") (name "Net-(SV35-Pad25)") (class "Default")
      (node (ref "SV35") (pin "25") (pinfunction "25_25") (pintype "passive"))
      (node (ref "SV35") (pin "26") (pinfunction "26_26") (pintype "passive"))
      (node (ref "SV36") (pin "25") (pinfunction "25_25") (pintype "passive"))
    )
    (net (code "405") (name "Net-(SV35-Pad27)") (class "Default")
      (node (ref "SV35") (pin "27") (pinfunction "27_27") (pintype "passive"))
      (node (ref "SV35") (pin "28") (pinfunction "28_28") (pintype "passive"))
      (node (ref "SV36") (pin "27") (pinfunction "27_27") (pintype "passive"))
    )
    (net (code "406") (name "Net-(SV35-Pad29)") (class "Default")
      (node (ref "SV35") (pin "29") (pinfunction "29_29") (pintype "passive"))
      (node (ref "SV35") (pin "30") (pinfunction "30_30") (pintype "passive"))
      (node (ref "SV36") (pin "29") (pinfunction "29_29") (pintype "passive"))
    )
    (net (code "407") (name "Net-(SV35-Pad31)") (class "Default")
      (node (ref "SV35") (pin "31") (pinfunction "31_31") (pintype "passive"))
      (node (ref "SV35") (pin "32") (pinfunction "32_32") (pintype "passive"))
      (node (ref "SV36") (pin "31") (pinfunction "31_31") (pintype "passive"))
    )
    (net (code "408") (name "Net-(SV35-Pad33)") (class "Default")
      (node (ref "SV35") (pin "33") (pinfunction "33_33") (pintype "passive"))
      (node (ref "SV35") (pin "34") (pinfunction "34_34") (pintype "passive"))
      (node (ref "SV36") (pin "33") (pinfunction "33_33") (pintype "passive"))
    )
    (net (code "409") (name "Net-(SV35-Pad35)") (class "Default")
      (node (ref "SV35") (pin "35") (pinfunction "35_35") (pintype "passive"))
      (node (ref "SV35") (pin "36") (pinfunction "36_36") (pintype "passive"))
      (node (ref "SV36") (pin "35") (pinfunction "35_35") (pintype "passive"))
    )
    (net (code "410") (name "Net-(SV35-Pad37)") (class "Default")
      (node (ref "SV35") (pin "37") (pinfunction "37_37") (pintype "passive"))
      (node (ref "SV35") (pin "38") (pinfunction "38_38") (pintype "passive"))
      (node (ref "SV36") (pin "37") (pinfunction "37_37") (pintype "passive"))
    )
    (net (code "411") (name "Net-(SV35-Pad39)") (class "Default")
      (node (ref "SV35") (pin "39") (pinfunction "39_39") (pintype "passive"))
      (node (ref "SV35") (pin "40") (pinfunction "40_40") (pintype "passive"))
      (node (ref "SV36") (pin "39") (pinfunction "39_39") (pintype "passive"))
    )
    (net (code "412") (name "Net-(SV37-Pad1)") (class "Default")
      (node (ref "SV37") (pin "1") (pinfunction "1_1") (pintype "passive"))
      (node (ref "SV37") (pin "2") (pinfunction "2_2") (pintype "passive"))
      (node (ref "SV38") (pin "2") (pinfunction "2_2") (pintype "passive"))
    )
    (net (code "413") (name "Net-(SV37-Pad3)") (class "Default")
      (node (ref "SV37") (pin "3") (pinfunction "3_3") (pintype "passive"))
      (node (ref "SV37") (pin "4") (pinfunction "4_4") (pintype "passive"))
      (node (ref "SV38") (pin "4") (pinfunction "4_4") (pintype "passive"))
    )
    (net (code "414") (name "Net-(SV37-Pad5)") (class "Default")
      (node (ref "SV37") (pin "5") (pinfunction "5_5") (pintype "passive"))
      (node (ref "SV37") (pin "6") (pinfunction "6_6") (pintype "passive"))
      (node (ref "SV38") (pin "6") (pinfunction "6_6") (pintype "passive"))
    )
    (net (code "415") (name "Net-(SV37-Pad7)") (class "Default")
      (node (ref "SV37") (pin "7") (pinfunction "7_7") (pintype "passive"))
      (node (ref "SV37") (pin "8") (pinfunction "8_8") (pintype "passive"))
      (node (ref "SV38") (pin "8") (pinfunction "8_8") (pintype "passive"))
    )
    (net (code "416") (name "Net-(SV37-Pad10)") (class "Default")
      (node (ref "SV37") (pin "10") (pinfunction "10_10") (pintype "passive"))
      (node (ref "SV37") (pin "9") (pinfunction "9_9") (pintype "passive"))
      (node (ref "SV38") (pin "10") (pinfunction "10_10") (pintype "passive"))
    )
    (net (code "417") (name "Net-(SV37-Pad11)") (class "Default")
      (node (ref "SV37") (pin "11") (pinfunction "11_11") (pintype "passive"))
      (node (ref "SV37") (pin "12") (pinfunction "12_12") (pintype "passive"))
      (node (ref "SV38") (pin "12") (pinfunction "12_12") (pintype "passive"))
    )
    (net (code "418") (name "Net-(SV37-Pad13)") (class "Default")
      (node (ref "SV37") (pin "13") (pinfunction "13_13") (pintype "passive"))
      (node (ref "SV37") (pin "14") (pinfunction "14_14") (pintype "passive"))
      (node (ref "SV38") (pin "14") (pinfunction "14_14") (pintype "passive"))
    )
    (net (code "419") (name "Net-(SV37-Pad15)") (class "Default")
      (node (ref "SV37") (pin "15") (pinfunction "15_15") (pintype "passive"))
      (node (ref "SV37") (pin "16") (pinfunction "16_16") (pintype "passive"))
      (node (ref "SV38") (pin "16") (pinfunction "16_16") (pintype "passive"))
    )
    (net (code "420") (name "Net-(SV37-Pad17)") (class "Default")
      (node (ref "SV37") (pin "17") (pinfunction "17_17") (pintype "passive"))
      (node (ref "SV37") (pin "18") (pinfunction "18_18") (pintype "passive"))
      (node (ref "SV38") (pin "18") (pinfunction "18_18") (pintype "passive"))
    )
    (net (code "421") (name "Net-(SV37-Pad19)") (class "Default")
      (node (ref "SV37") (pin "19") (pinfunction "19_19") (pintype "passive"))
      (node (ref "SV37") (pin "20") (pinfunction "20_20") (pintype "passive"))
      (node (ref "SV38") (pin "20") (pinfunction "20_20") (pintype "passive"))
    )
    (net (code "422") (name "Net-(SV37-Pad21)") (class "Default")
      (node (ref "SV37") (pin "21") (pinfunction "21_21") (pintype "passive"))
      (node (ref "SV37") (pin "22") (pinfunction "22_22") (pintype "passive"))
      (node (ref "SV38") (pin "22") (pinfunction "22_22") (pintype "passive"))
    )
    (net (code "423") (name "Net-(SV37-Pad23)") (class "Default")
      (node (ref "SV37") (pin "23") (pinfunction "23_23") (pintype "passive"))
      (node (ref "SV37") (pin "24") (pinfunction "24_24") (pintype "passive"))
      (node (ref "SV38") (pin "24") (pinfunction "24_24") (pintype "passive"))
    )
    (net (code "424") (name "Net-(SV37-Pad25)") (class "Default")
      (node (ref "SV37") (pin "25") (pinfunction "25_25") (pintype "passive"))
      (node (ref "SV37") (pin "26") (pinfunction "26_26") (pintype "passive"))
      (node (ref "SV38") (pin "26") (pinfunction "26_26") (pintype "passive"))
    )
    (net (code "425") (name "Net-(SV37-Pad27)") (class "Default")
      (node (ref "SV37") (pin "27") (pinfunction "27_27") (pintype "passive"))
      (node (ref "SV37") (pin "28") (pinfunction "28_28") (pintype "passive"))
      (node (ref "SV38") (pin "28") (pinfunction "28_28") (pintype "passive"))
    )
    (net (code "426") (name "Net-(SV37-Pad29)") (class "Default")
      (node (ref "SV37") (pin "29") (pinfunction "29_29") (pintype "passive"))
      (node (ref "SV37") (pin "30") (pinfunction "30_30") (pintype "passive"))
      (node (ref "SV38") (pin "30") (pinfunction "30_30") (pintype "passive"))
    )
    (net (code "427") (name "Net-(SV37-Pad31)") (class "Default")
      (node (ref "SV37") (pin "31") (pinfunction "31_31") (pintype "passive"))
      (node (ref "SV37") (pin "32") (pinfunction "32_32") (pintype "passive"))
      (node (ref "SV38") (pin "32") (pinfunction "32_32") (pintype "passive"))
    )
    (net (code "428") (name "Net-(SV37-Pad33)") (class "Default")
      (node (ref "SV37") (pin "33") (pinfunction "33_33") (pintype "passive"))
      (node (ref "SV37") (pin "34") (pinfunction "34_34") (pintype "passive"))
      (node (ref "SV38") (pin "34") (pinfunction "34_34") (pintype "passive"))
    )
    (net (code "429") (name "Net-(SV37-Pad35)") (class "Default")
      (node (ref "SV37") (pin "35") (pinfunction "35_35") (pintype "passive"))
      (node (ref "SV37") (pin "36") (pinfunction "36_36") (pintype "passive"))
      (node (ref "SV38") (pin "36") (pinfunction "36_36") (pintype "passive"))
    )
    (net (code "430") (name "Net-(SV37-Pad37)") (class "Default")
      (node (ref "SV37") (pin "37") (pinfunction "37_37") (pintype "passive"))
      (node (ref "SV37") (pin "38") (pinfunction "38_38") (pintype "passive"))
      (node (ref "SV38") (pin "38") (pinfunction "38_38") (pintype "passive"))
    )
    (net (code "431") (name "Net-(SV37-Pad39)") (class "Default")
      (node (ref "SV37") (pin "39") (pinfunction "39_39") (pintype "passive"))
      (node (ref "SV37") (pin "40") (pinfunction "40_40") (pintype "passive"))
      (node (ref "SV38") (pin "40") (pinfunction "40_40") (pintype "passive"))
    )
    (net (code "432") (name "Net-(SV39-Pad1)") (class "Default")
      (node (ref "SV39") (pin "1") (pinfunction "1_1") (pintype "passive"))
      (node (ref "SV39") (pin "2") (pinfunction "2_2") (pintype "passive"))
      (node (ref "SV40") (pin "2") (pinfunction "2_2") (pintype "passive"))
    )
    (net (code "433") (name "Net-(SV39-Pad3)") (class "Default")
      (node (ref "SV39") (pin "3") (pinfunction "3_3") (pintype "passive"))
      (node (ref "SV39") (pin "4") (pinfunction "4_4") (pintype "passive"))
      (node (ref "SV40") (pin "4") (pinfunction "4_4") (pintype "passive"))
    )
    (net (code "434") (name "Net-(SV39-Pad5)") (class "Default")
      (node (ref "SV39") (pin "5") (pinfunction "5_5") (pintype "passive"))
      (node (ref "SV39") (pin "6") (pinfunction "6_6") (pintype "passive"))
      (node (ref "SV40") (pin "6") (pinfunction "6_6") (pintype "passive"))
    )
    (net (code "435") (name "Net-(SV39-Pad7)") (class "Default")
      (node (ref "SV39") (pin "7") (pinfunction "7_7") (pintype "passive"))
      (node (ref "SV39") (pin "8") (pinfunction "8_8") (pintype "passive"))
      (node (ref "SV40") (pin "8") (pinfunction "8_8") (pintype "passive"))
    )
    (net (code "436") (name "Net-(SV39-Pad10)") (class "Default")
      (node (ref "SV39") (pin "10") (pinfunction "10_10") (pintype "passive"))
      (node (ref "SV39") (pin "9") (pinfunction "9_9") (pintype "passive"))
      (node (ref "SV40") (pin "10") (pinfunction "10_10") (pintype "passive"))
    )
    (net (code "437") (name "Net-(SV39-Pad11)") (class "Default")
      (node (ref "SV39") (pin "11") (pinfunction "11_11") (pintype "passive"))
      (node (ref "SV39") (pin "12") (pinfunction "12_12") (pintype "passive"))
      (node (ref "SV40") (pin "12") (pinfunction "12_12") (pintype "passive"))
    )
    (net (code "438") (name "Net-(SV39-Pad13)") (class "Default")
      (node (ref "SV39") (pin "13") (pinfunction "13_13") (pintype "passive"))
      (node (ref "SV39") (pin "14") (pinfunction "14_14") (pintype "passive"))
      (node (ref "SV40") (pin "14") (pinfunction "14_14") (pintype "passive"))
    )
    (net (code "439") (name "Net-(SV39-Pad15)") (class "Default")
      (node (ref "SV39") (pin "15") (pinfunction "15_15") (pintype "passive"))
      (node (ref "SV39") (pin "16") (pinfunction "16_16") (pintype "passive"))
      (node (ref "SV40") (pin "16") (pinfunction "16_16") (pintype "passive"))
    )
    (net (code "440") (name "Net-(SV39-Pad17)") (class "Default")
      (node (ref "SV39") (pin "17") (pinfunction "17_17") (pintype "passive"))
      (node (ref "SV39") (pin "18") (pinfunction "18_18") (pintype "passive"))
      (node (ref "SV40") (pin "18") (pinfunction "18_18") (pintype "passive"))
    )
    (net (code "441") (name "Net-(SV39-Pad19)") (class "Default")
      (node (ref "SV39") (pin "19") (pinfunction "19_19") (pintype "passive"))
      (node (ref "SV39") (pin "20") (pinfunction "20_20") (pintype "passive"))
      (node (ref "SV40") (pin "20") (pinfunction "20_20") (pintype "passive"))
    )
    (net (code "442") (name "Net-(SV39-Pad21)") (class "Default")
      (node (ref "SV39") (pin "21") (pinfunction "21_21") (pintype "passive"))
      (node (ref "SV39") (pin "22") (pinfunction "22_22") (pintype "passive"))
      (node (ref "SV40") (pin "22") (pinfunction "22_22") (pintype "passive"))
    )
    (net (code "443") (name "Net-(SV39-Pad23)") (class "Default")
      (node (ref "SV39") (pin "23") (pinfunction "23_23") (pintype "passive"))
      (node (ref "SV39") (pin "24") (pinfunction "24_24") (pintype "passive"))
      (node (ref "SV40") (pin "24") (pinfunction "24_24") (pintype "passive"))
    )
    (net (code "444") (name "Net-(SV39-Pad25)") (class "Default")
      (node (ref "SV39") (pin "25") (pinfunction "25_25") (pintype "passive"))
      (node (ref "SV39") (pin "26") (pinfunction "26_26") (pintype "passive"))
      (node (ref "SV40") (pin "26") (pinfunction "26_26") (pintype "passive"))
    )
    (net (code "445") (name "Net-(SV39-Pad27)") (class "Default")
      (node (ref "SV39") (pin "27") (pinfunction "27_27") (pintype "passive"))
      (node (ref "SV39") (pin "28") (pinfunction "28_28") (pintype "passive"))
      (node (ref "SV40") (pin "28") (pinfunction "28_28") (pintype "passive"))
    )
    (net (code "446") (name "Net-(SV39-Pad29)") (class "Default")
      (node (ref "SV39") (pin "29") (pinfunction "29_29") (pintype "passive"))
      (node (ref "SV39") (pin "30") (pinfunction "30_30") (pintype "passive"))
      (node (ref "SV40") (pin "30") (pinfunction "30_30") (pintype "passive"))
    )
    (net (code "447") (name "Net-(SV39-Pad31)") (class "Default")
      (node (ref "SV39") (pin "31") (pinfunction "31_31") (pintype "passive"))
      (node (ref "SV39") (pin "32") (pinfunction "32_32") (pintype "passive"))
      (node (ref "SV40") (pin "32") (pinfunction "32_32") (pintype "passive"))
    )
    (net (code "448") (name "Net-(SV39-Pad33)") (class "Default")
      (node (ref "SV39") (pin "33") (pinfunction "33_33") (pintype "passive"))
      (node (ref "SV39") (pin "34") (pinfunction "34_34") (pintype "passive"))
      (node (ref "SV40") (pin "34") (pinfunction "34_34") (pintype "passive"))
    )
    (net (code "449") (name "Net-(SV39-Pad35)") (class "Default")
      (node (ref "SV39") (pin "35") (pinfunction "35_35") (pintype "passive"))
      (node (ref "SV39") (pin "36") (pinfunction "36_36") (pintype "passive"))
      (node (ref "SV40") (pin "36") (pinfunction "36_36") (pintype "passive"))
    )
    (net (code "450") (name "Net-(SV41-Pad1)") (class "Default")
      (node (ref "SV41") (pin "1") (pinfunction "1_1") (pintype "passive"))
      (node (ref "SV41") (pin "2") (pinfunction "2_2") (pintype "passive"))
      (node (ref "SV42") (pin "1") (pinfunction "1_1") (pintype "passive"))
    )
    (net (code "451") (name "Net-(SV41-Pad3)") (class "Default")
      (node (ref "SV41") (pin "3") (pinfunction "3_3") (pintype "passive"))
      (node (ref "SV41") (pin "4") (pinfunction "4_4") (pintype "passive"))
      (node (ref "SV42") (pin "3") (pinfunction "3_3") (pintype "passive"))
    )
    (net (code "452") (name "Net-(SV41-Pad5)") (class "Default")
      (node (ref "SV41") (pin "5") (pinfunction "5_5") (pintype "passive"))
      (node (ref "SV41") (pin "6") (pinfunction "6_6") (pintype "passive"))
      (node (ref "SV42") (pin "5") (pinfunction "5_5") (pintype "passive"))
    )
    (net (code "453") (name "Net-(SV41-Pad7)") (class "Default")
      (node (ref "SV41") (pin "7") (pinfunction "7_7") (pintype "passive"))
      (node (ref "SV41") (pin "8") (pinfunction "8_8") (pintype "passive"))
      (node (ref "SV42") (pin "7") (pinfunction "7_7") (pintype "passive"))
    )
    (net (code "454") (name "Net-(SV41-Pad10)") (class "Default")
      (node (ref "SV41") (pin "10") (pinfunction "10_10") (pintype "passive"))
      (node (ref "SV41") (pin "9") (pinfunction "9_9") (pintype "passive"))
      (node (ref "SV42") (pin "9") (pinfunction "9_9") (pintype "passive"))
    )
    (net (code "455") (name "Net-(SV41-Pad11)") (class "Default")
      (node (ref "SV41") (pin "11") (pinfunction "11_11") (pintype "passive"))
      (node (ref "SV41") (pin "12") (pinfunction "12_12") (pintype "passive"))
      (node (ref "SV42") (pin "11") (pinfunction "11_11") (pintype "passive"))
    )
    (net (code "456") (name "Net-(SV41-Pad13)") (class "Default")
      (node (ref "SV41") (pin "13") (pinfunction "13_13") (pintype "passive"))
      (node (ref "SV41") (pin "14") (pinfunction "14_14") (pintype "passive"))
      (node (ref "SV42") (pin "13") (pinfunction "13_13") (pintype "passive"))
    )
    (net (code "457") (name "Net-(SV41-Pad15)") (class "Default")
      (node (ref "SV41") (pin "15") (pinfunction "15_15") (pintype "passive"))
      (node (ref "SV41") (pin "16") (pinfunction "16_16") (pintype "passive"))
      (node (ref "SV42") (pin "15") (pinfunction "15_15") (pintype "passive"))
    )
    (net (code "458") (name "Net-(SV41-Pad17)") (class "Default")
      (node (ref "SV41") (pin "17") (pinfunction "17_17") (pintype "passive"))
      (node (ref "SV41") (pin "18") (pinfunction "18_18") (pintype "passive"))
      (node (ref "SV42") (pin "17") (pinfunction "17_17") (pintype "passive"))
    )
    (net (code "459") (name "Net-(SV41-Pad19)") (class "Default")
      (node (ref "SV41") (pin "19") (pinfunction "19_19") (pintype "passive"))
      (node (ref "SV41") (pin "20") (pinfunction "20_20") (pintype "passive"))
      (node (ref "SV42") (pin "19") (pinfunction "19_19") (pintype "passive"))
    )
    (net (code "460") (name "Net-(SV41-Pad21)") (class "Default")
      (node (ref "SV41") (pin "21") (pinfunction "21_21") (pintype "passive"))
      (node (ref "SV41") (pin "22") (pinfunction "22_22") (pintype "passive"))
      (node (ref "SV42") (pin "21") (pinfunction "21_21") (pintype "passive"))
    )
    (net (code "461") (name "Net-(SV41-Pad23)") (class "Default")
      (node (ref "SV41") (pin "23") (pinfunction "23_23") (pintype "passive"))
      (node (ref "SV41") (pin "24") (pinfunction "24_24") (pintype "passive"))
      (node (ref "SV42") (pin "23") (pinfunction "23_23") (pintype "passive"))
    )
    (net (code "462") (name "Net-(SV41-Pad25)") (class "Default")
      (node (ref "SV41") (pin "25") (pinfunction "25_25") (pintype "passive"))
      (node (ref "SV41") (pin "26") (pinfunction "26_26") (pintype "passive"))
      (node (ref "SV42") (pin "25") (pinfunction "25_25") (pintype "passive"))
    )
    (net (code "463") (name "Net-(SV41-Pad27)") (class "Default")
      (node (ref "SV41") (pin "27") (pinfunction "27_27") (pintype "passive"))
      (node (ref "SV41") (pin "28") (pinfunction "28_28") (pintype "passive"))
      (node (ref "SV42") (pin "27") (pinfunction "27_27") (pintype "passive"))
    )
    (net (code "464") (name "Net-(SV41-Pad29)") (class "Default")
      (node (ref "SV41") (pin "29") (pinfunction "29_29") (pintype "passive"))
      (node (ref "SV41") (pin "30") (pinfunction "30_30") (pintype "passive"))
      (node (ref "SV42") (pin "29") (pinfunction "29_29") (pintype "passive"))
    )
    (net (code "465") (name "Net-(SV41-Pad31)") (class "Default")
      (node (ref "SV41") (pin "31") (pinfunction "31_31") (pintype "passive"))
      (node (ref "SV41") (pin "32") (pinfunction "32_32") (pintype "passive"))
      (node (ref "SV42") (pin "31") (pinfunction "31_31") (pintype "passive"))
    )
    (net (code "466") (name "Net-(SV41-Pad33)") (class "Default")
      (node (ref "SV41") (pin "33") (pinfunction "33_33") (pintype "passive"))
      (node (ref "SV41") (pin "34") (pinfunction "34_34") (pintype "passive"))
      (node (ref "SV42") (pin "33") (pinfunction "33_33") (pintype "passive"))
    )
    (net (code "467") (name "Net-(SV41-Pad35)") (class "Default")
      (node (ref "SV41") (pin "35") (pinfunction "35_35") (pintype "passive"))
      (node (ref "SV41") (pin "36") (pinfunction "36_36") (pintype "passive"))
      (node (ref "SV42") (pin "35") (pinfunction "35_35") (pintype "passive"))
    )
    (net (code "468") (name "Net-(SV43-Pad1)") (class "Default")
      (node (ref "SV43") (pin "1") (pinfunction "1_1") (pintype "passive"))
      (node (ref "SV43") (pin "2") (pinfunction "2_2") (pintype "passive"))
      (node (ref "SV44") (pin "1") (pinfunction "1_1") (pintype "passive"))
    )
    (net (code "469") (name "Net-(SV43-Pad3)") (class "Default")
      (node (ref "SV43") (pin "3") (pinfunction "3_3") (pintype "passive"))
      (node (ref "SV43") (pin "4") (pinfunction "4_4") (pintype "passive"))
      (node (ref "SV44") (pin "3") (pinfunction "3_3") (pintype "passive"))
    )
    (net (code "470") (name "Net-(SV43-Pad5)") (class "Default")
      (node (ref "SV43") (pin "5") (pinfunction "5_5") (pintype "passive"))
      (node (ref "SV43") (pin "6") (pinfunction "6_6") (pintype "passive"))
      (node (ref "SV44") (pin "5") (pinfunction "5_5") (pintype "passive"))
    )
    (net (code "471") (name "Net-(SV43-Pad7)") (class "Default")
      (node (ref "SV43") (pin "7") (pinfunction "7_7") (pintype "passive"))
      (node (ref "SV43") (pin "8") (pinfunction "8_8") (pintype "passive"))
      (node (ref "SV44") (pin "7") (pinfunction "7_7") (pintype "passive"))
    )
    (net (code "472") (name "Net-(SV43-Pad10)") (class "Default")
      (node (ref "SV43") (pin "10") (pinfunction "10_10") (pintype "passive"))
      (node (ref "SV43") (pin "9") (pinfunction "9_9") (pintype "passive"))
      (node (ref "SV44") (pin "9") (pinfunction "9_9") (pintype "passive"))
    )
    (net (code "473") (name "Net-(SV43-Pad11)") (class "Default")
      (node (ref "SV43") (pin "11") (pinfunction "11_11") (pintype "passive"))
      (node (ref "SV43") (pin "12") (pinfunction "12_12") (pintype "passive"))
      (node (ref "SV44") (pin "11") (pinfunction "11_11") (pintype "passive"))
    )
    (net (code "474") (name "Net-(SV43-Pad13)") (class "Default")
      (node (ref "SV43") (pin "13") (pinfunction "13_13") (pintype "passive"))
      (node (ref "SV43") (pin "14") (pinfunction "14_14") (pintype "passive"))
      (node (ref "SV44") (pin "13") (pinfunction "13_13") (pintype "passive"))
    )
    (net (code "475") (name "Net-(SV43-Pad15)") (class "Default")
      (node (ref "SV43") (pin "15") (pinfunction "15_15") (pintype "passive"))
      (node (ref "SV43") (pin "16") (pinfunction "16_16") (pintype "passive"))
      (node (ref "SV44") (pin "15") (pinfunction "15_15") (pintype "passive"))
    )
    (net (code "476") (name "Net-(SV43-Pad17)") (class "Default")
      (node (ref "SV43") (pin "17") (pinfunction "17_17") (pintype "passive"))
      (node (ref "SV43") (pin "18") (pinfunction "18_18") (pintype "passive"))
      (node (ref "SV44") (pin "17") (pinfunction "17_17") (pintype "passive"))
    )
    (net (code "477") (name "Net-(SV43-Pad19)") (class "Default")
      (node (ref "SV43") (pin "19") (pinfunction "19_19") (pintype "passive"))
      (node (ref "SV43") (pin "20") (pinfunction "20_20") (pintype "passive"))
      (node (ref "SV44") (pin "19") (pinfunction "19_19") (pintype "passive"))
    )
    (net (code "478") (name "Net-(SV43-Pad21)") (class "Default")
      (node (ref "SV43") (pin "21") (pinfunction "21_21") (pintype "passive"))
      (node (ref "SV43") (pin "22") (pinfunction "22_22") (pintype "passive"))
      (node (ref "SV44") (pin "21") (pinfunction "21_21") (pintype "passive"))
    )
    (net (code "479") (name "Net-(SV43-Pad23)") (class "Default")
      (node (ref "SV43") (pin "23") (pinfunction "23_23") (pintype "passive"))
      (node (ref "SV43") (pin "24") (pinfunction "24_24") (pintype "passive"))
      (node (ref "SV44") (pin "23") (pinfunction "23_23") (pintype "passive"))
    )
    (net (code "480") (name "Net-(SV43-Pad25)") (class "Default")
      (node (ref "SV43") (pin "25") (pinfunction "25_25") (pintype "passive"))
      (node (ref "SV43") (pin "26") (pinfunction "26_26") (pintype "passive"))
      (node (ref "SV44") (pin "25") (pinfunction "25_25") (pintype "passive"))
    )
    (net (code "481") (name "Net-(SV43-Pad27)") (class "Default")
      (node (ref "SV43") (pin "27") (pinfunction "27_27") (pintype "passive"))
      (node (ref "SV43") (pin "28") (pinfunction "28_28") (pintype "passive"))
      (node (ref "SV44") (pin "27") (pinfunction "27_27") (pintype "passive"))
    )
    (net (code "482") (name "Net-(SV43-Pad29)") (class "Default")
      (node (ref "SV43") (pin "29") (pinfunction "29_29") (pintype "passive"))
      (node (ref "SV43") (pin "30") (pinfunction "30_30") (pintype "passive"))
      (node (ref "SV44") (pin "29") (pinfunction "29_29") (pintype "passive"))
    )
    (net (code "483") (name "Net-(SV43-Pad31)") (class "Default")
      (node (ref "SV43") (pin "31") (pinfunction "31_31") (pintype "passive"))
      (node (ref "SV43") (pin "32") (pinfunction "32_32") (pintype "passive"))
      (node (ref "SV44") (pin "31") (pinfunction "31_31") (pintype "passive"))
    )
    (net (code "484") (name "Net-(SV43-Pad33)") (class "Default")
      (node (ref "SV43") (pin "33") (pinfunction "33_33") (pintype "passive"))
      (node (ref "SV43") (pin "34") (pinfunction "34_34") (pintype "passive"))
      (node (ref "SV44") (pin "33") (pinfunction "33_33") (pintype "passive"))
    )
    (net (code "485") (name "Net-(SV43-Pad35)") (class "Default")
      (node (ref "SV43") (pin "35") (pinfunction "35_35") (pintype "passive"))
      (node (ref "SV43") (pin "36") (pinfunction "36_36") (pintype "passive"))
      (node (ref "SV44") (pin "35") (pinfunction "35_35") (pintype "passive"))
    )
    (net (code "486") (name "Net-(SV43-Pad37)") (class "Default")
      (node (ref "SV43") (pin "37") (pinfunction "37_37") (pintype "passive"))
      (node (ref "SV43") (pin "38") (pinfunction "38_38") (pintype "passive"))
      (node (ref "SV44") (pin "37") (pinfunction "37_37") (pintype "passive"))
    )
    (net (code "487") (name "Net-(SV43-Pad39)") (class "Default")
      (node (ref "SV43") (pin "39") (pinfunction "39_39") (pintype "passive"))
      (node (ref "SV43") (pin "40") (pinfunction "40_40") (pintype "passive"))
      (node (ref "SV44") (pin "39") (pinfunction "39_39") (pintype "passive"))
    )
    (net (code "488") (name "Net-(SV45-Pad1)") (class "Default")
      (node (ref "SV45") (pin "1") (pinfunction "1_1") (pintype "passive"))
      (node (ref "SV45") (pin "2") (pinfunction "2_2") (pintype "passive"))
      (node (ref "SV46") (pin "2") (pinfunction "2_2") (pintype "passive"))
    )
    (net (code "489") (name "Net-(SV45-Pad3)") (class "Default")
      (node (ref "SV45") (pin "3") (pinfunction "3_3") (pintype "passive"))
      (node (ref "SV45") (pin "4") (pinfunction "4_4") (pintype "passive"))
      (node (ref "SV46") (pin "4") (pinfunction "4_4") (pintype "passive"))
    )
    (net (code "490") (name "Net-(SV45-Pad5)") (class "Default")
      (node (ref "SV45") (pin "5") (pinfunction "5_5") (pintype "passive"))
      (node (ref "SV45") (pin "6") (pinfunction "6_6") (pintype "passive"))
      (node (ref "SV46") (pin "6") (pinfunction "6_6") (pintype "passive"))
    )
    (net (code "491") (name "Net-(SV45-Pad7)") (class "Default")
      (node (ref "SV45") (pin "7") (pinfunction "7_7") (pintype "passive"))
      (node (ref "SV45") (pin "8") (pinfunction "8_8") (pintype "passive"))
      (node (ref "SV46") (pin "8") (pinfunction "8_8") (pintype "passive"))
    )
    (net (code "492") (name "Net-(SV45-Pad10)") (class "Default")
      (node (ref "SV45") (pin "10") (pinfunction "10_10") (pintype "passive"))
      (node (ref "SV45") (pin "9") (pinfunction "9_9") (pintype "passive"))
      (node (ref "SV46") (pin "10") (pinfunction "10_10") (pintype "passive"))
    )
    (net (code "493") (name "Net-(SV45-Pad11)") (class "Default")
      (node (ref "SV45") (pin "11") (pinfunction "11_11") (pintype "passive"))
      (node (ref "SV45") (pin "12") (pinfunction "12_12") (pintype "passive"))
      (node (ref "SV46") (pin "12") (pinfunction "12_12") (pintype "passive"))
    )
    (net (code "494") (name "Net-(SV45-Pad13)") (class "Default")
      (node (ref "SV45") (pin "13") (pinfunction "13_13") (pintype "passive"))
      (node (ref "SV45") (pin "14") (pinfunction "14_14") (pintype "passive"))
      (node (ref "SV46") (pin "14") (pinfunction "14_14") (pintype "passive"))
    )
    (net (code "495") (name "Net-(SV45-Pad15)") (class "Default")
      (node (ref "SV45") (pin "15") (pinfunction "15_15") (pintype "passive"))
      (node (ref "SV45") (pin "16") (pinfunction "16_16") (pintype "passive"))
      (node (ref "SV46") (pin "16") (pinfunction "16_16") (pintype "passive"))
    )
    (net (code "496") (name "Net-(SV45-Pad17)") (class "Default")
      (node (ref "SV45") (pin "17") (pinfunction "17_17") (pintype "passive"))
      (node (ref "SV45") (pin "18") (pinfunction "18_18") (pintype "passive"))
      (node (ref "SV46") (pin "18") (pinfunction "18_18") (pintype "passive"))
    )
    (net (code "497") (name "Net-(SV45-Pad19)") (class "Default")
      (node (ref "SV45") (pin "19") (pinfunction "19_19") (pintype "passive"))
      (node (ref "SV45") (pin "20") (pinfunction "20_20") (pintype "passive"))
      (node (ref "SV46") (pin "20") (pinfunction "20_20") (pintype "passive"))
    )
    (net (code "498") (name "Net-(SV45-Pad21)") (class "Default")
      (node (ref "SV45") (pin "21") (pinfunction "21_21") (pintype "passive"))
      (node (ref "SV45") (pin "22") (pinfunction "22_22") (pintype "passive"))
      (node (ref "SV46") (pin "22") (pinfunction "22_22") (pintype "passive"))
    )
    (net (code "499") (name "Net-(SV45-Pad23)") (class "Default")
      (node (ref "SV45") (pin "23") (pinfunction "23_23") (pintype "passive"))
      (node (ref "SV45") (pin "24") (pinfunction "24_24") (pintype "passive"))
      (node (ref "SV46") (pin "24") (pinfunction "24_24") (pintype "passive"))
    )
    (net (code "500") (name "Net-(SV45-Pad25)") (class "Default")
      (node (ref "SV45") (pin "25") (pinfunction "25_25") (pintype "passive"))
      (node (ref "SV45") (pin "26") (pinfunction "26_26") (pintype "passive"))
      (node (ref "SV46") (pin "26") (pinfunction "26_26") (pintype "passive"))
    )
    (net (code "501") (name "Net-(SV45-Pad27)") (class "Default")
      (node (ref "SV45") (pin "27") (pinfunction "27_27") (pintype "passive"))
      (node (ref "SV45") (pin "28") (pinfunction "28_28") (pintype "passive"))
      (node (ref "SV46") (pin "28") (pinfunction "28_28") (pintype "passive"))
    )
    (net (code "502") (name "Net-(SV45-Pad29)") (class "Default")
      (node (ref "SV45") (pin "29") (pinfunction "29_29") (pintype "passive"))
      (node (ref "SV45") (pin "30") (pinfunction "30_30") (pintype "passive"))
      (node (ref "SV46") (pin "30") (pinfunction "30_30") (pintype "passive"))
    )
    (net (code "503") (name "Net-(SV45-Pad31)") (class "Default")
      (node (ref "SV45") (pin "31") (pinfunction "31_31") (pintype "passive"))
      (node (ref "SV45") (pin "32") (pinfunction "32_32") (pintype "passive"))
      (node (ref "SV46") (pin "32") (pinfunction "32_32") (pintype "passive"))
    )
    (net (code "504") (name "Net-(SV45-Pad33)") (class "Default")
      (node (ref "SV45") (pin "33") (pinfunction "33_33") (pintype "passive"))
      (node (ref "SV45") (pin "34") (pinfunction "34_34") (pintype "passive"))
      (node (ref "SV46") (pin "34") (pinfunction "34_34") (pintype "passive"))
    )
    (net (code "505") (name "Net-(SV45-Pad35)") (class "Default")
      (node (ref "SV45") (pin "35") (pinfunction "35_35") (pintype "passive"))
      (node (ref "SV45") (pin "36") (pinfunction "36_36") (pintype "passive"))
      (node (ref "SV46") (pin "36") (pinfunction "36_36") (pintype "passive"))
    )
    (net (code "506") (name "Net-(SV45-Pad37)") (class "Default")
      (node (ref "SV45") (pin "37") (pinfunction "37_37") (pintype "passive"))
      (node (ref "SV45") (pin "38") (pinfunction "38_38") (pintype "passive"))
      (node (ref "SV46") (pin "38") (pinfunction "38_38") (pintype "passive"))
    )
    (net (code "507") (name "Net-(SV45-Pad39)") (class "Default")
      (node (ref "SV45") (pin "39") (pinfunction "39_39") (pintype "passive"))
      (node (ref "SV45") (pin "40") (pinfunction "40_40") (pintype "passive"))
      (node (ref "SV46") (pin "40") (pinfunction "40_40") (pintype "passive"))
    )
    (net (code "508") (name "Net-(SV47-Pad1)") (class "Default")
      (node (ref "SV47") (pin "1") (pinfunction "1_1") (pintype "passive"))
      (node (ref "SV47") (pin "2") (pinfunction "2_2") (pintype "passive"))
      (node (ref "SV48") (pin "2") (pinfunction "2_2") (pintype "passive"))
    )
    (net (code "509") (name "Net-(SV47-Pad3)") (class "Default")
      (node (ref "SV47") (pin "3") (pinfunction "3_3") (pintype "passive"))
      (node (ref "SV47") (pin "4") (pinfunction "4_4") (pintype "passive"))
      (node (ref "SV48") (pin "4") (pinfunction "4_4") (pintype "passive"))
    )
    (net (code "510") (name "Net-(SV47-Pad5)") (class "Default")
      (node (ref "SV47") (pin "5") (pinfunction "5_5") (pintype "passive"))
      (node (ref "SV47") (pin "6") (pinfunction "6_6") (pintype "passive"))
      (node (ref "SV48") (pin "6") (pinfunction "6_6") (pintype "passive"))
    )
    (net (code "511") (name "Net-(SV47-Pad7)") (class "Default")
      (node (ref "SV47") (pin "7") (pinfunction "7_7") (pintype "passive"))
      (node (ref "SV47") (pin "8") (pinfunction "8_8") (pintype "passive"))
      (node (ref "SV48") (pin "8") (pinfunction "8_8") (pintype "passive"))
    )
    (net (code "512") (name "Net-(SV47-Pad10)") (class "Default")
      (node (ref "SV47") (pin "10") (pinfunction "10_10") (pintype "passive"))
      (node (ref "SV47") (pin "9") (pinfunction "9_9") (pintype "passive"))
      (node (ref "SV48") (pin "10") (pinfunction "10_10") (pintype "passive"))
    )
    (net (code "513") (name "Net-(SV47-Pad11)") (class "Default")
      (node (ref "SV47") (pin "11") (pinfunction "11_11") (pintype "passive"))
      (node (ref "SV47") (pin "12") (pinfunction "12_12") (pintype "passive"))
      (node (ref "SV48") (pin "12") (pinfunction "12_12") (pintype "passive"))
    )
    (net (code "514") (name "Net-(SV47-Pad13)") (class "Default")
      (node (ref "SV47") (pin "13") (pinfunction "13_13") (pintype "passive"))
      (node (ref "SV47") (pin "14") (pinfunction "14_14") (pintype "passive"))
      (node (ref "SV48") (pin "14") (pinfunction "14_14") (pintype "passive"))
    )
    (net (code "515") (name "Net-(SV47-Pad15)") (class "Default")
      (node (ref "SV47") (pin "15") (pinfunction "15_15") (pintype "passive"))
      (node (ref "SV47") (pin "16") (pinfunction "16_16") (pintype "passive"))
      (node (ref "SV48") (pin "16") (pinfunction "16_16") (pintype "passive"))
    )
    (net (code "516") (name "Net-(SV47-Pad17)") (class "Default")
      (node (ref "SV47") (pin "17") (pinfunction "17_17") (pintype "passive"))
      (node (ref "SV47") (pin "18") (pinfunction "18_18") (pintype "passive"))
      (node (ref "SV48") (pin "18") (pinfunction "18_18") (pintype "passive"))
    )
    (net (code "517") (name "Net-(SV47-Pad19)") (class "Default")
      (node (ref "SV47") (pin "19") (pinfunction "19_19") (pintype "passive"))
      (node (ref "SV47") (pin "20") (pinfunction "20_20") (pintype "passive"))
      (node (ref "SV48") (pin "20") (pinfunction "20_20") (pintype "passive"))
    )
    (net (code "518") (name "Net-(SV47-Pad21)") (class "Default")
      (node (ref "SV47") (pin "21") (pinfunction "21_21") (pintype "passive"))
      (node (ref "SV47") (pin "22") (pinfunction "22_22") (pintype "passive"))
      (node (ref "SV48") (pin "22") (pinfunction "22_22") (pintype "passive"))
    )
    (net (code "519") (name "Net-(SV47-Pad23)") (class "Default")
      (node (ref "SV47") (pin "23") (pinfunction "23_23") (pintype "passive"))
      (node (ref "SV47") (pin "24") (pinfunction "24_24") (pintype "passive"))
      (node (ref "SV48") (pin "24") (pinfunction "24_24") (pintype "passive"))
    )
    (net (code "520") (name "Net-(SV47-Pad25)") (class "Default")
      (node (ref "SV47") (pin "25") (pinfunction "25_25") (pintype "passive"))
      (node (ref "SV47") (pin "26") (pinfunction "26_26") (pintype "passive"))
      (node (ref "SV48") (pin "26") (pinfunction "26_26") (pintype "passive"))
    )
    (net (code "521") (name "Net-(SV47-Pad27)") (class "Default")
      (node (ref "SV47") (pin "27") (pinfunction "27_27") (pintype "passive"))
      (node (ref "SV47") (pin "28") (pinfunction "28_28") (pintype "passive"))
      (node (ref "SV48") (pin "28") (pinfunction "28_28") (pintype "passive"))
    )
    (net (code "522") (name "Net-(SV47-Pad29)") (class "Default")
      (node (ref "SV47") (pin "29") (pinfunction "29_29") (pintype "passive"))
      (node (ref "SV47") (pin "30") (pinfunction "30_30") (pintype "passive"))
      (node (ref "SV48") (pin "30") (pinfunction "30_30") (pintype "passive"))
    )
    (net (code "523") (name "Net-(SV47-Pad31)") (class "Default")
      (node (ref "SV47") (pin "31") (pinfunction "31_31") (pintype "passive"))
      (node (ref "SV47") (pin "32") (pinfunction "32_32") (pintype "passive"))
      (node (ref "SV48") (pin "32") (pinfunction "32_32") (pintype "passive"))
    )
    (net (code "524") (name "Net-(SV47-Pad33)") (class "Default")
      (node (ref "SV47") (pin "33") (pinfunction "33_33") (pintype "passive"))
      (node (ref "SV47") (pin "34") (pinfunction "34_34") (pintype "passive"))
      (node (ref "SV48") (pin "34") (pinfunction "34_34") (pintype "passive"))
    )
    (net (code "525") (name "Net-(SV47-Pad35)") (class "Default")
      (node (ref "SV47") (pin "35") (pinfunction "35_35") (pintype "passive"))
      (node (ref "SV47") (pin "36") (pinfunction "36_36") (pintype "passive"))
      (node (ref "SV48") (pin "36") (pinfunction "36_36") (pintype "passive"))
    )
    (net (code "526") (name "Net-(SV49-Pad1)") (class "Default")
      (node (ref "SV49") (pin "1") (pinfunction "1_1") (pintype "passive"))
      (node (ref "SV49") (pin "3") (pinfunction "3_3") (pintype "passive"))
      (node (ref "SV49") (pin "5") (pinfunction "5_5") (pintype "passive"))
    )
    (net (code "527") (name "Net-(SV49-Pad2)") (class "Default")
      (node (ref "SV49") (pin "2") (pinfunction "2_2") (pintype "passive"))
      (node (ref "SV49") (pin "4") (pinfunction "4_4") (pintype "passive"))
      (node (ref "SV49") (pin "6") (pinfunction "6_6") (pintype "passive"))
    )
    (net (code "528") (name "Net-(SV50-Pad1)") (class "Default")
      (node (ref "SV50") (pin "1") (pinfunction "1_1") (pintype "passive"))
      (node (ref "SV50") (pin "3") (pinfunction "3_3") (pintype "passive"))
      (node (ref "SV50") (pin "5") (pinfunction "5_5") (pintype "passive"))
    )
    (net (code "529") (name "Net-(SV50-Pad2)") (class "Default")
      (node (ref "SV50") (pin "2") (pinfunction "2_2") (pintype "passive"))
      (node (ref "SV50") (pin "4") (pinfunction "4_4") (pintype "passive"))
      (node (ref "SV50") (pin "6") (pinfunction "6_6") (pintype "passive"))
    )
    (net (code "530") (name "Net-(SV51-Pad1)") (class "Default")
      (node (ref "SV51") (pin "1") (pinfunction "1_1") (pintype "passive"))
      (node (ref "SV51") (pin "3") (pinfunction "3_3") (pintype "passive"))
      (node (ref "SV51") (pin "5") (pinfunction "5_5") (pintype "passive"))
    )
    (net (code "531") (name "Net-(SV51-Pad2)") (class "Default")
      (node (ref "SV51") (pin "2") (pinfunction "2_2") (pintype "passive"))
      (node (ref "SV51") (pin "4") (pinfunction "4_4") (pintype "passive"))
      (node (ref "SV51") (pin "6") (pinfunction "6_6") (pintype "passive"))
    )
    (net (code "532") (name "Net-(SV52-Pad1)") (class "Default")
      (node (ref "SV52") (pin "1") (pinfunction "1_1") (pintype "passive"))
      (node (ref "SV52") (pin "3") (pinfunction "3_3") (pintype "passive"))
      (node (ref "SV52") (pin "5") (pinfunction "5_5") (pintype "passive"))
    )
    (net (code "533") (name "Net-(SV52-Pad2)") (class "Default")
      (node (ref "SV52") (pin "2") (pinfunction "2_2") (pintype "passive"))
      (node (ref "SV52") (pin "4") (pinfunction "4_4") (pintype "passive"))
      (node (ref "SV52") (pin "6") (pinfunction "6_6") (pintype "passive"))
    )
    (net (code "534") (name "Net-(SV53-Pad1)") (class "Default")
      (node (ref "SV53") (pin "1") (pinfunction "1_1") (pintype "passive"))
      (node (ref "SV53") (pin "3") (pinfunction "3_3") (pintype "passive"))
      (node (ref "SV53") (pin "5") (pinfunction "5_5") (pintype "passive"))
    )
    (net (code "535") (name "Net-(SV53-Pad2)") (class "Default")
      (node (ref "SV53") (pin "2") (pinfunction "2_2") (pintype "passive"))
      (node (ref "SV53") (pin "4") (pinfunction "4_4") (pintype "passive"))
      (node (ref "SV53") (pin "6") (pinfunction "6_6") (pintype "passive"))
    )
    (net (code "536") (name "Net-(SV54-Pad1)") (class "Default")
      (node (ref "SV54") (pin "1") (pinfunction "1_1") (pintype "passive"))
      (node (ref "SV54") (pin "3") (pinfunction "3_3") (pintype "passive"))
      (node (ref "SV54") (pin "5") (pinfunction "5_5") (pintype "passive"))
    )
    (net (code "537") (name "Net-(SV54-Pad2)") (class "Default")
      (node (ref "SV54") (pin "2") (pinfunction "2_2") (pintype "passive"))
      (node (ref "SV54") (pin "4") (pinfunction "4_4") (pintype "passive"))
      (node (ref "SV54") (pin "6") (pinfunction "6_6") (pintype "passive"))
    )
    (net (code "538") (name "Net-(SV55-Pad1)") (class "Default")
      (node (ref "SV55") (pin "1") (pinfunction "1_1") (pintype "passive"))
      (node (ref "SV55") (pin "3") (pinfunction "3_3") (pintype "passive"))
      (node (ref "SV55") (pin "5") (pinfunction "5_5") (pintype "passive"))
    )
    (net (code "539") (name "Net-(SV55-Pad2)") (class "Default")
      (node (ref "SV55") (pin "2") (pinfunction "2_2") (pintype "passive"))
      (node (ref "SV55") (pin "4") (pinfunction "4_4") (pintype "passive"))
      (node (ref "SV55") (pin "6") (pinfunction "6_6") (pintype "passive"))
    )
    (net (code "540") (name "Net-(SV56-Pad1)") (class "Default")
      (node (ref "SV56") (pin "1") (pinfunction "1_1") (pintype "passive"))
      (node (ref "SV56") (pin "3") (pinfunction "3_3") (pintype "passive"))
      (node (ref "SV56") (pin "5") (pinfunction "5_5") (pintype "passive"))
    )
    (net (code "541") (name "Net-(SV56-Pad2)") (class "Default")
      (node (ref "SV56") (pin "2") (pinfunction "2_2") (pintype "passive"))
      (node (ref "SV56") (pin "4") (pinfunction "4_4") (pintype "passive"))
      (node (ref "SV56") (pin "6") (pinfunction "6_6") (pintype "passive"))
    )
    (net (code "542") (name "Net-(SV57-Pad1)") (class "Default")
      (node (ref "SV57") (pin "1") (pinfunction "1_1") (pintype "passive"))
      (node (ref "SV57") (pin "3") (pinfunction "3_3") (pintype "passive"))
      (node (ref "SV57") (pin "5") (pinfunction "5_5") (pintype "passive"))
    )
    (net (code "543") (name "Net-(SV57-Pad2)") (class "Default")
      (node (ref "SV57") (pin "2") (pinfunction "2_2") (pintype "passive"))
      (node (ref "SV57") (pin "4") (pinfunction "4_4") (pintype "passive"))
      (node (ref "SV57") (pin "6") (pinfunction "6_6") (pintype "passive"))
    )
    (net (code "544") (name "Net-(SV58-Pad1)") (class "Default")
      (node (ref "SV58") (pin "1") (pinfunction "1_1") (pintype "passive"))
      (node (ref "SV58") (pin "3") (pinfunction "3_3") (pintype "passive"))
      (node (ref "SV58") (pin "5") (pinfunction "5_5") (pintype "passive"))
    )
    (net (code "545") (name "Net-(SV58-Pad2)") (class "Default")
      (node (ref "SV58") (pin "2") (pinfunction "2_2") (pintype "passive"))
      (node (ref "SV58") (pin "4") (pinfunction "4_4") (pintype "passive"))
      (node (ref "SV58") (pin "6") (pinfunction "6_6") (pintype "passive"))
    )
    (net (code "546") (name "Net-(SV59-Pad1)") (class "Default")
      (node (ref "SV59") (pin "1") (pinfunction "1_1") (pintype "passive"))
      (node (ref "SV59") (pin "3") (pinfunction "3_3") (pintype "passive"))
      (node (ref "SV59") (pin "5") (pinfunction "5_5") (pintype "passive"))
    )
    (net (code "547") (name "Net-(SV59-Pad2)") (class "Default")
      (node (ref "SV59") (pin "2") (pinfunction "2_2") (pintype "passive"))
      (node (ref "SV59") (pin "4") (pinfunction "4_4") (pintype "passive"))
      (node (ref "SV59") (pin "6") (pinfunction "6_6") (pintype "passive"))
    )
    (net (code "548") (name "Net-(SV60-Pad1)") (class "Default")
      (node (ref "SV60") (pin "1") (pinfunction "1_1") (pintype "passive"))
      (node (ref "SV60") (pin "3") (pinfunction "3_3") (pintype "passive"))
      (node (ref "SV60") (pin "5") (pinfunction "5_5") (pintype "passive"))
    )
    (net (code "549") (name "Net-(SV60-Pad2)") (class "Default")
      (node (ref "SV60") (pin "2") (pinfunction "2_2") (pintype "passive"))
      (node (ref "SV60") (pin "4") (pinfunction "4_4") (pintype "passive"))
      (node (ref "SV60") (pin "6") (pinfunction "6_6") (pintype "passive"))
    )
    (net (code "550") (name "Net-(SV61-Pad1)") (class "Default")
      (node (ref "SV61") (pin "1") (pinfunction "1_1") (pintype "passive"))
      (node (ref "SV61") (pin "3") (pinfunction "3_3") (pintype "passive"))
      (node (ref "SV61") (pin "5") (pinfunction "5_5") (pintype "passive"))
    )
    (net (code "551") (name "Net-(SV61-Pad2)") (class "Default")
      (node (ref "SV61") (pin "2") (pinfunction "2_2") (pintype "passive"))
      (node (ref "SV61") (pin "4") (pinfunction "4_4") (pintype "passive"))
      (node (ref "SV61") (pin "6") (pinfunction "6_6") (pintype "passive"))
    )
    (net (code "552") (name "Net-(SV62-Pad1)") (class "Default")
      (node (ref "SV62") (pin "1") (pinfunction "1_1") (pintype "passive"))
      (node (ref "SV62") (pin "3") (pinfunction "3_3") (pintype "passive"))
      (node (ref "SV62") (pin "5") (pinfunction "5_5") (pintype "passive"))
    )
    (net (code "553") (name "Net-(SV62-Pad2)") (class "Default")
      (node (ref "SV62") (pin "2") (pinfunction "2_2") (pintype "passive"))
      (node (ref "SV62") (pin "4") (pinfunction "4_4") (pintype "passive"))
      (node (ref "SV62") (pin "6") (pinfunction "6_6") (pintype "passive"))
    )
    (net (code "554") (name "Net-(SV63-Pad1)") (class "Default")
      (node (ref "SV63") (pin "1") (pinfunction "1_1") (pintype "passive"))
      (node (ref "SV63") (pin "3") (pinfunction "3_3") (pintype "passive"))
      (node (ref "SV63") (pin "5") (pinfunction "5_5") (pintype "passive"))
    )
    (net (code "555") (name "Net-(SV63-Pad2)") (class "Default")
      (node (ref "SV63") (pin "2") (pinfunction "2_2") (pintype "passive"))
      (node (ref "SV63") (pin "4") (pinfunction "4_4") (pintype "passive"))
      (node (ref "SV63") (pin "6") (pinfunction "6_6") (pintype "passive"))
    )
    (net (code "556") (name "Net-(SV64-Pad1)") (class "Default")
      (node (ref "SV64") (pin "1") (pinfunction "1_1") (pintype "passive"))
      (node (ref "SV64") (pin "3") (pinfunction "3_3") (pintype "passive"))
      (node (ref "SV64") (pin "5") (pinfunction "5_5") (pintype "passive"))
    )
    (net (code "557") (name "Net-(SV64-Pad2)") (class "Default")
      (node (ref "SV64") (pin "2") (pinfunction "2_2") (pintype "passive"))
      (node (ref "SV64") (pin "4") (pinfunction "4_4") (pintype "passive"))
      (node (ref "SV64") (pin "6") (pinfunction "6_6") (pintype "passive"))
    )
    (net (code "558") (name "Net-(SV66-Pad1)") (class "Default")
      (node (ref "SV66") (pin "1") (pinfunction "1_1") (pintype "passive"))
      (node (ref "SV66") (pin "3") (pinfunction "3_3") (pintype "passive"))
      (node (ref "SV66") (pin "5") (pinfunction "5_5") (pintype "passive"))
    )
    (net (code "559") (name "Net-(SV66-Pad2)") (class "Default")
      (node (ref "SV66") (pin "2") (pinfunction "2_2") (pintype "passive"))
      (node (ref "SV66") (pin "4") (pinfunction "4_4") (pintype "passive"))
      (node (ref "SV66") (pin "6") (pinfunction "6_6") (pintype "passive"))
    )
    (net (code "560") (name "Net-(SV67-Pad1)") (class "Default")
      (node (ref "SV67") (pin "1") (pinfunction "1_1") (pintype "passive"))
      (node (ref "SV67") (pin "3") (pinfunction "3_3") (pintype "passive"))
      (node (ref "SV67") (pin "5") (pinfunction "5_5") (pintype "passive"))
    )
    (net (code "561") (name "Net-(SV67-Pad2)") (class "Default")
      (node (ref "SV67") (pin "2") (pinfunction "2_2") (pintype "passive"))
      (node (ref "SV67") (pin "4") (pinfunction "4_4") (pintype "passive"))
      (node (ref "SV67") (pin "6") (pinfunction "6_6") (pintype "passive"))
    )
    (net (code "562") (name "Net-(SV68-Pad1)") (class "Default")
      (node (ref "SV68") (pin "1") (pinfunction "1_1") (pintype "passive"))
      (node (ref "SV68") (pin "3") (pinfunction "3_3") (pintype "passive"))
      (node (ref "SV68") (pin "5") (pinfunction "5_5") (pintype "passive"))
    )
    (net (code "563") (name "Net-(SV68-Pad2)") (class "Default")
      (node (ref "SV68") (pin "2") (pinfunction "2_2") (pintype "passive"))
      (node (ref "SV68") (pin "4") (pinfunction "4_4") (pintype "passive"))
      (node (ref "SV68") (pin "6") (pinfunction "6_6") (pintype "passive"))
    )
    (net (code "564") (name "VCC") (class "Default")
      (node (ref "A") (pin "A2") (pinfunction "1_A2") (pintype "bidirectional"))
      (node (ref "B") (pin "A2") (pinfunction "1_A2") (pintype "bidirectional"))
      (node (ref "SV10") (pin "10") (pinfunction "10_10") (pintype "passive"))
      (node (ref "SV10") (pin "12") (pinfunction "12_12") (pintype "passive"))
      (node (ref "SV10") (pin "14") (pinfunction "14_14") (pintype "passive"))
      (node (ref "SV10") (pin "16") (pinfunction "16_16") (pintype "passive"))
      (node (ref "SV10") (pin "18") (pinfunction "18_18") (pintype "passive"))
      (node (ref "SV10") (pin "2") (pinfunction "2_2") (pintype "passive"))
      (node (ref "SV10") (pin "20") (pinfunction "20_20") (pintype "passive"))
      (node (ref "SV10") (pin "22") (pinfunction "22_22") (pintype "passive"))
      (node (ref "SV10") (pin "24") (pinfunction "24_24") (pintype "passive"))
      (node (ref "SV10") (pin "26") (pinfunction "26_26") (pintype "passive"))
      (node (ref "SV10") (pin "28") (pinfunction "28_28") (pintype "passive"))
      (node (ref "SV10") (pin "30") (pinfunction "30_30") (pintype "passive"))
      (node (ref "SV10") (pin "32") (pinfunction "32_32") (pintype "passive"))
      (node (ref "SV10") (pin "34") (pinfunction "34_34") (pintype "passive"))
      (node (ref "SV10") (pin "36") (pinfunction "36_36") (pintype "passive"))
      (node (ref "SV10") (pin "4") (pinfunction "4_4") (pintype "passive"))
      (node (ref "SV10") (pin "6") (pinfunction "6_6") (pintype "passive"))
      (node (ref "SV10") (pin "8") (pinfunction "8_8") (pintype "passive"))
      (node (ref "SV12") (pin "10") (pinfunction "10_10") (pintype "passive"))
      (node (ref "SV12") (pin "12") (pinfunction "12_12") (pintype "passive"))
      (node (ref "SV12") (pin "14") (pinfunction "14_14") (pintype "passive"))
      (node (ref "SV12") (pin "16") (pinfunction "16_16") (pintype "passive"))
      (node (ref "SV12") (pin "18") (pinfunction "18_18") (pintype "passive"))
      (node (ref "SV12") (pin "2") (pinfunction "2_2") (pintype "passive"))
      (node (ref "SV12") (pin "20") (pinfunction "20_20") (pintype "passive"))
      (node (ref "SV12") (pin "22") (pinfunction "22_22") (pintype "passive"))
      (node (ref "SV12") (pin "24") (pinfunction "24_24") (pintype "passive"))
      (node (ref "SV12") (pin "26") (pinfunction "26_26") (pintype "passive"))
      (node (ref "SV12") (pin "28") (pinfunction "28_28") (pintype "passive"))
      (node (ref "SV12") (pin "30") (pinfunction "30_30") (pintype "passive"))
      (node (ref "SV12") (pin "32") (pinfunction "32_32") (pintype "passive"))
      (node (ref "SV12") (pin "34") (pinfunction "34_34") (pintype "passive"))
      (node (ref "SV12") (pin "36") (pinfunction "36_36") (pintype "passive"))
      (node (ref "SV12") (pin "38") (pinfunction "38_38") (pintype "passive"))
      (node (ref "SV12") (pin "4") (pinfunction "4_4") (pintype "passive"))
      (node (ref "SV12") (pin "40") (pinfunction "40_40") (pintype "passive"))
      (node (ref "SV12") (pin "6") (pinfunction "6_6") (pintype "passive"))
      (node (ref "SV12") (pin "8") (pinfunction "8_8") (pintype "passive"))
      (node (ref "SV18") (pin "10") (pinfunction "10_10") (pintype "passive"))
      (node (ref "SV18") (pin "12") (pinfunction "12_12") (pintype "passive"))
      (node (ref "SV18") (pin "14") (pinfunction "14_14") (pintype "passive"))
      (node (ref "SV18") (pin "16") (pinfunction "16_16") (pintype "passive"))
      (node (ref "SV18") (pin "18") (pinfunction "18_18") (pintype "passive"))
      (node (ref "SV18") (pin "2") (pinfunction "2_2") (pintype "passive"))
      (node (ref "SV18") (pin "20") (pinfunction "20_20") (pintype "passive"))
      (node (ref "SV18") (pin "22") (pinfunction "22_22") (pintype "passive"))
      (node (ref "SV18") (pin "24") (pinfunction "24_24") (pintype "passive"))
      (node (ref "SV18") (pin "26") (pinfunction "26_26") (pintype "passive"))
      (node (ref "SV18") (pin "28") (pinfunction "28_28") (pintype "passive"))
      (node (ref "SV18") (pin "30") (pinfunction "30_30") (pintype "passive"))
      (node (ref "SV18") (pin "32") (pinfunction "32_32") (pintype "passive"))
      (node (ref "SV18") (pin "34") (pinfunction "34_34") (pintype "passive"))
      (node (ref "SV18") (pin "36") (pinfunction "36_36") (pintype "passive"))
      (node (ref "SV18") (pin "4") (pinfunction "4_4") (pintype "passive"))
      (node (ref "SV18") (pin "6") (pinfunction "6_6") (pintype "passive"))
      (node (ref "SV18") (pin "8") (pinfunction "8_8") (pintype "passive"))
      (node (ref "SV2") (pin "10") (pinfunction "10_10") (pintype "passive"))
      (node (ref "SV2") (pin "12") (pinfunction "12_12") (pintype "passive"))
      (node (ref "SV2") (pin "14") (pinfunction "14_14") (pintype "passive"))
      (node (ref "SV2") (pin "16") (pinfunction "16_16") (pintype "passive"))
      (node (ref "SV2") (pin "18") (pinfunction "18_18") (pintype "passive"))
      (node (ref "SV2") (pin "2") (pinfunction "2_2") (pintype "passive"))
      (node (ref "SV2") (pin "20") (pinfunction "20_20") (pintype "passive"))
      (node (ref "SV2") (pin "22") (pinfunction "22_22") (pintype "passive"))
      (node (ref "SV2") (pin "24") (pinfunction "24_24") (pintype "passive"))
      (node (ref "SV2") (pin "26") (pinfunction "26_26") (pintype "passive"))
      (node (ref "SV2") (pin "28") (pinfunction "28_28") (pintype "passive"))
      (node (ref "SV2") (pin "30") (pinfunction "30_30") (pintype "passive"))
      (node (ref "SV2") (pin "32") (pinfunction "32_32") (pintype "passive"))
      (node (ref "SV2") (pin "34") (pinfunction "34_34") (pintype "passive"))
      (node (ref "SV2") (pin "36") (pinfunction "36_36") (pintype "passive"))
      (node (ref "SV2") (pin "38") (pinfunction "38_38") (pintype "passive"))
      (node (ref "SV2") (pin "4") (pinfunction "4_4") (pintype "passive"))
      (node (ref "SV2") (pin "40") (pinfunction "40_40") (pintype "passive"))
      (node (ref "SV2") (pin "6") (pinfunction "6_6") (pintype "passive"))
      (node (ref "SV2") (pin "8") (pinfunction "8_8") (pintype "passive"))
      (node (ref "SV20") (pin "10") (pinfunction "10_10") (pintype "passive"))
      (node (ref "SV20") (pin "12") (pinfunction "12_12") (pintype "passive"))
      (node (ref "SV20") (pin "14") (pinfunction "14_14") (pintype "passive"))
      (node (ref "SV20") (pin "16") (pinfunction "16_16") (pintype "passive"))
      (node (ref "SV20") (pin "18") (pinfunction "18_18") (pintype "passive"))
      (node (ref "SV20") (pin "2") (pinfunction "2_2") (pintype "passive"))
      (node (ref "SV20") (pin "20") (pinfunction "20_20") (pintype "passive"))
      (node (ref "SV20") (pin "22") (pinfunction "22_22") (pintype "passive"))
      (node (ref "SV20") (pin "24") (pinfunction "24_24") (pintype "passive"))
      (node (ref "SV20") (pin "26") (pinfunction "26_26") (pintype "passive"))
      (node (ref "SV20") (pin "28") (pinfunction "28_28") (pintype "passive"))
      (node (ref "SV20") (pin "30") (pinfunction "30_30") (pintype "passive"))
      (node (ref "SV20") (pin "32") (pinfunction "32_32") (pintype "passive"))
      (node (ref "SV20") (pin "34") (pinfunction "34_34") (pintype "passive"))
      (node (ref "SV20") (pin "36") (pinfunction "36_36") (pintype "passive"))
      (node (ref "SV20") (pin "38") (pinfunction "38_38") (pintype "passive"))
      (node (ref "SV20") (pin "4") (pinfunction "4_4") (pintype "passive"))
      (node (ref "SV20") (pin "40") (pinfunction "40_40") (pintype "passive"))
      (node (ref "SV20") (pin "6") (pinfunction "6_6") (pintype "passive"))
      (node (ref "SV20") (pin "8") (pinfunction "8_8") (pintype "passive"))
      (node (ref "SV26") (pin "10") (pinfunction "10_10") (pintype "passive"))
      (node (ref "SV26") (pin "12") (pinfunction "12_12") (pintype "passive"))
      (node (ref "SV26") (pin "14") (pinfunction "14_14") (pintype "passive"))
      (node (ref "SV26") (pin "16") (pinfunction "16_16") (pintype "passive"))
      (node (ref "SV26") (pin "18") (pinfunction "18_18") (pintype "passive"))
      (node (ref "SV26") (pin "2") (pinfunction "2_2") (pintype "passive"))
      (node (ref "SV26") (pin "20") (pinfunction "20_20") (pintype "passive"))
      (node (ref "SV26") (pin "22") (pinfunction "22_22") (pintype "passive"))
      (node (ref "SV26") (pin "24") (pinfunction "24_24") (pintype "passive"))
      (node (ref "SV26") (pin "26") (pinfunction "26_26") (pintype "passive"))
      (node (ref "SV26") (pin "28") (pinfunction "28_28") (pintype "passive"))
      (node (ref "SV26") (pin "30") (pinfunction "30_30") (pintype "passive"))
      (node (ref "SV26") (pin "32") (pinfunction "32_32") (pintype "passive"))
      (node (ref "SV26") (pin "34") (pinfunction "34_34") (pintype "passive"))
      (node (ref "SV26") (pin "36") (pinfunction "36_36") (pintype "passive"))
      (node (ref "SV26") (pin "4") (pinfunction "4_4") (pintype "passive"))
      (node (ref "SV26") (pin "6") (pinfunction "6_6") (pintype "passive"))
      (node (ref "SV26") (pin "8") (pinfunction "8_8") (pintype "passive"))
      (node (ref "SV28") (pin "10") (pinfunction "10_10") (pintype "passive"))
      (node (ref "SV28") (pin "12") (pinfunction "12_12") (pintype "passive"))
      (node (ref "SV28") (pin "14") (pinfunction "14_14") (pintype "passive"))
      (node (ref "SV28") (pin "16") (pinfunction "16_16") (pintype "passive"))
      (node (ref "SV28") (pin "18") (pinfunction "18_18") (pintype "passive"))
      (node (ref "SV28") (pin "2") (pinfunction "2_2") (pintype "passive"))
      (node (ref "SV28") (pin "20") (pinfunction "20_20") (pintype "passive"))
      (node (ref "SV28") (pin "22") (pinfunction "22_22") (pintype "passive"))
      (node (ref "SV28") (pin "24") (pinfunction "24_24") (pintype "passive"))
      (node (ref "SV28") (pin "26") (pinfunction "26_26") (pintype "passive"))
      (node (ref "SV28") (pin "28") (pinfunction "28_28") (pintype "passive"))
      (node (ref "SV28") (pin "30") (pinfunction "30_30") (pintype "passive"))
      (node (ref "SV28") (pin "32") (pinfunction "32_32") (pintype "passive"))
      (node (ref "SV28") (pin "34") (pinfunction "34_34") (pintype "passive"))
      (node (ref "SV28") (pin "36") (pinfunction "36_36") (pintype "passive"))
      (node (ref "SV28") (pin "38") (pinfunction "38_38") (pintype "passive"))
      (node (ref "SV28") (pin "4") (pinfunction "4_4") (pintype "passive"))
      (node (ref "SV28") (pin "40") (pinfunction "40_40") (pintype "passive"))
      (node (ref "SV28") (pin "6") (pinfunction "6_6") (pintype "passive"))
      (node (ref "SV28") (pin "8") (pinfunction "8_8") (pintype "passive"))
      (node (ref "SV34") (pin "10") (pinfunction "10_10") (pintype "passive"))
      (node (ref "SV34") (pin "12") (pinfunction "12_12") (pintype "passive"))
      (node (ref "SV34") (pin "14") (pinfunction "14_14") (pintype "passive"))
      (node (ref "SV34") (pin "16") (pinfunction "16_16") (pintype "passive"))
      (node (ref "SV34") (pin "18") (pinfunction "18_18") (pintype "passive"))
      (node (ref "SV34") (pin "2") (pinfunction "2_2") (pintype "passive"))
      (node (ref "SV34") (pin "20") (pinfunction "20_20") (pintype "passive"))
      (node (ref "SV34") (pin "22") (pinfunction "22_22") (pintype "passive"))
      (node (ref "SV34") (pin "24") (pinfunction "24_24") (pintype "passive"))
      (node (ref "SV34") (pin "26") (pinfunction "26_26") (pintype "passive"))
      (node (ref "SV34") (pin "28") (pinfunction "28_28") (pintype "passive"))
      (node (ref "SV34") (pin "30") (pinfunction "30_30") (pintype "passive"))
      (node (ref "SV34") (pin "32") (pinfunction "32_32") (pintype "passive"))
      (node (ref "SV34") (pin "34") (pinfunction "34_34") (pintype "passive"))
      (node (ref "SV34") (pin "36") (pinfunction "36_36") (pintype "passive"))
      (node (ref "SV34") (pin "4") (pinfunction "4_4") (pintype "passive"))
      (node (ref "SV34") (pin "6") (pinfunction "6_6") (pintype "passive"))
      (node (ref "SV34") (pin "8") (pinfunction "8_8") (pintype "passive"))
      (node (ref "SV36") (pin "10") (pinfunction "10_10") (pintype "passive"))
      (node (ref "SV36") (pin "12") (pinfunction "12_12") (pintype "passive"))
      (node (ref "SV36") (pin "14") (pinfunction "14_14") (pintype "passive"))
      (node (ref "SV36") (pin "16") (pinfunction "16_16") (pintype "passive"))
      (node (ref "SV36") (pin "18") (pinfunction "18_18") (pintype "passive"))
      (node (ref "SV36") (pin "2") (pinfunction "2_2") (pintype "passive"))
      (node (ref "SV36") (pin "20") (pinfunction "20_20") (pintype "passive"))
      (node (ref "SV36") (pin "22") (pinfunction "22_22") (pintype "passive"))
      (node (ref "SV36") (pin "24") (pinfunction "24_24") (pintype "passive"))
      (node (ref "SV36") (pin "26") (pinfunction "26_26") (pintype "passive"))
      (node (ref "SV36") (pin "28") (pinfunction "28_28") (pintype "passive"))
      (node (ref "SV36") (pin "30") (pinfunction "30_30") (pintype "passive"))
      (node (ref "SV36") (pin "32") (pinfunction "32_32") (pintype "passive"))
      (node (ref "SV36") (pin "34") (pinfunction "34_34") (pintype "passive"))
      (node (ref "SV36") (pin "36") (pinfunction "36_36") (pintype "passive"))
      (node (ref "SV36") (pin "38") (pinfunction "38_38") (pintype "passive"))
      (node (ref "SV36") (pin "4") (pinfunction "4_4") (pintype "passive"))
      (node (ref "SV36") (pin "40") (pinfunction "40_40") (pintype "passive"))
      (node (ref "SV36") (pin "6") (pinfunction "6_6") (pintype "passive"))
      (node (ref "SV36") (pin "8") (pinfunction "8_8") (pintype "passive"))
      (node (ref "SV42") (pin "10") (pinfunction "10_10") (pintype "passive"))
      (node (ref "SV42") (pin "12") (pinfunction "12_12") (pintype "passive"))
      (node (ref "SV42") (pin "14") (pinfunction "14_14") (pintype "passive"))
      (node (ref "SV42") (pin "16") (pinfunction "16_16") (pintype "passive"))
      (node (ref "SV42") (pin "18") (pinfunction "18_18") (pintype "passive"))
      (node (ref "SV42") (pin "2") (pinfunction "2_2") (pintype "passive"))
      (node (ref "SV42") (pin "20") (pinfunction "20_20") (pintype "passive"))
      (node (ref "SV42") (pin "22") (pinfunction "22_22") (pintype "passive"))
      (node (ref "SV42") (pin "24") (pinfunction "24_24") (pintype "passive"))
      (node (ref "SV42") (pin "26") (pinfunction "26_26") (pintype "passive"))
      (node (ref "SV42") (pin "28") (pinfunction "28_28") (pintype "passive"))
      (node (ref "SV42") (pin "30") (pinfunction "30_30") (pintype "passive"))
      (node (ref "SV42") (pin "32") (pinfunction "32_32") (pintype "passive"))
      (node (ref "SV42") (pin "34") (pinfunction "34_34") (pintype "passive"))
      (node (ref "SV42") (pin "36") (pinfunction "36_36") (pintype "passive"))
      (node (ref "SV42") (pin "4") (pinfunction "4_4") (pintype "passive"))
      (node (ref "SV42") (pin "6") (pinfunction "6_6") (pintype "passive"))
      (node (ref "SV42") (pin "8") (pinfunction "8_8") (pintype "passive"))
      (node (ref "SV44") (pin "10") (pinfunction "10_10") (pintype "passive"))
      (node (ref "SV44") (pin "12") (pinfunction "12_12") (pintype "passive"))
      (node (ref "SV44") (pin "14") (pinfunction "14_14") (pintype "passive"))
      (node (ref "SV44") (pin "16") (pinfunction "16_16") (pintype "passive"))
      (node (ref "SV44") (pin "18") (pinfunction "18_18") (pintype "passive"))
      (node (ref "SV44") (pin "2") (pinfunction "2_2") (pintype "passive"))
      (node (ref "SV44") (pin "20") (pinfunction "20_20") (pintype "passive"))
      (node (ref "SV44") (pin "22") (pinfunction "22_22") (pintype "passive"))
      (node (ref "SV44") (pin "24") (pinfunction "24_24") (pintype "passive"))
      (node (ref "SV44") (pin "26") (pinfunction "26_26") (pintype "passive"))
      (node (ref "SV44") (pin "28") (pinfunction "28_28") (pintype "passive"))
      (node (ref "SV44") (pin "30") (pinfunction "30_30") (pintype "passive"))
      (node (ref "SV44") (pin "32") (pinfunction "32_32") (pintype "passive"))
      (node (ref "SV44") (pin "34") (pinfunction "34_34") (pintype "passive"))
      (node (ref "SV44") (pin "36") (pinfunction "36_36") (pintype "passive"))
      (node (ref "SV44") (pin "38") (pinfunction "38_38") (pintype "passive"))
      (node (ref "SV44") (pin "4") (pinfunction "4_4") (pintype "passive"))
      (node (ref "SV44") (pin "40") (pinfunction "40_40") (pintype "passive"))
      (node (ref "SV44") (pin "6") (pinfunction "6_6") (pintype "passive"))
      (node (ref "SV44") (pin "8") (pinfunction "8_8") (pintype "passive"))
      (node (ref "SV8") (pin "10") (pinfunction "10_10") (pintype "passive"))
      (node (ref "SV8") (pin "12") (pinfunction "12_12") (pintype "passive"))
      (node (ref "SV8") (pin "14") (pinfunction "14_14") (pintype "passive"))
      (node (ref "SV8") (pin "16") (pinfunction "16_16") (pintype "passive"))
      (node (ref "SV8") (pin "18") (pinfunction "18_18") (pintype "passive"))
      (node (ref "SV8") (pin "2") (pinfunction "2_2") (pintype "passive"))
      (node (ref "SV8") (pin "20") (pinfunction "20_20") (pintype "passive"))
      (node (ref "SV8") (pin "22") (pinfunction "22_22") (pintype "passive"))
      (node (ref "SV8") (pin "24") (pinfunction "24_24") (pintype "passive"))
      (node (ref "SV8") (pin "26") (pinfunction "26_26") (pintype "passive"))
      (node (ref "SV8") (pin "28") (pinfunction "28_28") (pintype "passive"))
      (node (ref "SV8") (pin "30") (pinfunction "30_30") (pintype "passive"))
      (node (ref "SV8") (pin "32") (pinfunction "32_32") (pintype "passive"))
      (node (ref "SV8") (pin "34") (pinfunction "34_34") (pintype "passive"))
      (node (ref "SV8") (pin "36") (pinfunction "36_36") (pintype "passive"))
      (node (ref "SV8") (pin "4") (pinfunction "4_4") (pintype "passive"))
      (node (ref "SV8") (pin "6") (pinfunction "6_6") (pintype "passive"))
      (node (ref "SV8") (pin "8") (pinfunction "8_8") (pintype "passive"))
      (node (ref "U$3") (pin "A2") (pinfunction "P$1_A2") (pintype "passive"))
      (node (ref "U$5") (pin "A2") (pinfunction "P$1_A2") (pintype "passive"))
    )
  )
)
